# soundcard.net
KiCad netlist of a schematic drawn in EAGLE
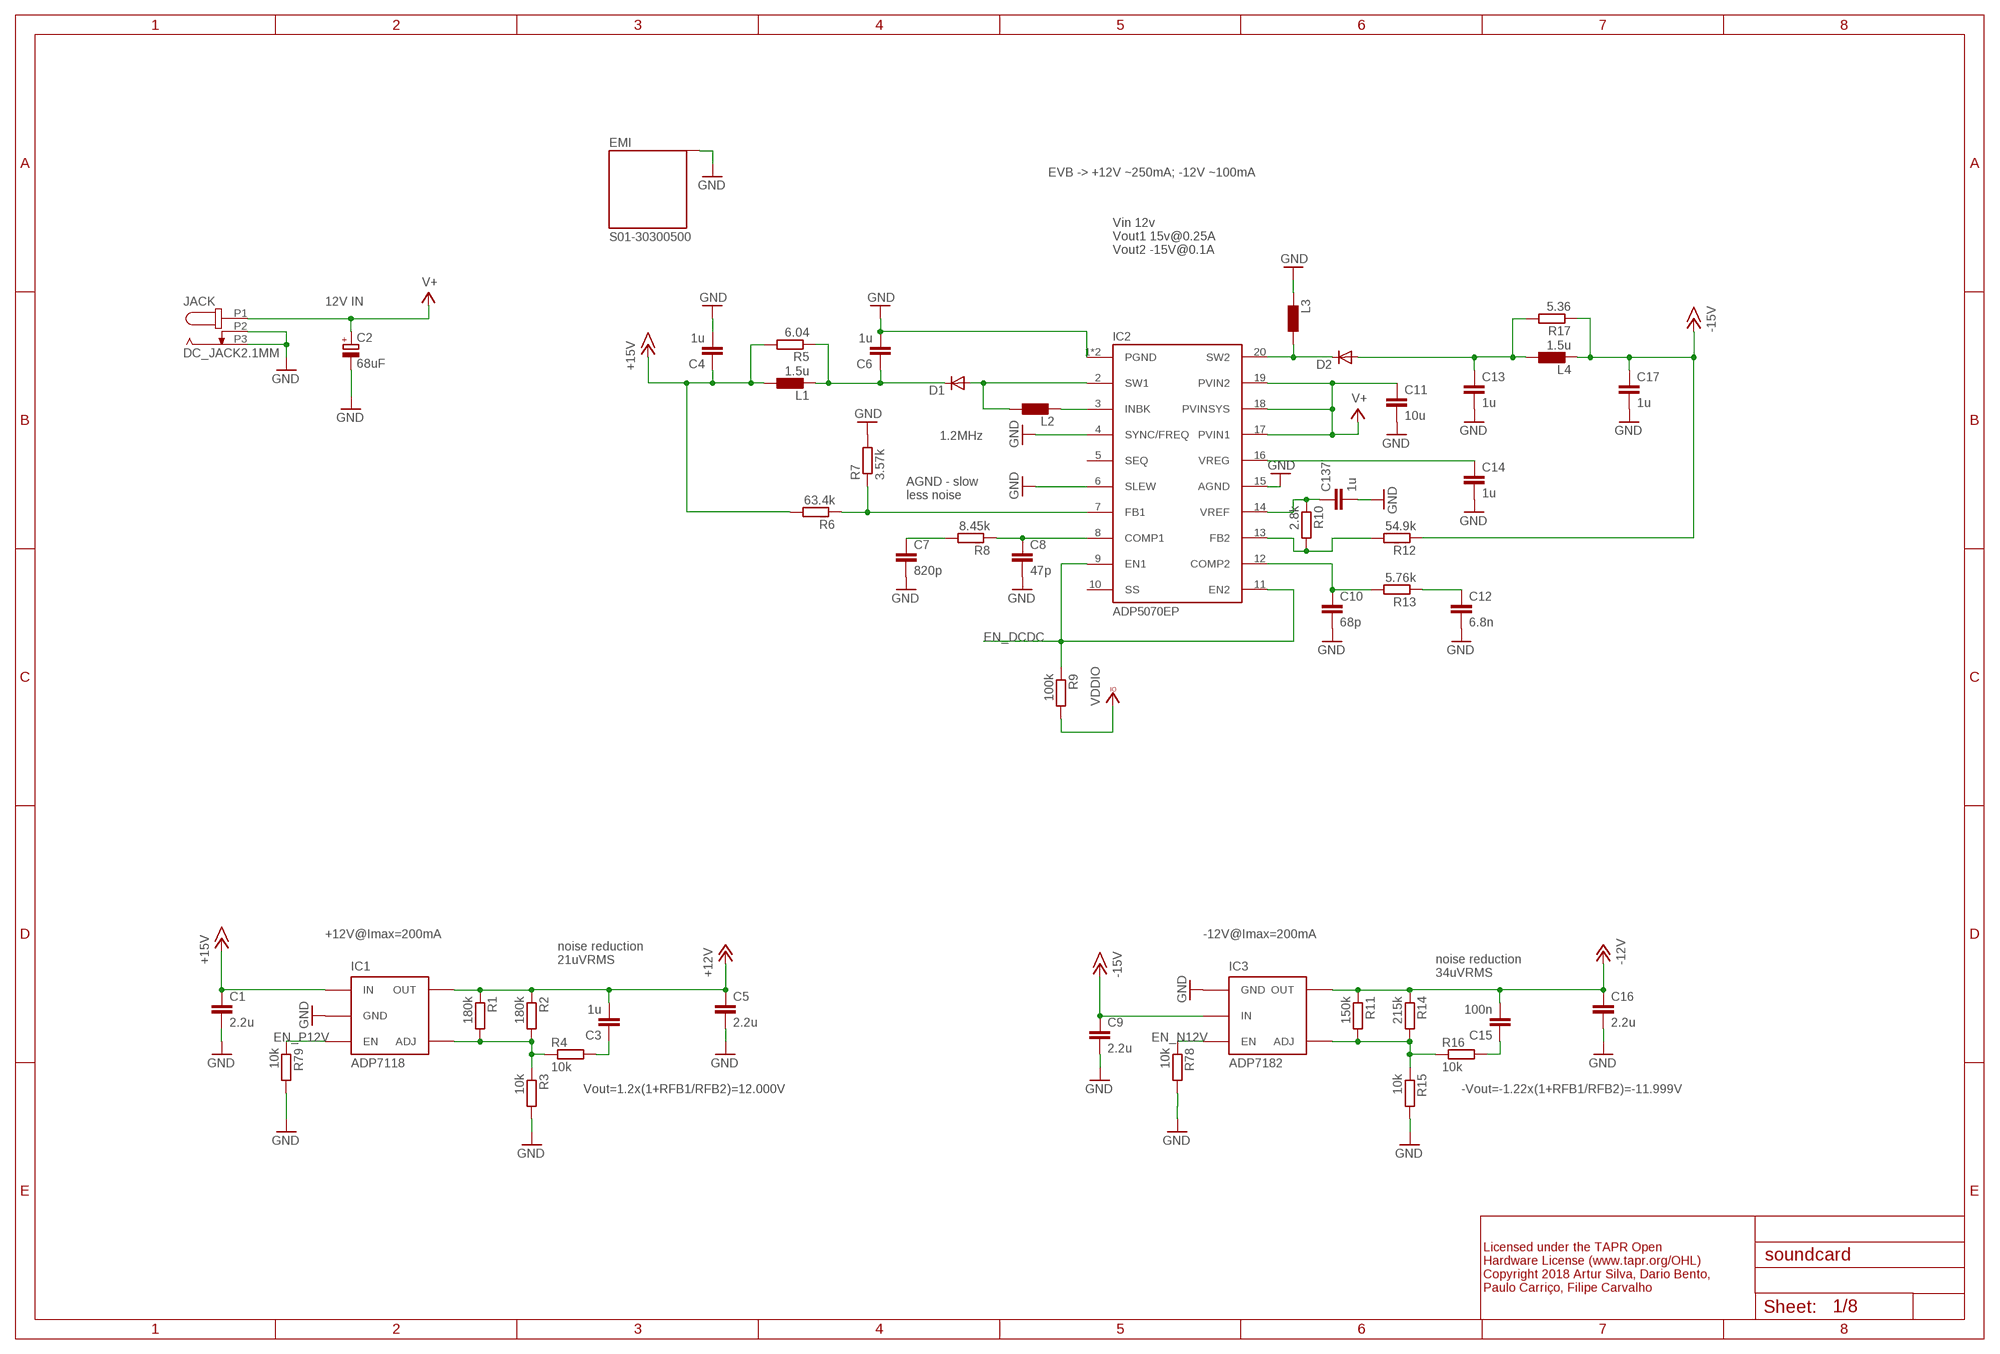
[diagram p0: schematic, sheet 1]
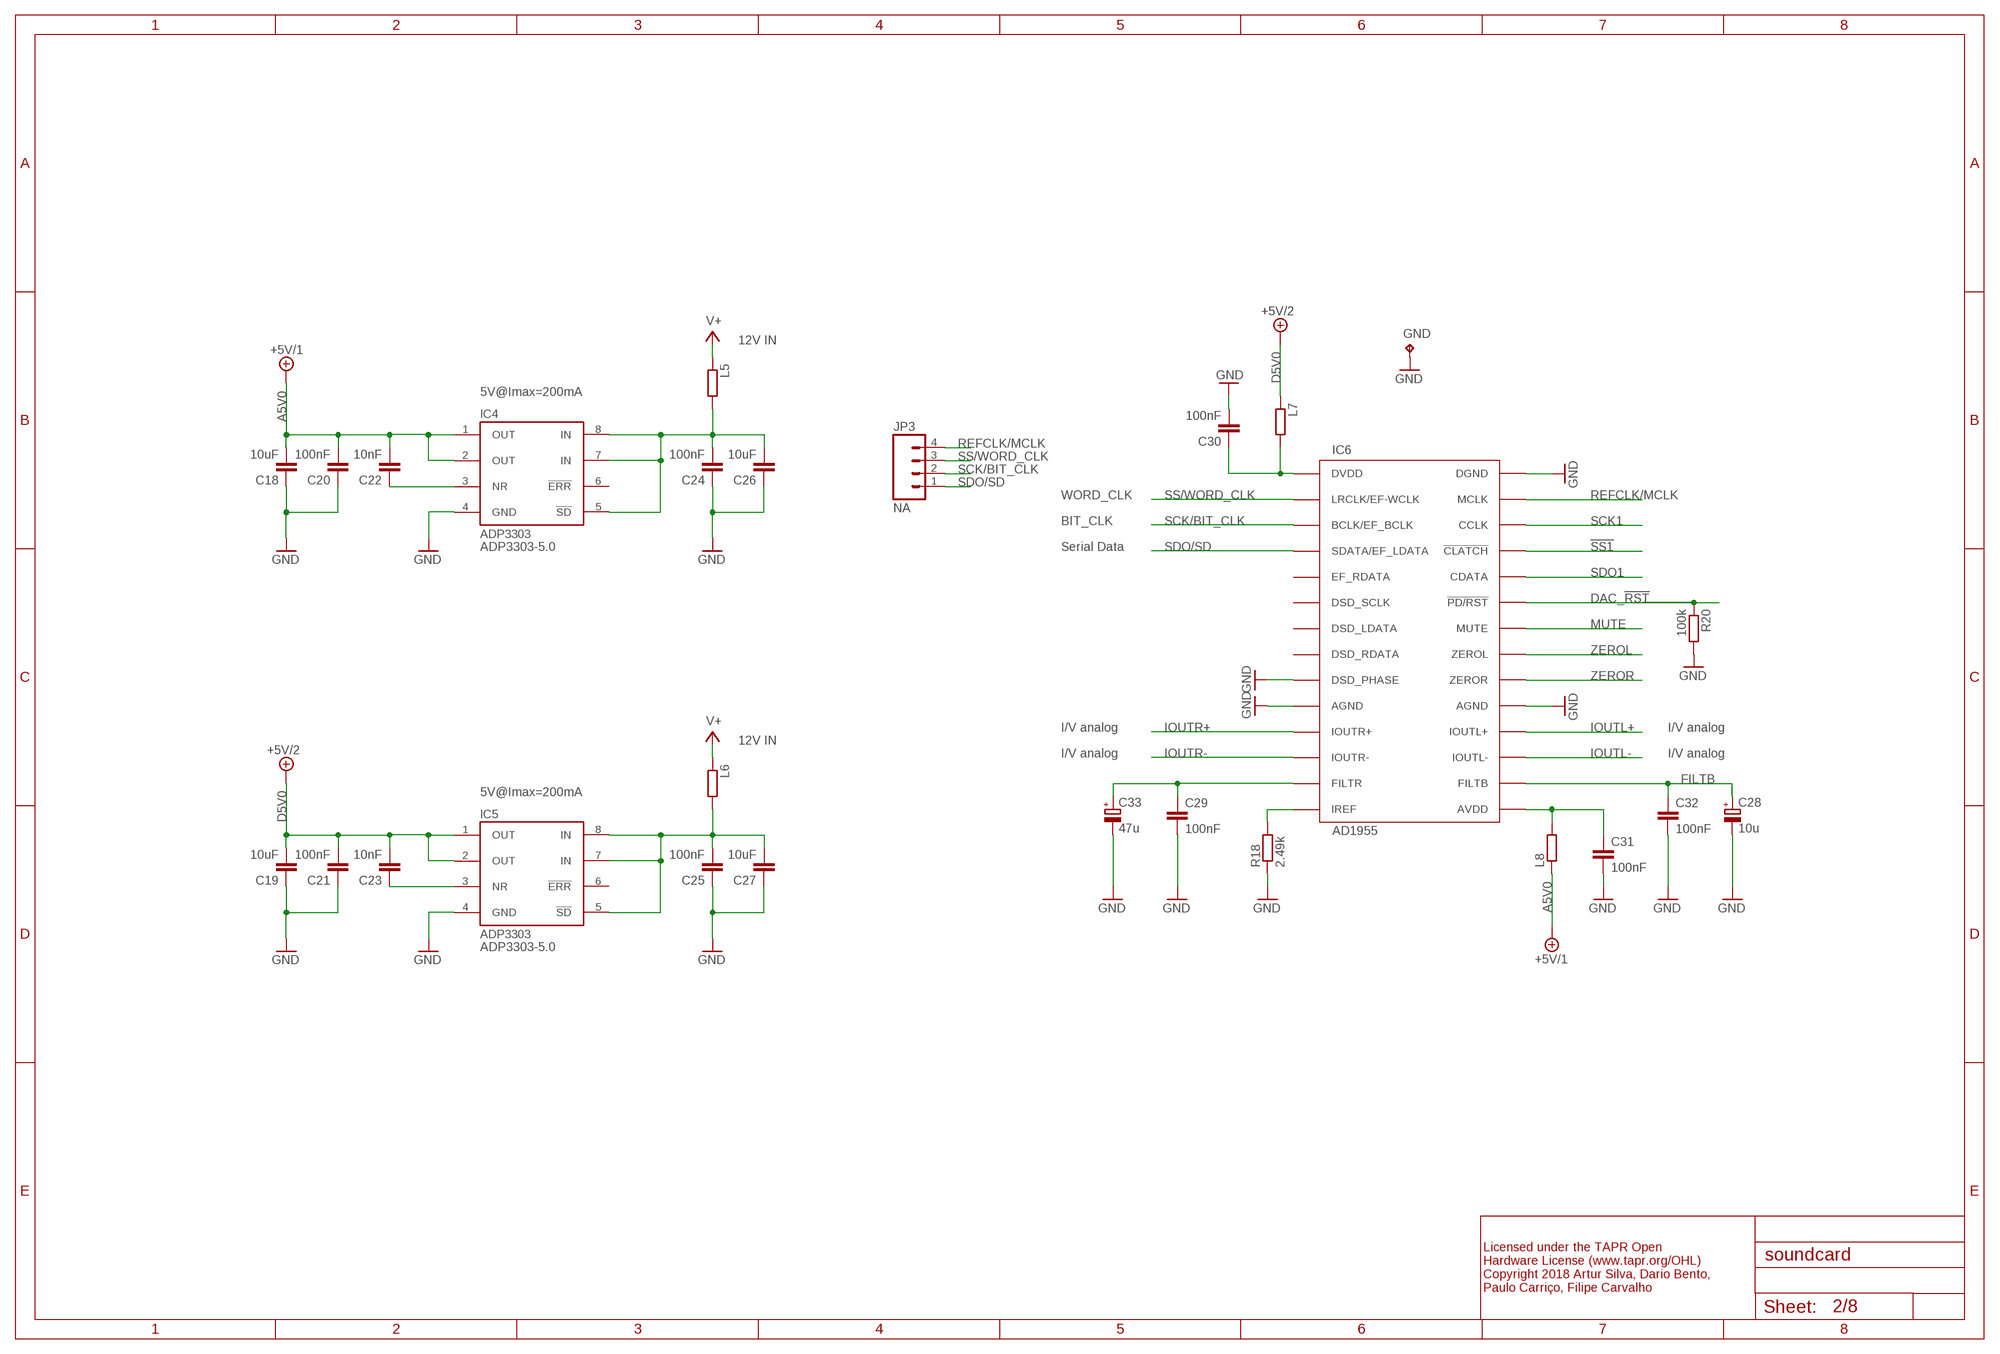
[diagram p1: schematic, sheet 2]
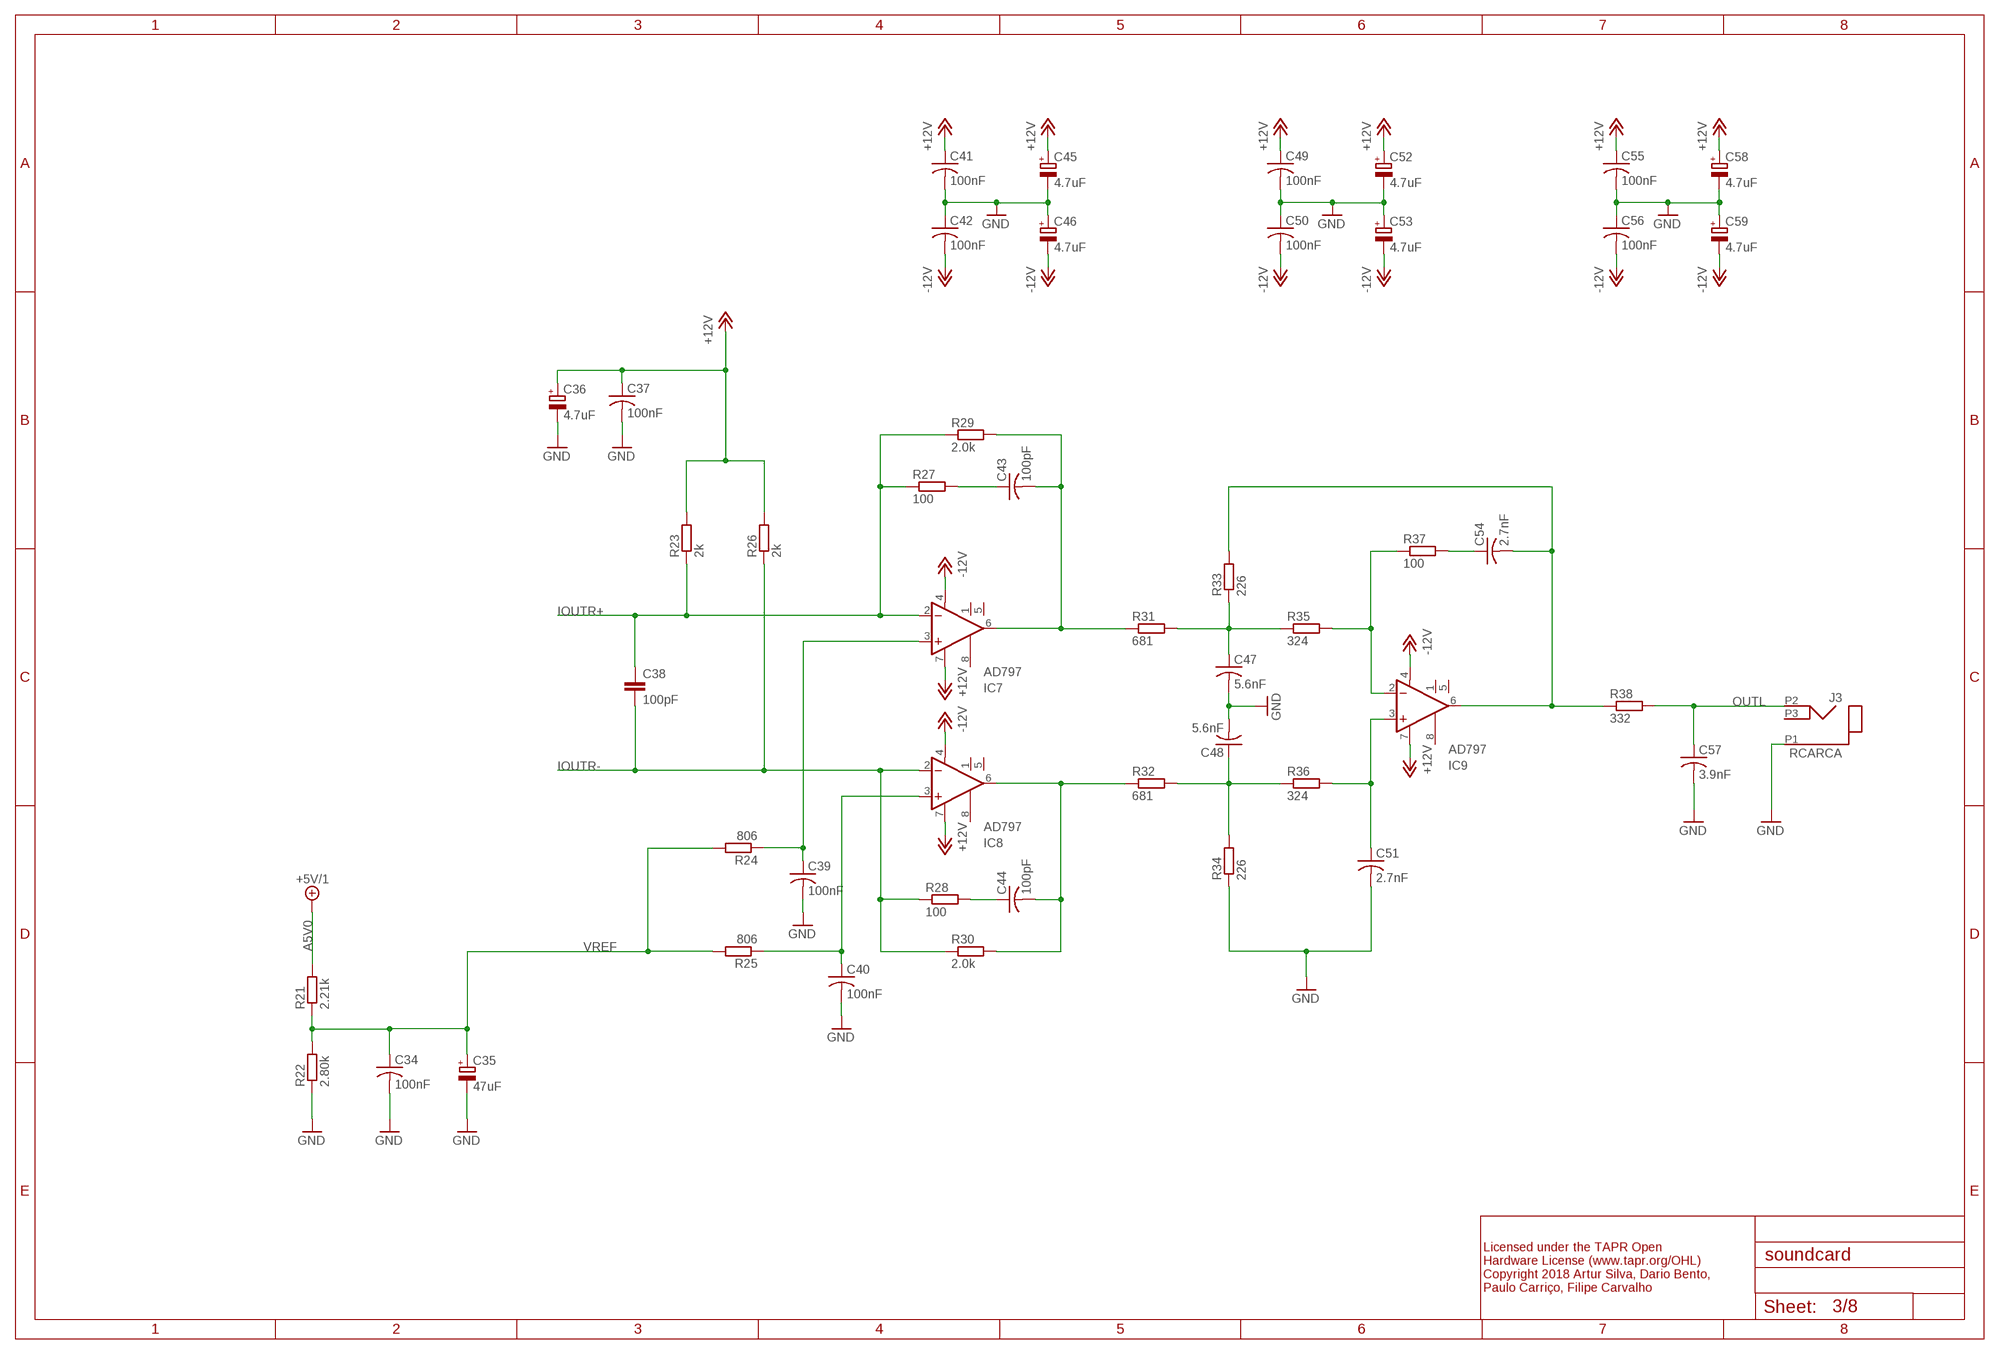
[diagram p2: schematic, sheet 3]
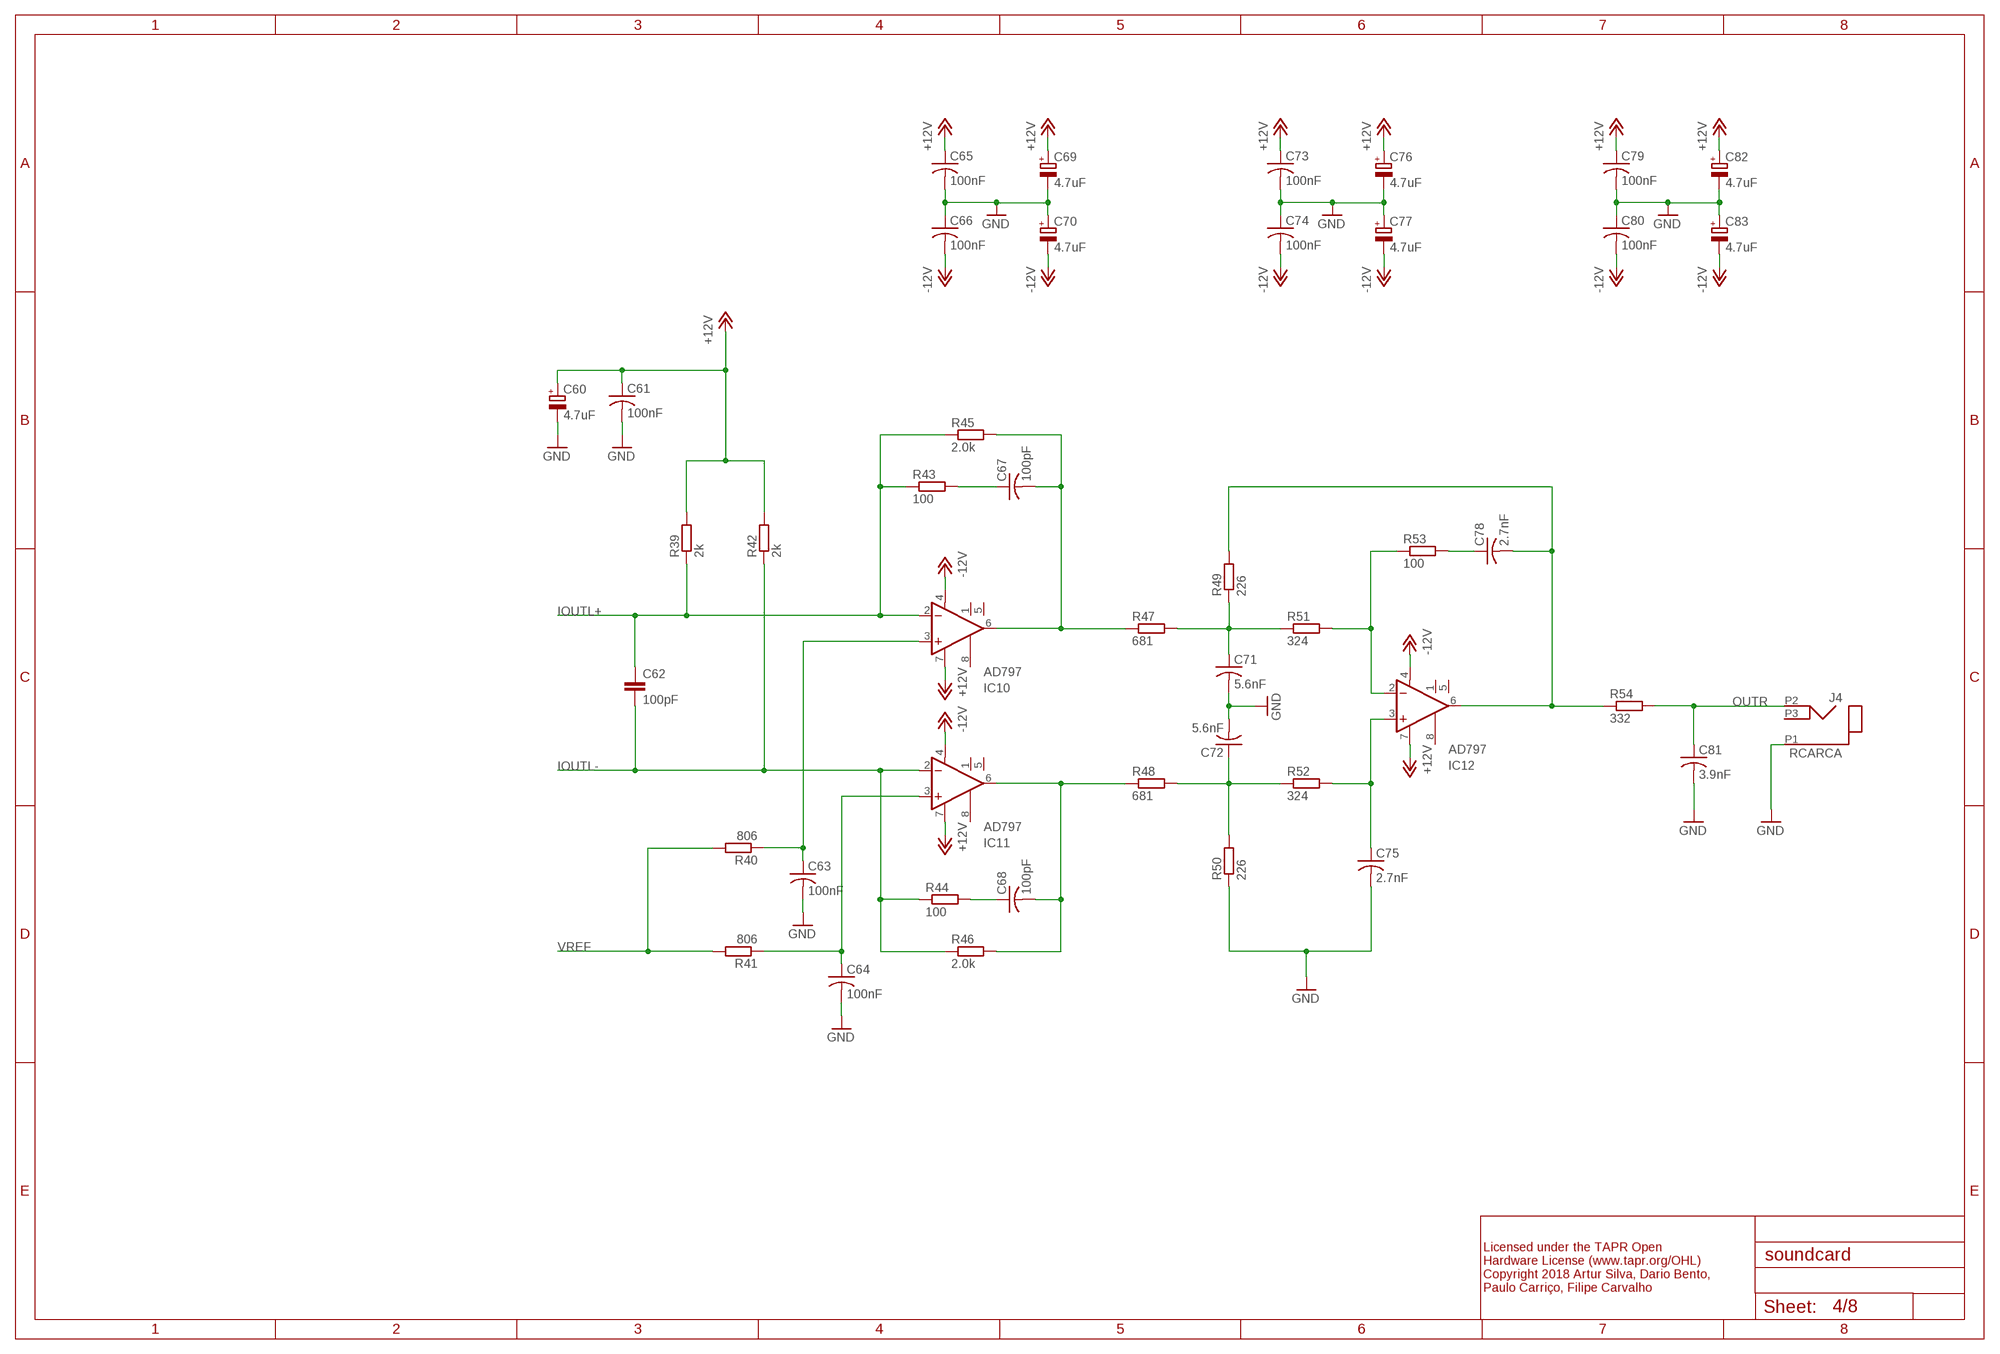
[diagram p3: schematic, sheet 4]
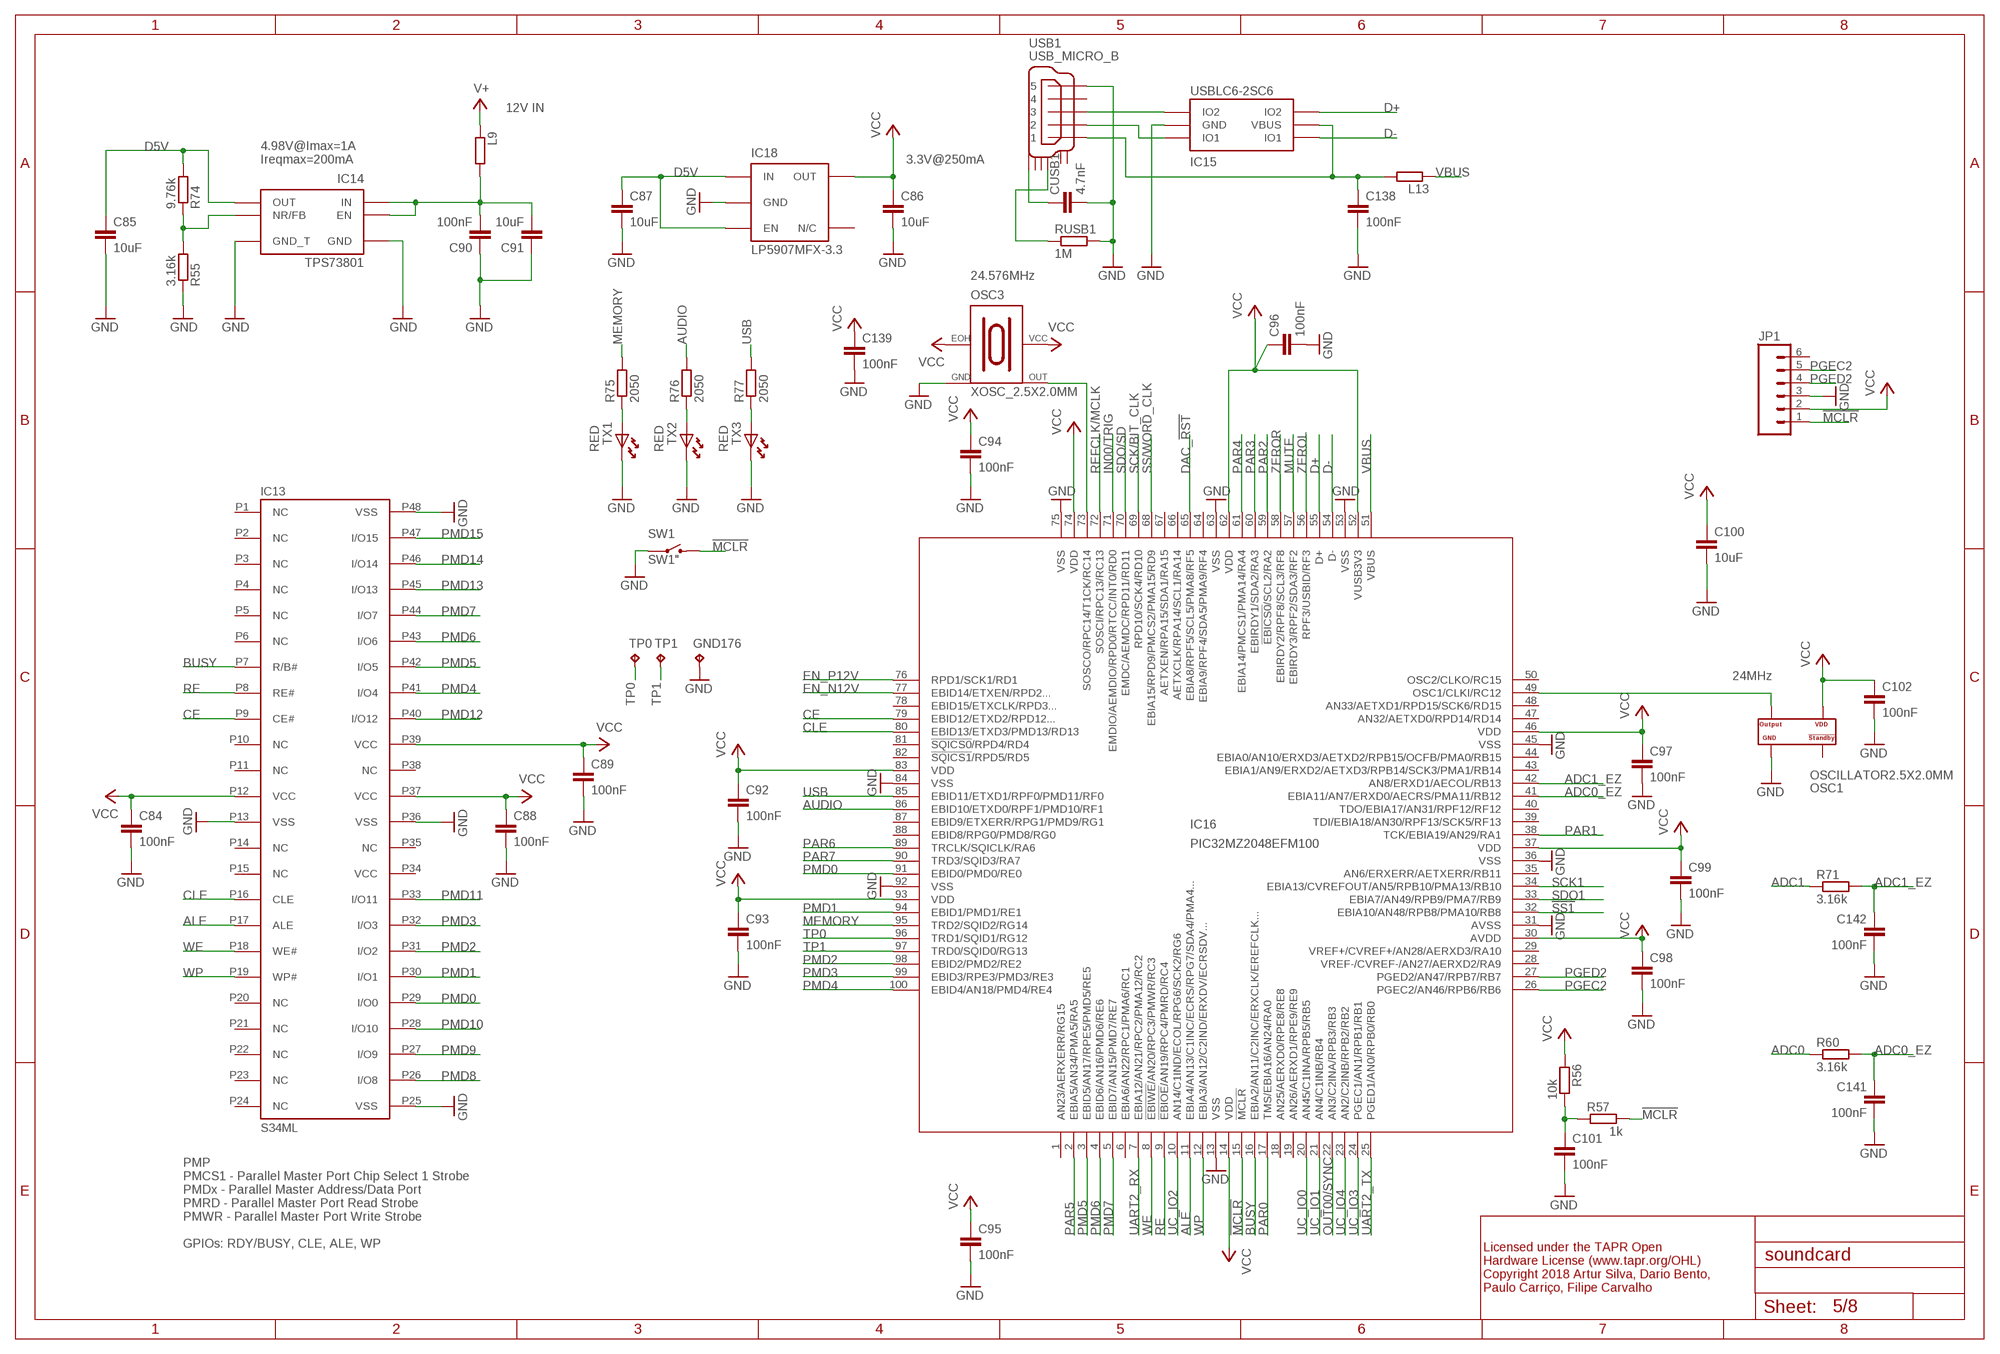
[diagram p4: schematic, sheet 5]
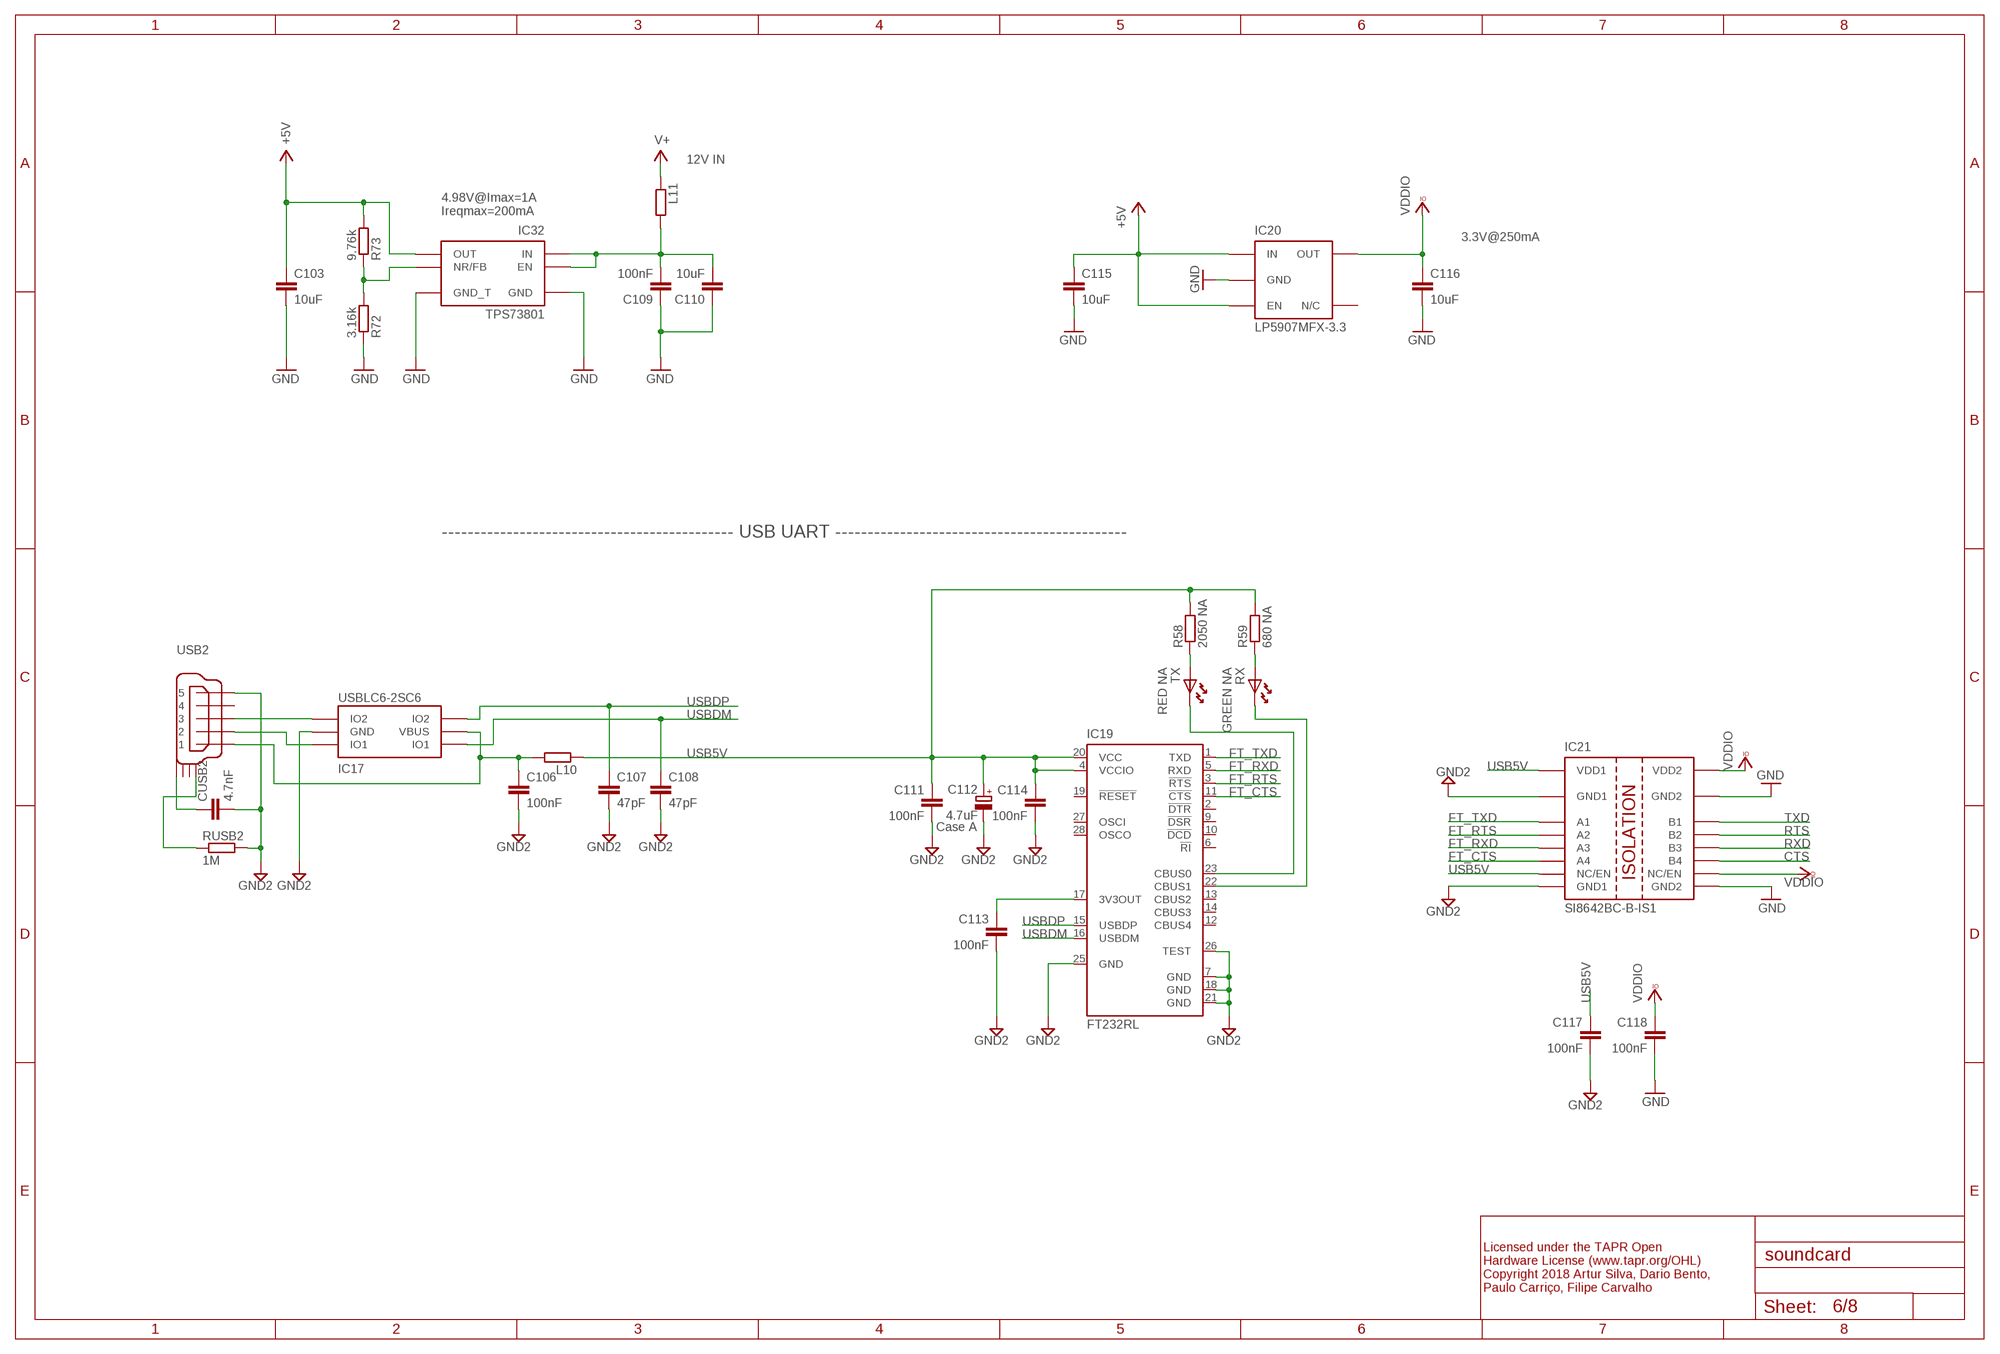
[diagram p5: schematic, sheet 6]
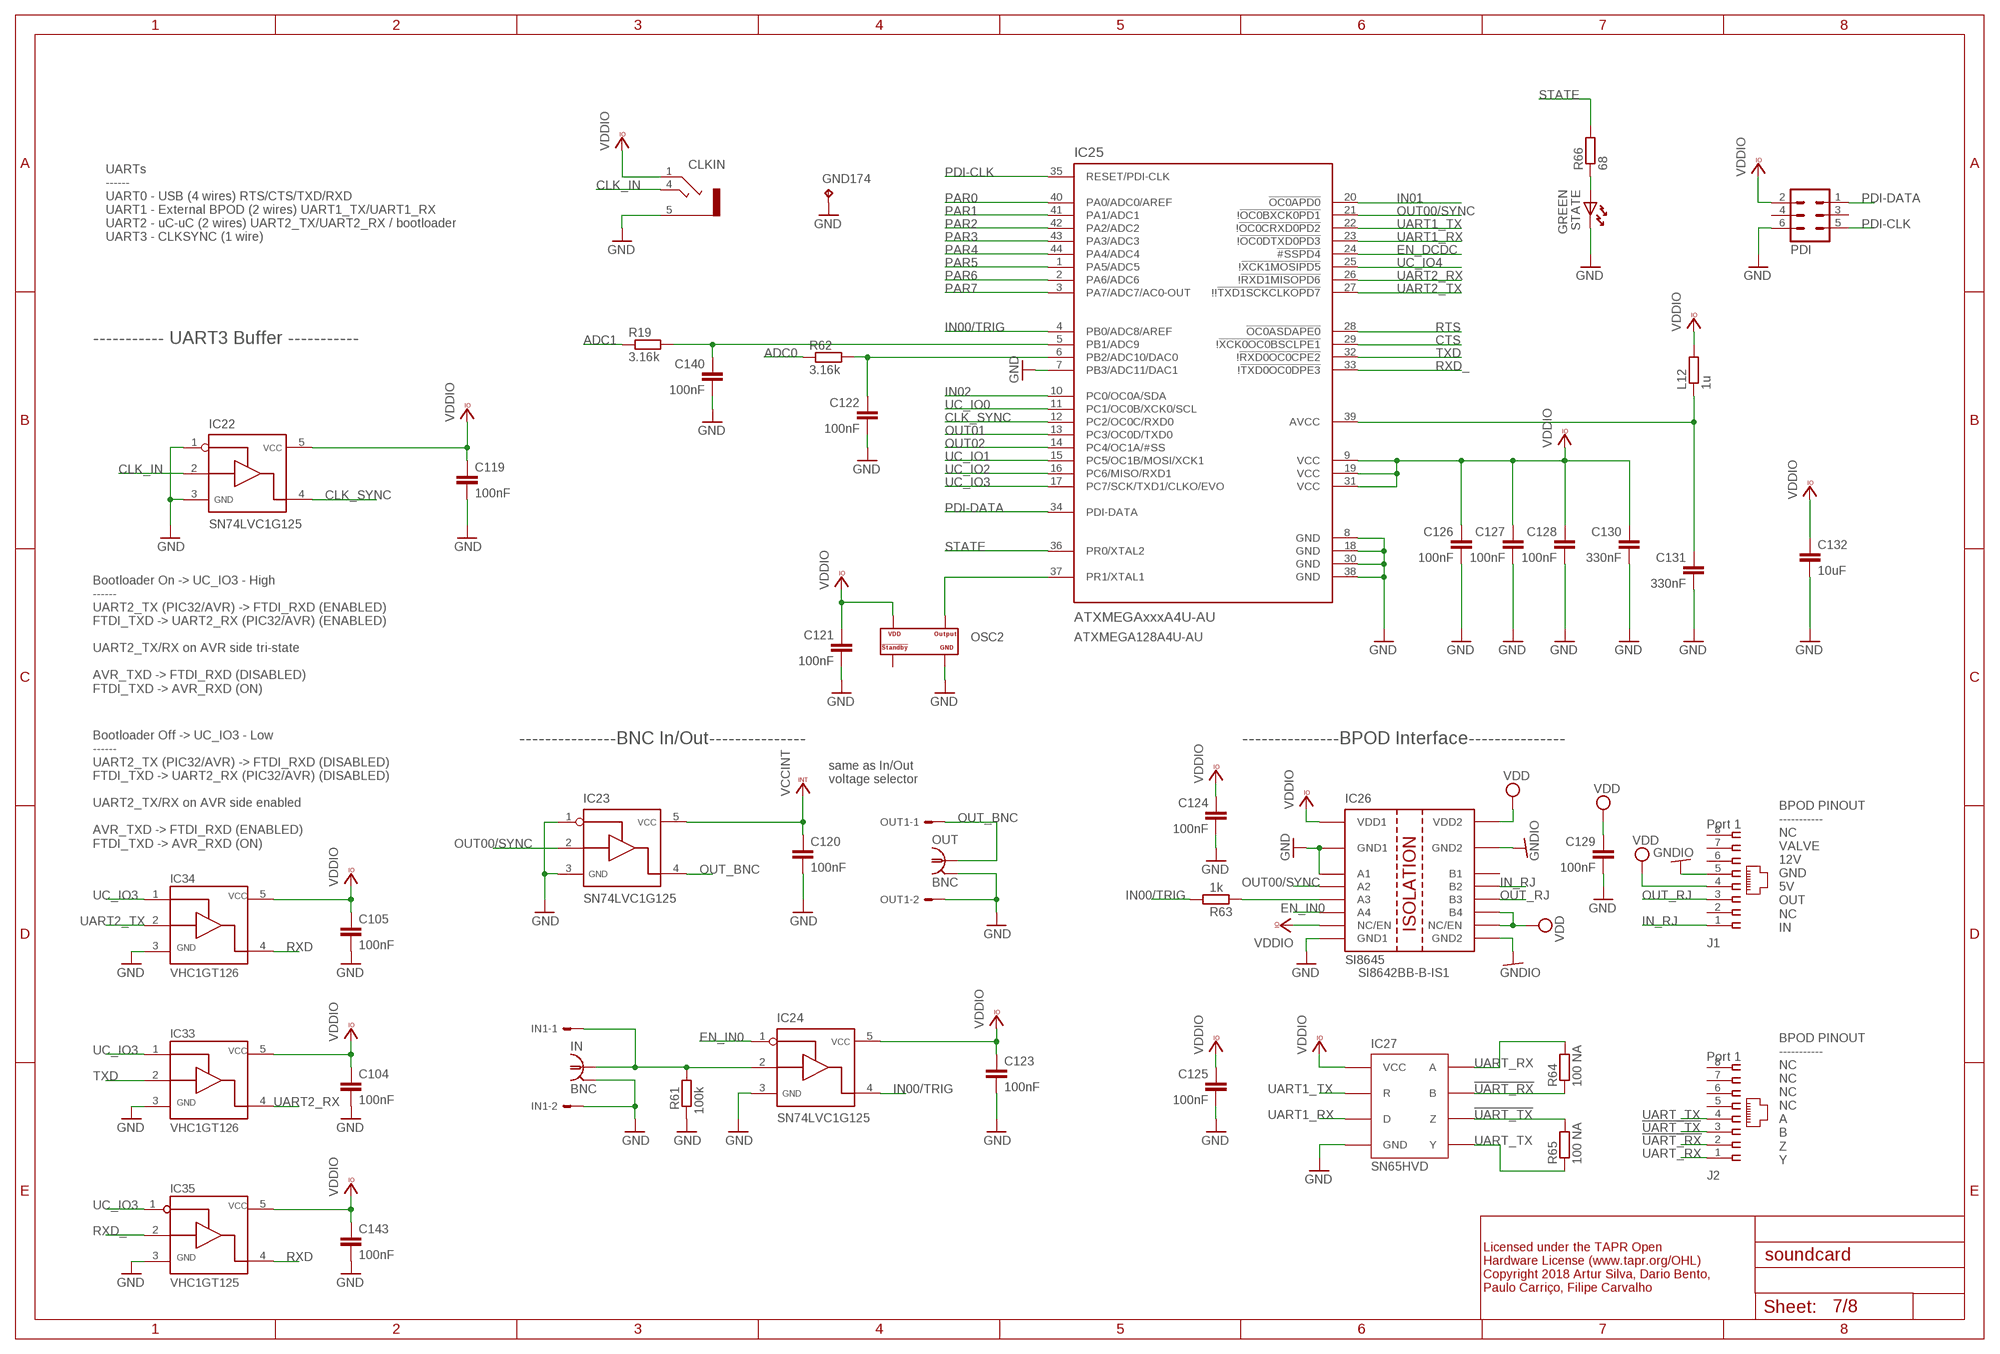
[diagram p6: schematic, sheet 7]
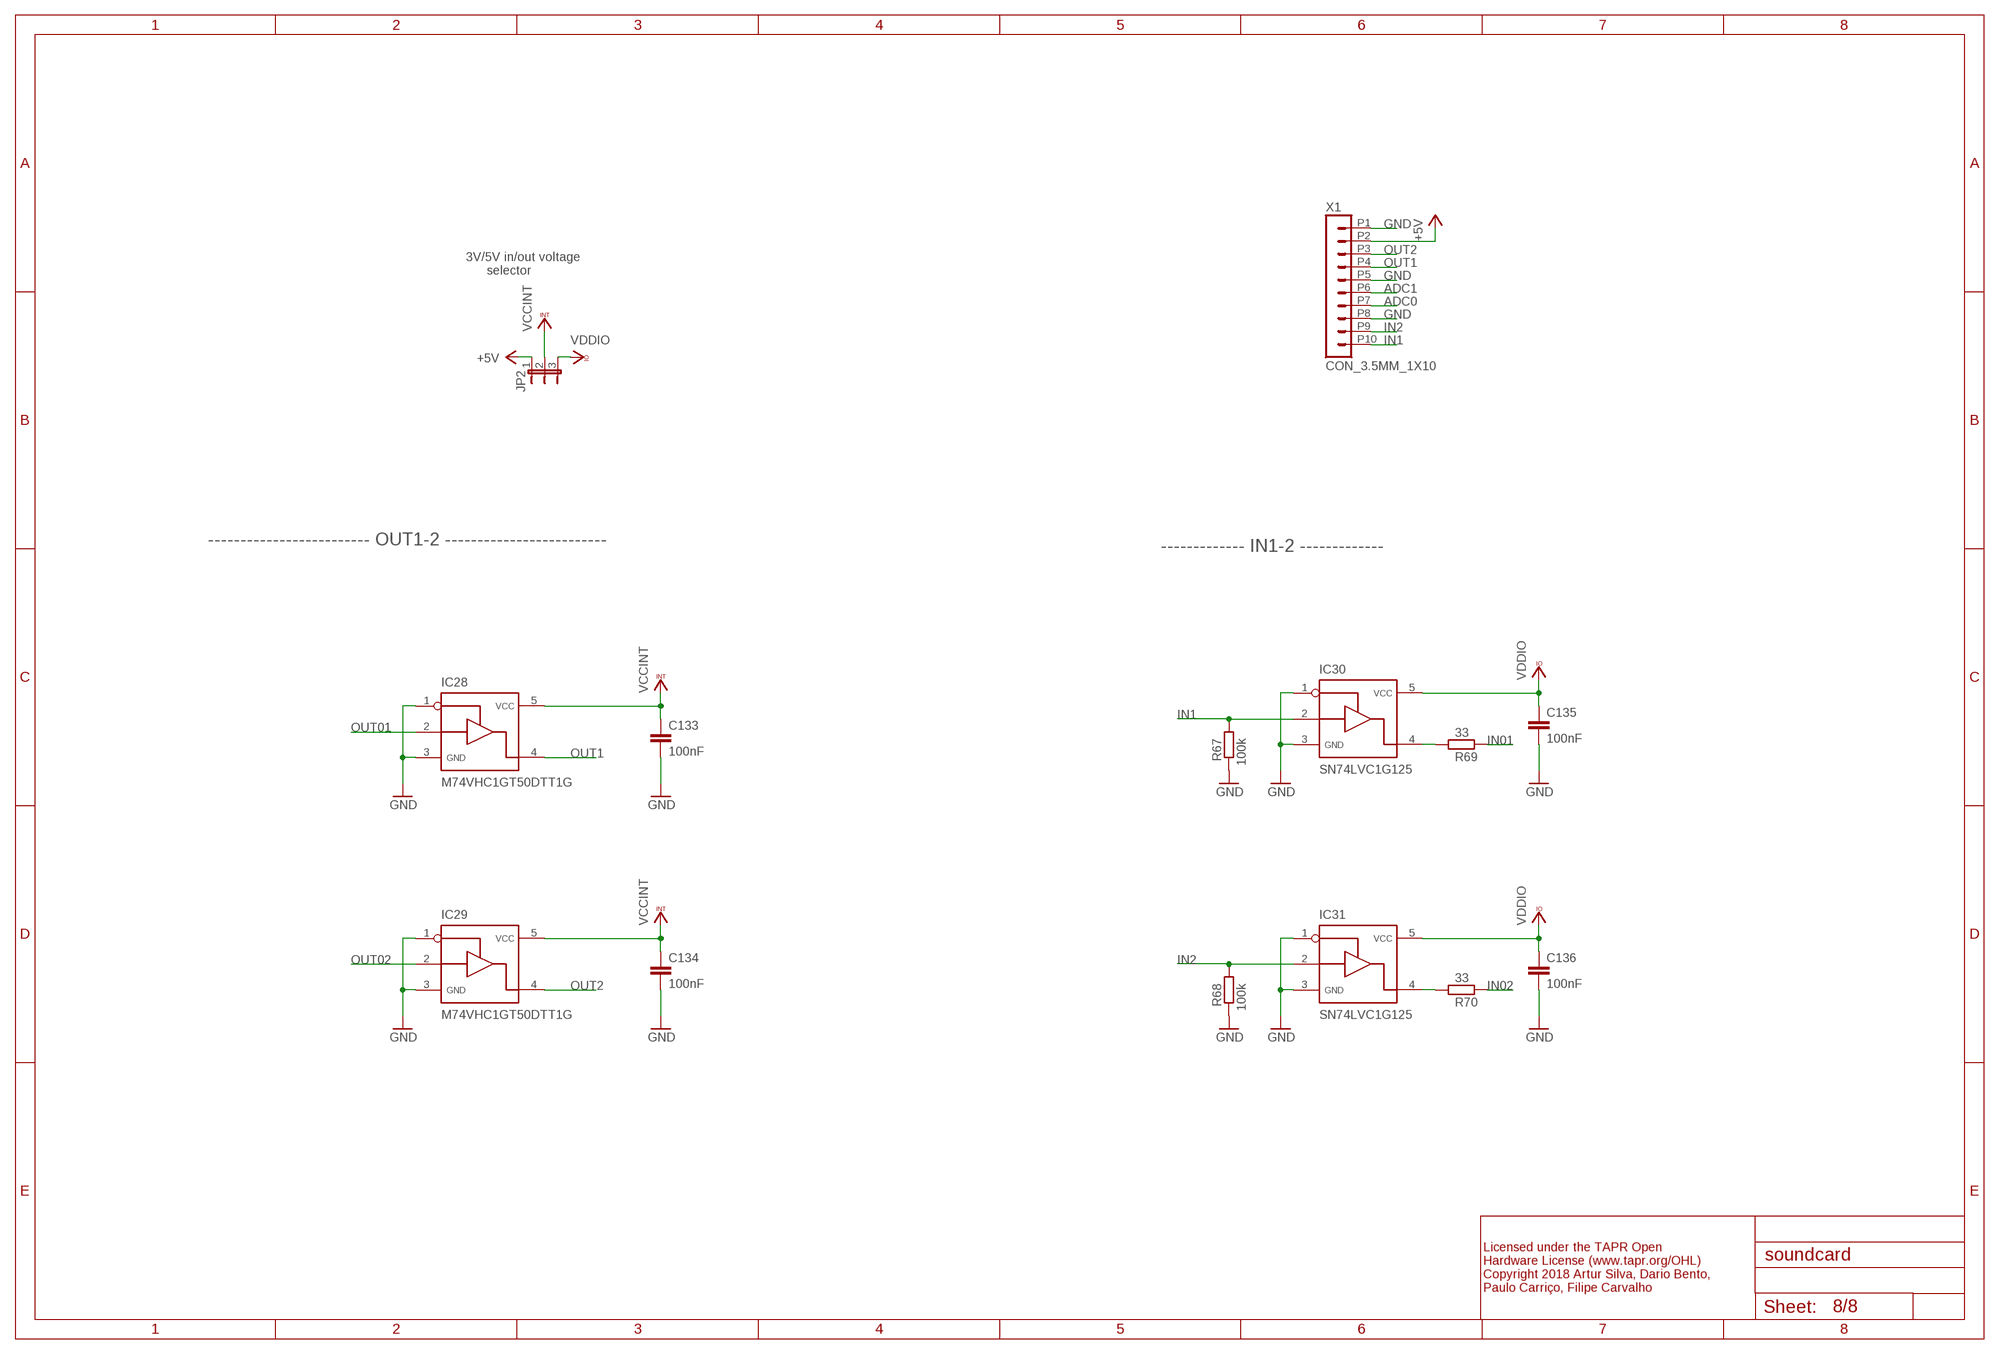
[diagram p7: schematic, sheet 8]

(export (version "E")
  (design (tool "Eeschema 10.0.6"))
  (components
    (comp (ref "C18")
      (value "10uF")
      (footprint "eagle-import:C0603")
      (libsource (lib "eagle-import") (part "C-EUC0603"))
    )
    (comp (ref "C19")
      (value "10uF")
      (footprint "eagle-import:C0603")
      (libsource (lib "eagle-import") (part "C-EUC0603"))
    )
    (comp (ref "C20")
      (value "100nF")
      (footprint "eagle-import:C0402")
      (libsource (lib "eagle-import") (part "C-EUC0402"))
    )
    (comp (ref "C21")
      (value "100nF")
      (footprint "eagle-import:C0402")
      (libsource (lib "eagle-import") (part "C-EUC0402"))
    )
    (comp (ref "C22")
      (value "10nF")
      (footprint "eagle-import:C0402")
      (libsource (lib "eagle-import") (part "C-EUC0402"))
    )
    (comp (ref "C23")
      (value "10nF")
      (footprint "eagle-import:C0402")
      (libsource (lib "eagle-import") (part "C-EUC0402"))
    )
    (comp (ref "C24")
      (value "100nF")
      (footprint "eagle-import:C0402")
      (libsource (lib "eagle-import") (part "C-EUC0402"))
    )
    (comp (ref "C25")
      (value "100nF")
      (footprint "eagle-import:C0402")
      (libsource (lib "eagle-import") (part "C-EUC0402"))
    )
    (comp (ref "C26")
      (value "10uF")
      (footprint "eagle-import:C0603")
      (libsource (lib "eagle-import") (part "C-EUC0603"))
    )
    (comp (ref "C27")
      (value "10uF")
      (footprint "eagle-import:C0603")
      (libsource (lib "eagle-import") (part "C-EUC0603"))
    )
    (comp (ref "C28")
      (value "10u")
      (footprint "eagle-import:B_3528-21W")
      (libsource (lib "eagle-import") (part "CPOL-EUB/3528-21W"))
    )
    (comp (ref "C29")
      (value "100nF")
      (footprint "eagle-import:C0402")
      (libsource (lib "eagle-import") (part "C-EUC0402"))
    )
    (comp (ref "C30")
      (value "100nF")
      (footprint "eagle-import:C0402")
      (libsource (lib "eagle-import") (part "C-EUC0402"))
    )
    (comp (ref "C31")
      (value "100nF")
      (footprint "eagle-import:C0402")
      (libsource (lib "eagle-import") (part "C-EUC0402"))
    )
    (comp (ref "C32")
      (value "100nF")
      (footprint "eagle-import:C0402")
      (libsource (lib "eagle-import") (part "C-EUC0402"))
    )
    (comp (ref "C33")
      (value "47u")
      (footprint "eagle-import:C_6032-28W")
      (libsource (lib "eagle-import") (part "CPOL-EUC/6032-28W"))
    )
    (comp (ref "GND")
      (value "TP")
      (footprint "eagle-import:TP_1")
      (libsource (lib "eagle-import") (part "TP"))
    )
    (comp (ref "IC4")
      (value "ADP3303")
      (footprint "eagle-import:SO08")
      (libsource (lib "eagle-import") (part "ADP3303"))
    )
    (comp (ref "IC5")
      (value "ADP3303")
      (footprint "eagle-import:SO08")
      (libsource (lib "eagle-import") (part "ADP3303"))
    )
    (comp (ref "IC6")
      (value "AD1955")
      (footprint "eagle-import:SSOP28")
      (libsource (lib "eagle-import") (part "AD1955"))
    )
    (comp (ref "JP3")
      (value "NA")
      (footprint "eagle-import:1X04_NO_SILK")
      (libsource (lib "eagle-import") (part "M041X04_NO_SILK"))
    )
    (comp (ref "L5")
      (value "600@100M")
      (footprint "eagle-import:R0805")
      (libsource (lib "eagle-import") (part "R-EU_R0805"))
    )
    (comp (ref "L6")
      (value "600@100M")
      (footprint "eagle-import:R0805")
      (libsource (lib "eagle-import") (part "R-EU_R0805"))
    )
    (comp (ref "L7")
      (value "600@100M")
      (footprint "eagle-import:R0805")
      (libsource (lib "eagle-import") (part "R-EU_R0805"))
    )
    (comp (ref "L8")
      (value "600@100M")
      (footprint "eagle-import:R0805")
      (libsource (lib "eagle-import") (part "R-EU_R0805"))
    )
    (comp (ref "R18")
      (value "2.49k")
      (footprint "eagle-import:0207_12")
      (libsource (lib "eagle-import") (part "resistor_R-EU_0207/12"))
    )
    (comp (ref "R20")
      (value "100k")
      (footprint "eagle-import:R0402")
      (libsource (lib "eagle-import") (part "R-EU_R0402"))
    )
    (comp (ref "C1")
      (value "2.2u")
      (footprint "eagle-import:C0603")
      (libsource (lib "eagle-import") (part "C-EUC0603"))
    )
    (comp (ref "C2")
      (value "68uF")
      (footprint "eagle-import:E2-5")
      (libsource (lib "eagle-import") (part "resistor_CPOL-EUE2-5"))
    )
    (comp (ref "C3")
      (value "1u")
      (footprint "eagle-import:C0402")
      (libsource (lib "eagle-import") (part "C-EUC0402"))
    )
    (comp (ref "C4")
      (value "1u")
      (footprint "eagle-import:C0603")
      (libsource (lib "eagle-import") (part "C-EUC0603"))
    )
    (comp (ref "C5")
      (value "2.2u")
      (footprint "eagle-import:C0603")
      (libsource (lib "eagle-import") (part "C-EUC0603"))
    )
    (comp (ref "C6")
      (value "1u")
      (footprint "eagle-import:C0603")
      (libsource (lib "eagle-import") (part "C-EUC0603"))
    )
    (comp (ref "C7")
      (value "820p")
      (footprint "eagle-import:C0402")
      (libsource (lib "eagle-import") (part "C-EUC0402"))
    )
    (comp (ref "C8")
      (value "47p")
      (footprint "eagle-import:C0402")
      (libsource (lib "eagle-import") (part "C-EUC0402"))
    )
    (comp (ref "C9")
      (value "2.2u")
      (footprint "eagle-import:C0603")
      (libsource (lib "eagle-import") (part "C-EUC0603"))
    )
    (comp (ref "C10")
      (value "68p")
      (footprint "eagle-import:C0402")
      (libsource (lib "eagle-import") (part "C-EUC0402"))
    )
    (comp (ref "C11")
      (value "10u")
      (footprint "eagle-import:C1206")
      (libsource (lib "eagle-import") (part "C-EUC1206"))
    )
    (comp (ref "C12")
      (value "6.8n")
      (footprint "eagle-import:C0402")
      (libsource (lib "eagle-import") (part "C-EUC0402"))
    )
    (comp (ref "C13")
      (value "1u")
      (footprint "eagle-import:C0603")
      (libsource (lib "eagle-import") (part "C-EUC0603"))
    )
    (comp (ref "C14")
      (value "1u")
      (footprint "eagle-import:C0402")
      (libsource (lib "eagle-import") (part "C-EUC0402"))
    )
    (comp (ref "C15")
      (value "100n")
      (footprint "eagle-import:C0402")
      (libsource (lib "eagle-import") (part "C-EUC0402"))
    )
    (comp (ref "C16")
      (value "2.2u")
      (footprint "eagle-import:C0603")
      (libsource (lib "eagle-import") (part "C-EUC0603"))
    )
    (comp (ref "C17")
      (value "1u")
      (footprint "eagle-import:C0603")
      (libsource (lib "eagle-import") (part "C-EUC0603"))
    )
    (comp (ref "C137")
      (value "1u")
      (footprint "eagle-import:C0402")
      (libsource (lib "eagle-import") (part "C-EUC0402"))
    )
    (comp (ref "D1")
      (value "DIODE-SOD323-R")
      (footprint "eagle-import:SOD323-R")
      (libsource (lib "eagle-import") (part "DIODE-SOD323-R"))
    )
    (comp (ref "D2")
      (value "DIODE-SOD323-R")
      (footprint "eagle-import:SOD323-R")
      (libsource (lib "eagle-import") (part "DIODE-SOD323-R"))
    )
    (comp (ref "EMI")
      (value "S01-30300500")
      (footprint "eagle-import:S01-30300500")
      (libsource (lib "eagle-import") (part "S01-30300500"))
    )
    (comp (ref "IC1")
      (value "ADP7118")
      (footprint "eagle-import:TSOT23-5")
      (libsource (lib "eagle-import") (part "ADP7118"))
    )
    (comp (ref "IC2")
      (value "ADP5070EP")
      (footprint "eagle-import:TSSOP-EP-20")
      (libsource (lib "eagle-import") (part "ADP5070EP"))
    )
    (comp (ref "IC3")
      (value "ADP7182")
      (footprint "eagle-import:TSOT23-5")
      (libsource (lib "eagle-import") (part "ADP7182"))
    )
    (comp (ref "JACK")
      (value "DC_JACK2.1MM")
      (footprint "eagle-import:DC_POWER_INPUT_2.1MM")
      (libsource (lib "eagle-import") (part "DC_JACK2.1MM"))
    )
    (comp (ref "L1")
      (value "1.5u")
      (footprint "eagle-import:IND_LPS4012")
      (libsource (lib "eagle-import") (part "INDLPS4012"))
    )
    (comp (ref "L2")
      (value "INDLPS6225")
      (footprint "eagle-import:IND_LPS6225")
      (libsource (lib "eagle-import") (part "INDLPS6225"))
    )
    (comp (ref "L3")
      (value "INDLPS6225")
      (footprint "eagle-import:IND_LPS6225")
      (libsource (lib "eagle-import") (part "INDLPS6225"))
    )
    (comp (ref "L4")
      (value "1.5u")
      (footprint "eagle-import:IND_LPS4012")
      (libsource (lib "eagle-import") (part "INDLPS4012"))
    )
    (comp (ref "R1")
      (value "180k")
      (footprint "eagle-import:R0402")
      (libsource (lib "eagle-import") (part "R-EU_R0402"))
    )
    (comp (ref "R2")
      (value "180k")
      (footprint "eagle-import:R0402")
      (libsource (lib "eagle-import") (part "R-EU_R0402"))
    )
    (comp (ref "R3")
      (value "10k")
      (footprint "eagle-import:R0402")
      (libsource (lib "eagle-import") (part "R-EU_R0402"))
    )
    (comp (ref "R4")
      (value "10k")
      (footprint "eagle-import:R0402")
      (libsource (lib "eagle-import") (part "R-EU_R0402"))
    )
    (comp (ref "R5")
      (value "6.04")
      (footprint "eagle-import:R0402")
      (libsource (lib "eagle-import") (part "R-EU_R0402"))
    )
    (comp (ref "R6")
      (value "63.4k")
      (footprint "eagle-import:R0402")
      (libsource (lib "eagle-import") (part "R-EU_R0402"))
    )
    (comp (ref "R7")
      (value "3.57k")
      (footprint "eagle-import:R0402")
      (libsource (lib "eagle-import") (part "R-EU_R0402"))
    )
    (comp (ref "R8")
      (value "8.45k")
      (footprint "eagle-import:R0402")
      (libsource (lib "eagle-import") (part "R-EU_R0402"))
    )
    (comp (ref "R9")
      (value "100k")
      (footprint "eagle-import:R0402")
      (libsource (lib "eagle-import") (part "R-EU_R0402"))
    )
    (comp (ref "R10")
      (value "2.8k")
      (footprint "eagle-import:R0402")
      (libsource (lib "eagle-import") (part "R-EU_R0402"))
    )
    (comp (ref "R11")
      (value "150k")
      (footprint "eagle-import:R0402")
      (libsource (lib "eagle-import") (part "R-EU_R0402"))
    )
    (comp (ref "R12")
      (value "54.9k")
      (footprint "eagle-import:R0402")
      (libsource (lib "eagle-import") (part "R-EU_R0402"))
    )
    (comp (ref "R13")
      (value "5.76k")
      (footprint "eagle-import:R0402")
      (libsource (lib "eagle-import") (part "R-EU_R0402"))
    )
    (comp (ref "R14")
      (value "215k")
      (footprint "eagle-import:R0402")
      (libsource (lib "eagle-import") (part "R-EU_R0402"))
    )
    (comp (ref "R15")
      (value "10k")
      (footprint "eagle-import:R0402")
      (libsource (lib "eagle-import") (part "R-EU_R0402"))
    )
    (comp (ref "R16")
      (value "10k")
      (footprint "eagle-import:R0402")
      (libsource (lib "eagle-import") (part "R-EU_R0402"))
    )
    (comp (ref "R17")
      (value "5.36")
      (footprint "eagle-import:R0402")
      (libsource (lib "eagle-import") (part "R-EU_R0402"))
    )
    (comp (ref "R78")
      (value "10k")
      (footprint "eagle-import:R0402")
      (libsource (lib "eagle-import") (part "R-EU_R0402"))
    )
    (comp (ref "R79")
      (value "10k")
      (footprint "eagle-import:R0402")
      (libsource (lib "eagle-import") (part "R-EU_R0402"))
    )
    (comp (ref "C133")
      (value "100nF")
      (footprint "eagle-import:C0402")
      (libsource (lib "eagle-import") (part "C-EUC0402"))
    )
    (comp (ref "C134")
      (value "100nF")
      (footprint "eagle-import:C0402")
      (libsource (lib "eagle-import") (part "C-EUC0402"))
    )
    (comp (ref "C135")
      (value "100nF")
      (footprint "eagle-import:C0402")
      (libsource (lib "eagle-import") (part "C-EUC0402"))
    )
    (comp (ref "C136")
      (value "100nF")
      (footprint "eagle-import:C0402")
      (libsource (lib "eagle-import") (part "C-EUC0402"))
    )
    (comp (ref "IC28")
      (value "M74VHC1GT50DTT1G")
      (footprint "eagle-import:SOT23-5")
      (libsource (lib "eagle-import") (part "SN74LVC1G125"))
    )
    (comp (ref "IC29")
      (value "M74VHC1GT50DTT1G")
      (footprint "eagle-import:SOT23-5")
      (libsource (lib "eagle-import") (part "SN74LVC1G125"))
    )
    (comp (ref "IC30")
      (value "SN74LVC1G125")
      (footprint "eagle-import:SOT23-5")
      (libsource (lib "eagle-import") (part "SN74LVC1G125"))
    )
    (comp (ref "IC31")
      (value "SN74LVC1G125")
      (footprint "eagle-import:SOT23-5")
      (libsource (lib "eagle-import") (part "SN74LVC1G125"))
    )
    (comp (ref "JP2")
      (value "JP2E")
      (footprint "eagle-import:JP2")
      (libsource (lib "eagle-import") (part "JP2E"))
    )
    (comp (ref "R67")
      (value "100k")
      (footprint "eagle-import:R0402")
      (libsource (lib "eagle-import") (part "R-EU_R0402"))
    )
    (comp (ref "R68")
      (value "100k")
      (footprint "eagle-import:R0402")
      (libsource (lib "eagle-import") (part "R-EU_R0402"))
    )
    (comp (ref "R69")
      (value "33")
      (footprint "eagle-import:R0402")
      (libsource (lib "eagle-import") (part "R-EU_R0402"))
    )
    (comp (ref "R70")
      (value "33")
      (footprint "eagle-import:R0402")
      (libsource (lib "eagle-import") (part "R-EU_R0402"))
    )
    (comp (ref "X1")
      (value "CON_3.5MM_1X10")
      (footprint "eagle-import:CON_3.5MM_1X10")
      (libsource (lib "eagle-import") (part "CON_3.5MM_1X10"))
    )
    (comp (ref "C104")
      (value "100nF")
      (footprint "eagle-import:C0402")
      (libsource (lib "eagle-import") (part "C-EUC0402"))
    )
    (comp (ref "C105")
      (value "100nF")
      (footprint "eagle-import:C0402")
      (libsource (lib "eagle-import") (part "C-EUC0402"))
    )
    (comp (ref "C119")
      (value "100nF")
      (footprint "eagle-import:C0402")
      (libsource (lib "eagle-import") (part "C-EUC0402"))
    )
    (comp (ref "C120")
      (value "100nF")
      (footprint "eagle-import:C0402")
      (libsource (lib "eagle-import") (part "C-EUC0402"))
    )
    (comp (ref "C121")
      (value "100nF")
      (footprint "eagle-import:C0402")
      (libsource (lib "eagle-import") (part "C-EUC0402"))
    )
    (comp (ref "C122")
      (value "100nF")
      (footprint "eagle-import:C0402")
      (libsource (lib "eagle-import") (part "C-EUC0402"))
    )
    (comp (ref "C123")
      (value "100nF")
      (footprint "eagle-import:C0402")
      (libsource (lib "eagle-import") (part "C-EUC0402"))
    )
    (comp (ref "C124")
      (value "100nF")
      (footprint "eagle-import:C0402")
      (libsource (lib "eagle-import") (part "C-EUC0402"))
    )
    (comp (ref "C125")
      (value "100nF")
      (footprint "eagle-import:C0402")
      (libsource (lib "eagle-import") (part "C-EUC0402"))
    )
    (comp (ref "C126")
      (value "100nF")
      (footprint "eagle-import:C0402")
      (libsource (lib "eagle-import") (part "C-EUC0402"))
    )
    (comp (ref "C127")
      (value "100nF")
      (footprint "eagle-import:C0402")
      (libsource (lib "eagle-import") (part "C-EUC0402"))
    )
    (comp (ref "C128")
      (value "100nF")
      (footprint "eagle-import:C0402")
      (libsource (lib "eagle-import") (part "C-EUC0402"))
    )
    (comp (ref "C129")
      (value "100nF")
      (footprint "eagle-import:C0402")
      (libsource (lib "eagle-import") (part "C-EUC0402"))
    )
    (comp (ref "C130")
      (value "330nF")
      (footprint "eagle-import:C0402")
      (libsource (lib "eagle-import") (part "C-EUC0402"))
    )
    (comp (ref "C131")
      (value "330nF")
      (footprint "eagle-import:C0402")
      (libsource (lib "eagle-import") (part "C-EUC0402"))
    )
    (comp (ref "C132")
      (value "10uF")
      (footprint "eagle-import:C0603")
      (libsource (lib "eagle-import") (part "C-EUC0603"))
    )
    (comp (ref "C140")
      (value "100nF")
      (footprint "eagle-import:C0402")
      (libsource (lib "eagle-import") (part "C-EUC0402"))
    )
    (comp (ref "C143")
      (value "100nF")
      (footprint "eagle-import:C0402")
      (libsource (lib "eagle-import") (part "C-EUC0402"))
    )
    (comp (ref "CLKIN")
      (value "STEREO_JACK")
      (footprint "eagle-import:35RASMT2BHNTRX")
      (libsource (lib "eagle-import") (part "STEREO_JACK"))
    )
    (comp (ref "GND174")
      (value "TP")
      (footprint "eagle-import:TP_1")
      (libsource (lib "eagle-import") (part "TP"))
    )
    (comp (ref "IC22")
      (value "SN74LVC1G125")
      (footprint "eagle-import:SOT23-5")
      (libsource (lib "eagle-import") (part "SN74LVC1G125"))
    )
    (comp (ref "IC23")
      (value "SN74LVC1G125")
      (footprint "eagle-import:SOT23-5")
      (libsource (lib "eagle-import") (part "SN74LVC1G125"))
    )
    (comp (ref "IC24")
      (value "SN74LVC1G125")
      (footprint "eagle-import:SOT23-5")
      (libsource (lib "eagle-import") (part "SN74LVC1G125"))
    )
    (comp (ref "IC25")
      (value "ATXMEGAxxxA4U-AU")
      (footprint "eagle-import:QFP80P1200X1200X120-44N")
      (libsource (lib "eagle-import") (part "AT-XMEGA-XXA4-AU"))
    )
    (comp (ref "IC26")
      (value "SI8645")
      (footprint "eagle-import:NSOIC-16")
      (libsource (lib "eagle-import") (part "SI8645"))
    )
    (comp (ref "IC27")
      (value "SN65HVD")
      (footprint "eagle-import:SO08")
      (libsource (lib "eagle-import") (part "SN65HVD"))
    )
    (comp (ref "IC33")
      (value "VHC1GT126")
      (footprint "eagle-import:SC-70-5")
      (libsource (lib "eagle-import") (part "VHC1GT126"))
    )
    (comp (ref "IC34")
      (value "VHC1GT126")
      (footprint "eagle-import:SC-70-5")
      (libsource (lib "eagle-import") (part "VHC1GT126"))
    )
    (comp (ref "IC35")
      (value "VHC1GT125")
      (footprint "eagle-import:SC-70-5")
      (libsource (lib "eagle-import") (part "VHC1GT125"))
    )
    (comp (ref "IN")
      (value "BNC")
      (footprint "eagle-import:BNC_RA")
      (libsource (lib "eagle-import") (part "BNC"))
    )
    (comp (ref "IN1")
      (value "22-05-7028-02")
      (footprint "eagle-import:7395-02")
      (libsource (lib "eagle-import") (part "22-?-0205-7028"))
    )
    (comp (ref "J1")
      (value "Port 1")
      (footprint "eagle-import:520426-4")
      (libsource (lib "eagle-import") (part "520426-4"))
    )
    (comp (ref "J2")
      (value "Port 1")
      (footprint "eagle-import:520426-4")
      (libsource (lib "eagle-import") (part "520426-4"))
    )
    (comp (ref "L12")
      (value "1u")
      (footprint "eagle-import:R0603")
      (libsource (lib "eagle-import") (part "R-EU_R0603"))
    )
    (comp (ref "OSC2")
      (value "OSCILLATOR")
      (footprint "eagle-import:OSCILLATOR_3.2X2.5")
      (libsource (lib "eagle-import") (part "OSCILLATOR"))
    )
    (comp (ref "OUT")
      (value "BNC")
      (footprint "eagle-import:BNC_RA")
      (libsource (lib "eagle-import") (part "BNC"))
    )
    (comp (ref "OUT1")
      (value "22-05-7028-02")
      (footprint "eagle-import:7395-02")
      (libsource (lib "eagle-import") (part "22-?-0205-7028"))
    )
    (comp (ref "PDI")
      (value "MA03-2")
      (footprint "eagle-import:MA03-2")
      (libsource (lib "eagle-import") (part "MA03-2"))
    )
    (comp (ref "R19")
      (value "3.16k")
      (footprint "eagle-import:R0402")
      (libsource (lib "eagle-import") (part "R-EU_R0402"))
    )
    (comp (ref "R61")
      (value "100k")
      (footprint "eagle-import:R0402")
      (libsource (lib "eagle-import") (part "R-EU_R0402"))
    )
    (comp (ref "R62")
      (value "3.16k")
      (footprint "eagle-import:R0402")
      (libsource (lib "eagle-import") (part "R-EU_R0402"))
    )
    (comp (ref "R63")
      (value "1k")
      (footprint "eagle-import:R0402")
      (libsource (lib "eagle-import") (part "R-EU_R0402"))
    )
    (comp (ref "R64")
      (value "100 NA")
      (footprint "eagle-import:R0402")
      (libsource (lib "eagle-import") (part "R-EU_R0402"))
    )
    (comp (ref "R65")
      (value "100 NA")
      (footprint "eagle-import:R0402")
      (libsource (lib "eagle-import") (part "R-EU_R0402"))
    )
    (comp (ref "R66")
      (value "68")
      (footprint "eagle-import:R0402")
      (libsource (lib "eagle-import") (part "R-EU_R0402"))
    )
    (comp (ref "STATE")
      (value "GREEN")
      (footprint "eagle-import:LED_HAND")
      (libsource (lib "eagle-import") (part "LEDHAND"))
    )
    (comp (ref "C34")
      (value "100nF")
      (footprint "eagle-import:C050-025X075")
      (libsource (lib "eagle-import") (part "C-US050-025X075"))
    )
    (comp (ref "C35")
      (value "47uF")
      (footprint "eagle-import:E2-5")
      (libsource (lib "eagle-import") (part "resistor_CPOL-EUE2-5"))
    )
    (comp (ref "C36")
      (value "4.7uF")
      (footprint "eagle-import:E2-5")
      (libsource (lib "eagle-import") (part "resistor_CPOL-EUE2-5"))
    )
    (comp (ref "C37")
      (value "100nF")
      (footprint "eagle-import:C050-025X075")
      (libsource (lib "eagle-import") (part "C-US050-025X075"))
    )
    (comp (ref "C38")
      (value "100pF")
      (footprint "eagle-import:C0603")
      (libsource (lib "eagle-import") (part "C-EUC0603"))
    )
    (comp (ref "C39")
      (value "100nF")
      (footprint "eagle-import:C050-025X075")
      (libsource (lib "eagle-import") (part "C-US050-025X075"))
    )
    (comp (ref "C40")
      (value "100nF")
      (footprint "eagle-import:C050-025X075")
      (libsource (lib "eagle-import") (part "C-US050-025X075"))
    )
    (comp (ref "C41")
      (value "100nF")
      (footprint "eagle-import:C050-025X075")
      (libsource (lib "eagle-import") (part "C-US050-025X075"))
    )
    (comp (ref "C42")
      (value "100nF")
      (footprint "eagle-import:C050-025X075")
      (libsource (lib "eagle-import") (part "C-US050-025X075"))
    )
    (comp (ref "C43")
      (value "100pF")
      (footprint "eagle-import:C050-025X075")
      (libsource (lib "eagle-import") (part "C-US050-025X075"))
    )
    (comp (ref "C44")
      (value "100pF")
      (footprint "eagle-import:C050-025X075")
      (libsource (lib "eagle-import") (part "C-US050-025X075"))
    )
    (comp (ref "C45")
      (value "4.7uF")
      (footprint "eagle-import:E2-5")
      (libsource (lib "eagle-import") (part "resistor_CPOL-EUE2-5"))
    )
    (comp (ref "C46")
      (value "4.7uF")
      (footprint "eagle-import:E2-5")
      (libsource (lib "eagle-import") (part "resistor_CPOL-EUE2-5"))
    )
    (comp (ref "C47")
      (value "5.6nF")
      (footprint "eagle-import:C050-025X075")
      (libsource (lib "eagle-import") (part "C-US050-025X075"))
    )
    (comp (ref "C48")
      (value "5.6nF")
      (footprint "eagle-import:C050-025X075")
      (libsource (lib "eagle-import") (part "C-US050-025X075"))
    )
    (comp (ref "C49")
      (value "100nF")
      (footprint "eagle-import:C050-025X075")
      (libsource (lib "eagle-import") (part "C-US050-025X075"))
    )
    (comp (ref "C50")
      (value "100nF")
      (footprint "eagle-import:C050-025X075")
      (libsource (lib "eagle-import") (part "C-US050-025X075"))
    )
    (comp (ref "C51")
      (value "2.7nF")
      (footprint "eagle-import:C050-025X075")
      (libsource (lib "eagle-import") (part "C-US050-025X075"))
    )
    (comp (ref "C52")
      (value "4.7uF")
      (footprint "eagle-import:E2-5")
      (libsource (lib "eagle-import") (part "resistor_CPOL-EUE2-5"))
    )
    (comp (ref "C53")
      (value "4.7uF")
      (footprint "eagle-import:E2-5")
      (libsource (lib "eagle-import") (part "resistor_CPOL-EUE2-5"))
    )
    (comp (ref "C54")
      (value "2.7nF")
      (footprint "eagle-import:C050-025X075")
      (libsource (lib "eagle-import") (part "C-US050-025X075"))
    )
    (comp (ref "C55")
      (value "100nF")
      (footprint "eagle-import:C050-025X075")
      (libsource (lib "eagle-import") (part "C-US050-025X075"))
    )
    (comp (ref "C56")
      (value "100nF")
      (footprint "eagle-import:C050-025X075")
      (libsource (lib "eagle-import") (part "C-US050-025X075"))
    )
    (comp (ref "C57")
      (value "3.9nF")
      (footprint "eagle-import:C050-025X075")
      (libsource (lib "eagle-import") (part "C-US050-025X075"))
    )
    (comp (ref "C58")
      (value "4.7uF")
      (footprint "eagle-import:E2-5")
      (libsource (lib "eagle-import") (part "resistor_CPOL-EUE2-5"))
    )
    (comp (ref "C59")
      (value "4.7uF")
      (footprint "eagle-import:E2-5")
      (libsource (lib "eagle-import") (part "resistor_CPOL-EUE2-5"))
    )
    (comp (ref "IC7")
      (value "AD797")
      (footprint "eagle-import:SO08")
      (libsource (lib "eagle-import") (part "AD797"))
    )
    (comp (ref "IC8")
      (value "AD797")
      (footprint "eagle-import:SO08")
      (libsource (lib "eagle-import") (part "AD797"))
    )
    (comp (ref "IC9")
      (value "AD797")
      (footprint "eagle-import:SO08")
      (libsource (lib "eagle-import") (part "AD797"))
    )
    (comp (ref "J3")
      (value "RCARCA")
      (footprint "eagle-import:RCA")
      (libsource (lib "eagle-import") (part "RCARCA"))
    )
    (comp (ref "R21")
      (value "2.21k")
      (footprint "eagle-import:0207_12")
      (libsource (lib "eagle-import") (part "resistor_R-EU_0207/12"))
    )
    (comp (ref "R22")
      (value "2.80k")
      (footprint "eagle-import:0207_12")
      (libsource (lib "eagle-import") (part "resistor_R-EU_0207/12"))
    )
    (comp (ref "R23")
      (value "2k")
      (footprint "eagle-import:0207_12")
      (libsource (lib "eagle-import") (part "resistor_R-EU_0207/12"))
    )
    (comp (ref "R24")
      (value "806")
      (footprint "eagle-import:0207_12")
      (libsource (lib "eagle-import") (part "resistor_R-EU_0207/12"))
    )
    (comp (ref "R25")
      (value "806")
      (footprint "eagle-import:0207_12")
      (libsource (lib "eagle-import") (part "resistor_R-EU_0207/12"))
    )
    (comp (ref "R26")
      (value "2k")
      (footprint "eagle-import:0207_12")
      (libsource (lib "eagle-import") (part "resistor_R-EU_0207/12"))
    )
    (comp (ref "R27")
      (value "100")
      (footprint "eagle-import:0207_12")
      (libsource (lib "eagle-import") (part "resistor_R-EU_0207/12"))
    )
    (comp (ref "R28")
      (value "100")
      (footprint "eagle-import:0207_12")
      (libsource (lib "eagle-import") (part "resistor_R-EU_0207/12"))
    )
    (comp (ref "R29")
      (value "2.0k")
      (footprint "eagle-import:0207_12")
      (libsource (lib "eagle-import") (part "resistor_R-EU_0207/12"))
    )
    (comp (ref "R30")
      (value "2.0k")
      (footprint "eagle-import:0207_12")
      (libsource (lib "eagle-import") (part "resistor_R-EU_0207/12"))
    )
    (comp (ref "R31")
      (value "681")
      (footprint "eagle-import:0207_12")
      (libsource (lib "eagle-import") (part "resistor_R-EU_0207/12"))
    )
    (comp (ref "R32")
      (value "681")
      (footprint "eagle-import:0207_12")
      (libsource (lib "eagle-import") (part "resistor_R-EU_0207/12"))
    )
    (comp (ref "R33")
      (value "226")
      (footprint "eagle-import:0207_12")
      (libsource (lib "eagle-import") (part "resistor_R-EU_0207/12"))
    )
    (comp (ref "R34")
      (value "226")
      (footprint "eagle-import:0207_12")
      (libsource (lib "eagle-import") (part "resistor_R-EU_0207/12"))
    )
    (comp (ref "R35")
      (value "324")
      (footprint "eagle-import:0207_12")
      (libsource (lib "eagle-import") (part "resistor_R-EU_0207/12"))
    )
    (comp (ref "R36")
      (value "324")
      (footprint "eagle-import:0207_12")
      (libsource (lib "eagle-import") (part "resistor_R-EU_0207/12"))
    )
    (comp (ref "R37")
      (value "100")
      (footprint "eagle-import:0207_12")
      (libsource (lib "eagle-import") (part "resistor_R-EU_0207/12"))
    )
    (comp (ref "R38")
      (value "332")
      (footprint "eagle-import:0207_12")
      (libsource (lib "eagle-import") (part "resistor_R-EU_0207/12"))
    )
    (comp (ref "C60")
      (value "4.7uF")
      (footprint "eagle-import:E2-5")
      (libsource (lib "eagle-import") (part "resistor_CPOL-EUE2-5"))
    )
    (comp (ref "C61")
      (value "100nF")
      (footprint "eagle-import:C050-025X075")
      (libsource (lib "eagle-import") (part "C-US050-025X075"))
    )
    (comp (ref "C62")
      (value "100pF")
      (footprint "eagle-import:C0603")
      (libsource (lib "eagle-import") (part "C-EUC0603"))
    )
    (comp (ref "C63")
      (value "100nF")
      (footprint "eagle-import:C050-025X075")
      (libsource (lib "eagle-import") (part "C-US050-025X075"))
    )
    (comp (ref "C64")
      (value "100nF")
      (footprint "eagle-import:C050-025X075")
      (libsource (lib "eagle-import") (part "C-US050-025X075"))
    )
    (comp (ref "C65")
      (value "100nF")
      (footprint "eagle-import:C050-025X075")
      (libsource (lib "eagle-import") (part "C-US050-025X075"))
    )
    (comp (ref "C66")
      (value "100nF")
      (footprint "eagle-import:C050-025X075")
      (libsource (lib "eagle-import") (part "C-US050-025X075"))
    )
    (comp (ref "C67")
      (value "100pF")
      (footprint "eagle-import:C050-025X075")
      (libsource (lib "eagle-import") (part "C-US050-025X075"))
    )
    (comp (ref "C68")
      (value "100pF")
      (footprint "eagle-import:C050-025X075")
      (libsource (lib "eagle-import") (part "C-US050-025X075"))
    )
    (comp (ref "C69")
      (value "4.7uF")
      (footprint "eagle-import:E2-5")
      (libsource (lib "eagle-import") (part "resistor_CPOL-EUE2-5"))
    )
    (comp (ref "C70")
      (value "4.7uF")
      (footprint "eagle-import:E2-5")
      (libsource (lib "eagle-import") (part "resistor_CPOL-EUE2-5"))
    )
    (comp (ref "C71")
      (value "5.6nF")
      (footprint "eagle-import:C050-025X075")
      (libsource (lib "eagle-import") (part "C-US050-025X075"))
    )
    (comp (ref "C72")
      (value "5.6nF")
      (footprint "eagle-import:C050-025X075")
      (libsource (lib "eagle-import") (part "C-US050-025X075"))
    )
    (comp (ref "C73")
      (value "100nF")
      (footprint "eagle-import:C050-025X075")
      (libsource (lib "eagle-import") (part "C-US050-025X075"))
    )
    (comp (ref "C74")
      (value "100nF")
      (footprint "eagle-import:C050-025X075")
      (libsource (lib "eagle-import") (part "C-US050-025X075"))
    )
    (comp (ref "C75")
      (value "2.7nF")
      (footprint "eagle-import:C050-025X075")
      (libsource (lib "eagle-import") (part "C-US050-025X075"))
    )
    (comp (ref "C76")
      (value "4.7uF")
      (footprint "eagle-import:E2-5")
      (libsource (lib "eagle-import") (part "resistor_CPOL-EUE2-5"))
    )
    (comp (ref "C77")
      (value "4.7uF")
      (footprint "eagle-import:E2-5")
      (libsource (lib "eagle-import") (part "resistor_CPOL-EUE2-5"))
    )
    (comp (ref "C78")
      (value "2.7nF")
      (footprint "eagle-import:C050-025X075")
      (libsource (lib "eagle-import") (part "C-US050-025X075"))
    )
    (comp (ref "C79")
      (value "100nF")
      (footprint "eagle-import:C050-025X075")
      (libsource (lib "eagle-import") (part "C-US050-025X075"))
    )
    (comp (ref "C80")
      (value "100nF")
      (footprint "eagle-import:C050-025X075")
      (libsource (lib "eagle-import") (part "C-US050-025X075"))
    )
    (comp (ref "C81")
      (value "3.9nF")
      (footprint "eagle-import:C050-025X075")
      (libsource (lib "eagle-import") (part "C-US050-025X075"))
    )
    (comp (ref "C82")
      (value "4.7uF")
      (footprint "eagle-import:E2-5")
      (libsource (lib "eagle-import") (part "resistor_CPOL-EUE2-5"))
    )
    (comp (ref "C83")
      (value "4.7uF")
      (footprint "eagle-import:E2-5")
      (libsource (lib "eagle-import") (part "resistor_CPOL-EUE2-5"))
    )
    (comp (ref "IC10")
      (value "AD797")
      (footprint "eagle-import:SO08")
      (libsource (lib "eagle-import") (part "AD797"))
    )
    (comp (ref "IC11")
      (value "AD797")
      (footprint "eagle-import:SO08")
      (libsource (lib "eagle-import") (part "AD797"))
    )
    (comp (ref "IC12")
      (value "AD797")
      (footprint "eagle-import:SO08")
      (libsource (lib "eagle-import") (part "AD797"))
    )
    (comp (ref "J4")
      (value "RCARCA")
      (footprint "eagle-import:RCA")
      (libsource (lib "eagle-import") (part "RCARCA"))
    )
    (comp (ref "R39")
      (value "2k")
      (footprint "eagle-import:0207_12")
      (libsource (lib "eagle-import") (part "resistor_R-EU_0207/12"))
    )
    (comp (ref "R40")
      (value "806")
      (footprint "eagle-import:0207_12")
      (libsource (lib "eagle-import") (part "resistor_R-EU_0207/12"))
    )
    (comp (ref "R41")
      (value "806")
      (footprint "eagle-import:0207_12")
      (libsource (lib "eagle-import") (part "resistor_R-EU_0207/12"))
    )
    (comp (ref "R42")
      (value "2k")
      (footprint "eagle-import:0207_12")
      (libsource (lib "eagle-import") (part "resistor_R-EU_0207/12"))
    )
    (comp (ref "R43")
      (value "100")
      (footprint "eagle-import:0207_12")
      (libsource (lib "eagle-import") (part "resistor_R-EU_0207/12"))
    )
    (comp (ref "R44")
      (value "100")
      (footprint "eagle-import:0207_12")
      (libsource (lib "eagle-import") (part "resistor_R-EU_0207/12"))
    )
    (comp (ref "R45")
      (value "2.0k")
      (footprint "eagle-import:0207_12")
      (libsource (lib "eagle-import") (part "resistor_R-EU_0207/12"))
    )
    (comp (ref "R46")
      (value "2.0k")
      (footprint "eagle-import:0207_12")
      (libsource (lib "eagle-import") (part "resistor_R-EU_0207/12"))
    )
    (comp (ref "R47")
      (value "681")
      (footprint "eagle-import:0207_12")
      (libsource (lib "eagle-import") (part "resistor_R-EU_0207/12"))
    )
    (comp (ref "R48")
      (value "681")
      (footprint "eagle-import:0207_12")
      (libsource (lib "eagle-import") (part "resistor_R-EU_0207/12"))
    )
    (comp (ref "R49")
      (value "226")
      (footprint "eagle-import:0207_12")
      (libsource (lib "eagle-import") (part "resistor_R-EU_0207/12"))
    )
    (comp (ref "R50")
      (value "226")
      (footprint "eagle-import:0207_12")
      (libsource (lib "eagle-import") (part "resistor_R-EU_0207/12"))
    )
    (comp (ref "R51")
      (value "324")
      (footprint "eagle-import:0207_12")
      (libsource (lib "eagle-import") (part "resistor_R-EU_0207/12"))
    )
    (comp (ref "R52")
      (value "324")
      (footprint "eagle-import:0207_12")
      (libsource (lib "eagle-import") (part "resistor_R-EU_0207/12"))
    )
    (comp (ref "R53")
      (value "100")
      (footprint "eagle-import:0207_12")
      (libsource (lib "eagle-import") (part "resistor_R-EU_0207/12"))
    )
    (comp (ref "R54")
      (value "332")
      (footprint "eagle-import:0207_12")
      (libsource (lib "eagle-import") (part "resistor_R-EU_0207/12"))
    )
    (comp (ref "C84")
      (value "100nF")
      (footprint "eagle-import:C0402")
      (libsource (lib "eagle-import") (part "C-EUC0402"))
    )
    (comp (ref "C85")
      (value "10uF")
      (footprint "eagle-import:C0603")
      (libsource (lib "eagle-import") (part "C-EUC0603"))
    )
    (comp (ref "C86")
      (value "10uF")
      (footprint "eagle-import:C0603")
      (libsource (lib "eagle-import") (part "C-EUC0603"))
    )
    (comp (ref "C87")
      (value "10uF")
      (footprint "eagle-import:C0603")
      (libsource (lib "eagle-import") (part "C-EUC0603"))
    )
    (comp (ref "C88")
      (value "100nF")
      (footprint "eagle-import:C0402")
      (libsource (lib "eagle-import") (part "C-EUC0402"))
    )
    (comp (ref "C89")
      (value "100nF")
      (footprint "eagle-import:C0402")
      (libsource (lib "eagle-import") (part "C-EUC0402"))
    )
    (comp (ref "C90")
      (value "100nF")
      (footprint "eagle-import:C0402")
      (libsource (lib "eagle-import") (part "C-EUC0402"))
    )
    (comp (ref "C91")
      (value "10uF")
      (footprint "eagle-import:C0603")
      (libsource (lib "eagle-import") (part "C-EUC0603"))
    )
    (comp (ref "C92")
      (value "100nF")
      (footprint "eagle-import:C0402")
      (libsource (lib "eagle-import") (part "C-EUC0402"))
    )
    (comp (ref "C93")
      (value "100nF")
      (footprint "eagle-import:C0402")
      (libsource (lib "eagle-import") (part "C-EUC0402"))
    )
    (comp (ref "C94")
      (value "100nF")
      (footprint "eagle-import:C0402")
      (libsource (lib "eagle-import") (part "C-EUC0402"))
    )
    (comp (ref "C95")
      (value "100nF")
      (footprint "eagle-import:C0402")
      (libsource (lib "eagle-import") (part "C-EUC0402"))
    )
    (comp (ref "C96")
      (value "100nF")
      (footprint "eagle-import:C0402")
      (libsource (lib "eagle-import") (part "C-EUC0402"))
    )
    (comp (ref "C97")
      (value "100nF")
      (footprint "eagle-import:C0402")
      (libsource (lib "eagle-import") (part "C-EUC0402"))
    )
    (comp (ref "C98")
      (value "100nF")
      (footprint "eagle-import:C0402")
      (libsource (lib "eagle-import") (part "C-EUC0402"))
    )
    (comp (ref "C99")
      (value "100nF")
      (footprint "eagle-import:C0402")
      (libsource (lib "eagle-import") (part "C-EUC0402"))
    )
    (comp (ref "C100")
      (value "10uF")
      (footprint "eagle-import:C0603")
      (libsource (lib "eagle-import") (part "C-EUC0603"))
    )
    (comp (ref "C101")
      (value "100nF")
      (footprint "eagle-import:C0402")
      (libsource (lib "eagle-import") (part "C-EUC0402"))
    )
    (comp (ref "C102")
      (value "100nF")
      (footprint "eagle-import:C0402")
      (libsource (lib "eagle-import") (part "C-EUC0402"))
    )
    (comp (ref "C138")
      (value "100nF")
      (footprint "eagle-import:C0402")
      (libsource (lib "eagle-import") (part "C-EUC0402"))
    )
    (comp (ref "C139")
      (value "100nF")
      (footprint "eagle-import:C0402")
      (libsource (lib "eagle-import") (part "C-EUC0402"))
    )
    (comp (ref "C141")
      (value "100nF")
      (footprint "eagle-import:C0402")
      (libsource (lib "eagle-import") (part "C-EUC0402"))
    )
    (comp (ref "C142")
      (value "100nF")
      (footprint "eagle-import:C0402")
      (libsource (lib "eagle-import") (part "C-EUC0402"))
    )
    (comp (ref "CUSB1")
      (value "4.7nF")
      (footprint "eagle-import:C0402")
      (libsource (lib "eagle-import") (part "C-EUC0402"))
    )
    (comp (ref "GND176")
      (value "TP")
      (footprint "eagle-import:TP_1")
      (libsource (lib "eagle-import") (part "TP"))
    )
    (comp (ref "IC13")
      (value "S34ML")
      (footprint "eagle-import:TSOP-48")
      (libsource (lib "eagle-import") (part "S34ML"))
    )
    (comp (ref "IC14")
      (value "TPS73801")
      (footprint "eagle-import:SOT223-6")
      (libsource (lib "eagle-import") (part "TPS73801"))
    )
    (comp (ref "IC15")
      (value "USBLC6-2SC6")
      (footprint "eagle-import:SOT23-6L")
      (libsource (lib "eagle-import") (part "USBLC6-2"))
    )
    (comp (ref "IC16")
      (value "PIC32MZ2048EFM100")
      (footprint "eagle-import:TQFP-100")
      (libsource (lib "eagle-import") (part "PIC32MZ2048EFM100"))
    )
    (comp (ref "IC18")
      (value "LP5907MFX-3.3")
      (footprint "eagle-import:TSOT23-5")
      (libsource (lib "eagle-import") (part "TLV700XX"))
    )
    (comp (ref "JP1")
      (value "M06NO_SILK")
      (footprint "eagle-import:1X06_NO_SILK")
      (libsource (lib "eagle-import") (part "M06NO_SILK"))
    )
    (comp (ref "L9")
      (value "600@100M")
      (footprint "eagle-import:R0805")
      (libsource (lib "eagle-import") (part "R-EU_R0805"))
    )
    (comp (ref "L13")
      (value "???")
      (footprint "eagle-import:R0805")
      (libsource (lib "eagle-import") (part "R-EU_R0805"))
    )
    (comp (ref "OSC1")
      (value "OSCILLATOR2.5X2.0MM")
      (footprint "eagle-import:CRYSTAL_2.5X2.0MM")
      (libsource (lib "eagle-import") (part "OSCILLATOR2.5X2.0MM"))
    )
    (comp (ref "OSC3")
      (value "XOSC_2.5X2.0MM")
      (footprint "eagle-import:CRYSTAL_2.5X2.0MM")
      (libsource (lib "eagle-import") (part "XOSC_2.5X2.0MM"))
    )
    (comp (ref "R55")
      (value "3.16k")
      (footprint "eagle-import:R0402")
      (libsource (lib "eagle-import") (part "R-EU_R0402"))
    )
    (comp (ref "R56")
      (value "10k")
      (footprint "eagle-import:R0402")
      (libsource (lib "eagle-import") (part "R-EU_R0402"))
    )
    (comp (ref "R57")
      (value "1k")
      (footprint "eagle-import:R0402")
      (libsource (lib "eagle-import") (part "R-EU_R0402"))
    )
    (comp (ref "R60")
      (value "3.16k")
      (footprint "eagle-import:R0402")
      (libsource (lib "eagle-import") (part "R-EU_R0402"))
    )
    (comp (ref "R71")
      (value "3.16k")
      (footprint "eagle-import:R0402")
      (libsource (lib "eagle-import") (part "R-EU_R0402"))
    )
    (comp (ref "R74")
      (value "9.76k")
      (footprint "eagle-import:R0402")
      (libsource (lib "eagle-import") (part "R-EU_R0402"))
    )
    (comp (ref "R75")
      (value "2050")
      (footprint "eagle-import:R0402")
      (libsource (lib "eagle-import") (part "R-EU_R0402"))
    )
    (comp (ref "R76")
      (value "2050")
      (footprint "eagle-import:R0402")
      (libsource (lib "eagle-import") (part "R-EU_R0402"))
    )
    (comp (ref "R77")
      (value "2050")
      (footprint "eagle-import:R0402")
      (libsource (lib "eagle-import") (part "R-EU_R0402"))
    )
    (comp (ref "RUSB1")
      (value "1M")
      (footprint "eagle-import:R0402")
      (libsource (lib "eagle-import") (part "R-EU_R0402"))
    )
    (comp (ref "SW1")
      (value "SW1\"")
      (footprint "eagle-import:SWITCH_KSS")
      (libsource (lib "eagle-import") (part "SW1{dblquote}"))
    )
    (comp (ref "TP0")
      (value "TP")
      (footprint "eagle-import:TP_1")
      (libsource (lib "eagle-import") (part "TP"))
    )
    (comp (ref "TP1")
      (value "TP")
      (footprint "eagle-import:TP_1")
      (libsource (lib "eagle-import") (part "TP"))
    )
    (comp (ref "TX1")
      (value "RED")
      (footprint "eagle-import:LED_HAND")
      (libsource (lib "eagle-import") (part "LEDHAND"))
    )
    (comp (ref "TX2")
      (value "RED")
      (footprint "eagle-import:LED_HAND")
      (libsource (lib "eagle-import") (part "LEDHAND"))
    )
    (comp (ref "TX3")
      (value "RED")
      (footprint "eagle-import:LED_HAND")
      (libsource (lib "eagle-import") (part "LEDHAND"))
    )
    (comp (ref "USB1")
      (value "USB_MICRO_B")
      (footprint "eagle-import:ZX62D-B-5P8")
      (libsource (lib "eagle-import") (part "USB_MICRO_B"))
    )
    (comp (ref "C103")
      (value "10uF")
      (footprint "eagle-import:C0603")
      (libsource (lib "eagle-import") (part "C-EUC0603"))
    )
    (comp (ref "C106")
      (value "100nF")
      (footprint "eagle-import:C0402")
      (libsource (lib "eagle-import") (part "C-EUC0402"))
    )
    (comp (ref "C107")
      (value "47pF")
      (footprint "eagle-import:C0402")
      (libsource (lib "eagle-import") (part "C-EUC0402"))
    )
    (comp (ref "C108")
      (value "47pF")
      (footprint "eagle-import:C0402")
      (libsource (lib "eagle-import") (part "C-EUC0402"))
    )
    (comp (ref "C109")
      (value "100nF")
      (footprint "eagle-import:C0402")
      (libsource (lib "eagle-import") (part "C-EUC0402"))
    )
    (comp (ref "C110")
      (value "10uF")
      (footprint "eagle-import:C0603")
      (libsource (lib "eagle-import") (part "C-EUC0603"))
    )
    (comp (ref "C111")
      (value "100nF")
      (footprint "eagle-import:C0402")
      (libsource (lib "eagle-import") (part "C-EUC0402"))
    )
    (comp (ref "C112")
      (value "4.7uF")
      (footprint "eagle-import:A_3216-18W")
      (libsource (lib "eagle-import") (part "CPOL-EUA/3216-18W"))
    )
    (comp (ref "C113")
      (value "100nF")
      (footprint "eagle-import:C0402")
      (libsource (lib "eagle-import") (part "C-EUC0402"))
    )
    (comp (ref "C114")
      (value "100nF")
      (footprint "eagle-import:C0402")
      (libsource (lib "eagle-import") (part "C-EUC0402"))
    )
    (comp (ref "C115")
      (value "10uF")
      (footprint "eagle-import:C0603")
      (libsource (lib "eagle-import") (part "C-EUC0603"))
    )
    (comp (ref "C116")
      (value "10uF")
      (footprint "eagle-import:C0603")
      (libsource (lib "eagle-import") (part "C-EUC0603"))
    )
    (comp (ref "C117")
      (value "100nF")
      (footprint "eagle-import:C0402")
      (libsource (lib "eagle-import") (part "C-EUC0402"))
    )
    (comp (ref "C118")
      (value "100nF")
      (footprint "eagle-import:C0402")
      (libsource (lib "eagle-import") (part "C-EUC0402"))
    )
    (comp (ref "CUSB2")
      (value "4.7nF")
      (footprint "eagle-import:C0402")
      (libsource (lib "eagle-import") (part "C-EUC0402"))
    )
    (comp (ref "IC17")
      (value "USBLC6-2SC6")
      (footprint "eagle-import:SOT23-6L")
      (libsource (lib "eagle-import") (part "USBLC6-2"))
    )
    (comp (ref "IC19")
      (value "FT232RL")
      (footprint "eagle-import:SSOP28")
      (libsource (lib "eagle-import") (part "FT232RL"))
    )
    (comp (ref "IC20")
      (value "LP5907MFX-3.3")
      (footprint "eagle-import:TSOT23-5")
      (libsource (lib "eagle-import") (part "TLV700XX"))
    )
    (comp (ref "IC21")
      (value "SI8642BC-B-IS1")
      (footprint "eagle-import:NSOIC-16")
      (libsource (lib "eagle-import") (part "SI8645"))
    )
    (comp (ref "IC32")
      (value "TPS73801")
      (footprint "eagle-import:SOT223-6")
      (libsource (lib "eagle-import") (part "TPS73801"))
    )
    (comp (ref "L10")
      (value "???")
      (footprint "eagle-import:R0805")
      (libsource (lib "eagle-import") (part "R-EU_R0805"))
    )
    (comp (ref "L11")
      (value "600@100M")
      (footprint "eagle-import:R0805")
      (libsource (lib "eagle-import") (part "R-EU_R0805"))
    )
    (comp (ref "R58")
      (value "2050 NA")
      (footprint "eagle-import:R0402")
      (libsource (lib "eagle-import") (part "R-EU_R0402"))
    )
    (comp (ref "R59")
      (value "680 NA")
      (footprint "eagle-import:R0402")
      (libsource (lib "eagle-import") (part "R-EU_R0402"))
    )
    (comp (ref "R72")
      (value "3.16k")
      (footprint "eagle-import:R0402")
      (libsource (lib "eagle-import") (part "R-EU_R0402"))
    )
    (comp (ref "R73")
      (value "9.76k")
      (footprint "eagle-import:R0402")
      (libsource (lib "eagle-import") (part "R-EU_R0402"))
    )
    (comp (ref "RUSB2")
      (value "1M")
      (footprint "eagle-import:R0402")
      (libsource (lib "eagle-import") (part "R-EU_R0402"))
    )
    (comp (ref "RX")
      (value "GREEN NA")
      (footprint "eagle-import:LED_HAND")
      (libsource (lib "eagle-import") (part "LEDHAND"))
    )
    (comp (ref "TX")
      (value "RED NA")
      (footprint "eagle-import:LED_HAND")
      (libsource (lib "eagle-import") (part "LEDHAND"))
    )
    (comp (ref "USB2")
      (value "USB_MINI_B")
      (footprint "eagle-import:240-0002-1")
      (libsource (lib "eagle-import") (part "USB_MINI_B"))
    )
  )
  (nets
    (net (code "1") (name "+5V") (class "Default")
      (node (ref "C103") (pin "1") (pinfunction "1_1") (pintype "passive"))
      (node (ref "C115") (pin "1") (pinfunction "1_1") (pintype "passive"))
      (node (ref "IC20") (pin "1") (pinfunction "IN_1") (pintype "bidirectional"))
      (node (ref "IC20") (pin "3") (pinfunction "EN_3") (pintype "bidirectional"))
      (node (ref "IC32") (pin "P$2") (pinfunction "OUT_P$2") (pintype "bidirectional"))
      (node (ref "JP2") (pin "1") (pinfunction "1_1") (pintype "passive"))
      (node (ref "R73") (pin "2") (pinfunction "2_2") (pintype "passive"))
      (node (ref "X1") (pin "P2") (pinfunction "2_P2") (pintype "passive"))
    )
    (net (code "2") (name "+12V") (class "Default")
      (node (ref "C3") (pin "2") (pinfunction "2_2") (pintype "passive"))
      (node (ref "C36") (pin "+") (pinfunction "+_+") (pintype "passive"))
      (node (ref "C37") (pin "1") (pinfunction "1_1") (pintype "passive"))
      (node (ref "C41") (pin "1") (pinfunction "1_1") (pintype "passive"))
      (node (ref "C45") (pin "+") (pinfunction "+_+") (pintype "passive"))
      (node (ref "C49") (pin "1") (pinfunction "1_1") (pintype "passive"))
      (node (ref "C5") (pin "1") (pinfunction "1_1") (pintype "passive"))
      (node (ref "C52") (pin "+") (pinfunction "+_+") (pintype "passive"))
      (node (ref "C55") (pin "1") (pinfunction "1_1") (pintype "passive"))
      (node (ref "C58") (pin "+") (pinfunction "+_+") (pintype "passive"))
      (node (ref "C60") (pin "+") (pinfunction "+_+") (pintype "passive"))
      (node (ref "C61") (pin "1") (pinfunction "1_1") (pintype "passive"))
      (node (ref "C65") (pin "1") (pinfunction "1_1") (pintype "passive"))
      (node (ref "C69") (pin "+") (pinfunction "+_+") (pintype "passive"))
      (node (ref "C73") (pin "1") (pinfunction "1_1") (pintype "passive"))
      (node (ref "C76") (pin "+") (pinfunction "+_+") (pintype "passive"))
      (node (ref "C79") (pin "1") (pinfunction "1_1") (pintype "passive"))
      (node (ref "C82") (pin "+") (pinfunction "+_+") (pintype "passive"))
      (node (ref "IC1") (pin "5") (pinfunction "OUT_5") (pintype "bidirectional"))
      (node (ref "IC10") (pin "7") (pinfunction "V+_7") (pintype "power_in"))
      (node (ref "IC11") (pin "7") (pinfunction "V+_7") (pintype "power_in"))
      (node (ref "IC12") (pin "7") (pinfunction "V+_7") (pintype "power_in"))
      (node (ref "IC7") (pin "7") (pinfunction "V+_7") (pintype "power_in"))
      (node (ref "IC8") (pin "7") (pinfunction "V+_7") (pintype "power_in"))
      (node (ref "IC9") (pin "7") (pinfunction "V+_7") (pintype "power_in"))
      (node (ref "R1") (pin "1") (pinfunction "1_1") (pintype "passive"))
      (node (ref "R2") (pin "1") (pinfunction "1_1") (pintype "passive"))
      (node (ref "R23") (pin "2") (pinfunction "2_2") (pintype "passive"))
      (node (ref "R26") (pin "2") (pinfunction "2_2") (pintype "passive"))
      (node (ref "R39") (pin "2") (pinfunction "2_2") (pintype "passive"))
      (node (ref "R42") (pin "2") (pinfunction "2_2") (pintype "passive"))
    )
    (net (code "3") (name "+15V") (class "Default")
      (node (ref "C1") (pin "1") (pinfunction "1_1") (pintype "passive"))
      (node (ref "C4") (pin "1") (pinfunction "1_1") (pintype "passive"))
      (node (ref "IC1") (pin "1") (pinfunction "IN_1") (pintype "bidirectional"))
      (node (ref "L1") (pin "1") (pinfunction "1_1") (pintype "passive"))
      (node (ref "R5") (pin "2") (pinfunction "2_2") (pintype "passive"))
      (node (ref "R6") (pin "2") (pinfunction "2_2") (pintype "passive"))
    )
    (net (code "4") (name "-12V") (class "Default")
      (node (ref "C15") (pin "2") (pinfunction "2_2") (pintype "passive"))
      (node (ref "C16") (pin "1") (pinfunction "1_1") (pintype "passive"))
      (node (ref "C42") (pin "2") (pinfunction "2_2") (pintype "passive"))
      (node (ref "C46") (pin "-") (pinfunction "-_-") (pintype "passive"))
      (node (ref "C50") (pin "2") (pinfunction "2_2") (pintype "passive"))
      (node (ref "C53") (pin "-") (pinfunction "-_-") (pintype "passive"))
      (node (ref "C56") (pin "2") (pinfunction "2_2") (pintype "passive"))
      (node (ref "C59") (pin "-") (pinfunction "-_-") (pintype "passive"))
      (node (ref "C66") (pin "2") (pinfunction "2_2") (pintype "passive"))
      (node (ref "C70") (pin "-") (pinfunction "-_-") (pintype "passive"))
      (node (ref "C74") (pin "2") (pinfunction "2_2") (pintype "passive"))
      (node (ref "C77") (pin "-") (pinfunction "-_-") (pintype "passive"))
      (node (ref "C80") (pin "2") (pinfunction "2_2") (pintype "passive"))
      (node (ref "C83") (pin "-") (pinfunction "-_-") (pintype "passive"))
      (node (ref "IC10") (pin "4") (pinfunction "V-_4") (pintype "power_in"))
      (node (ref "IC11") (pin "4") (pinfunction "V-_4") (pintype "power_in"))
      (node (ref "IC12") (pin "4") (pinfunction "V-_4") (pintype "power_in"))
      (node (ref "IC3") (pin "5") (pinfunction "OUT_5") (pintype "bidirectional"))
      (node (ref "IC7") (pin "4") (pinfunction "V-_4") (pintype "power_in"))
      (node (ref "IC8") (pin "4") (pinfunction "V-_4") (pintype "power_in"))
      (node (ref "IC9") (pin "4") (pinfunction "V-_4") (pintype "power_in"))
      (node (ref "R11") (pin "1") (pinfunction "1_1") (pintype "passive"))
      (node (ref "R14") (pin "1") (pinfunction "1_1") (pintype "passive"))
    )
    (net (code "5") (name "-15V") (class "Default")
      (node (ref "C17") (pin "1") (pinfunction "1_1") (pintype "passive"))
      (node (ref "C9") (pin "1") (pinfunction "1_1") (pintype "passive"))
      (node (ref "IC3") (pin "2") (pinfunction "IN_2") (pintype "bidirectional"))
      (node (ref "L4") (pin "2") (pinfunction "2_2") (pintype "passive"))
      (node (ref "R12") (pin "1") (pinfunction "1_1") (pintype "passive"))
      (node (ref "R17") (pin "1") (pinfunction "1_1") (pintype "passive"))
    )
    (net (code "6") (name "A5V0") (class "Default")
      (node (ref "C18") (pin "2") (pinfunction "2_2") (pintype "passive"))
      (node (ref "C20") (pin "2") (pinfunction "2_2") (pintype "passive"))
      (node (ref "C22") (pin "2") (pinfunction "2_2") (pintype "passive"))
      (node (ref "IC4") (pin "1") (pinfunction "OUT_1") (pintype "bidirectional"))
      (node (ref "IC4") (pin "2") (pinfunction "OUT_2") (pintype "bidirectional"))
      (node (ref "L8") (pin "1") (pinfunction "1_1") (pintype "passive"))
      (node (ref "R21") (pin "2") (pinfunction "2_2") (pintype "passive"))
    )
    (net (code "7") (name "ADC0") (class "Default")
      (node (ref "R60") (pin "1") (pinfunction "1_1") (pintype "passive"))
      (node (ref "R62") (pin "1") (pinfunction "1_1") (pintype "passive"))
      (node (ref "X1") (pin "P7") (pinfunction "7_P7") (pintype "passive"))
    )
    (net (code "8") (name "ADC0_EZ") (class "Default")
      (node (ref "C141") (pin "1") (pinfunction "1_1") (pintype "passive"))
      (node (ref "IC16") (pin "41") (pinfunction "EBIA11/AN7/ERXD0/AECRS/PMA11/RB12_41") (pintype "bidirectional"))
      (node (ref "R60") (pin "2") (pinfunction "2_2") (pintype "passive"))
    )
    (net (code "9") (name "ADC1") (class "Default")
      (node (ref "R19") (pin "1") (pinfunction "1_1") (pintype "passive"))
      (node (ref "R71") (pin "1") (pinfunction "1_1") (pintype "passive"))
      (node (ref "X1") (pin "P6") (pinfunction "6_P6") (pintype "passive"))
    )
    (net (code "10") (name "ADC1_EZ") (class "Default")
      (node (ref "C142") (pin "1") (pinfunction "1_1") (pintype "passive"))
      (node (ref "IC16") (pin "42") (pinfunction "AN8/ERXD1/AECOL/RB13_42") (pintype "bidirectional"))
      (node (ref "R71") (pin "2") (pinfunction "2_2") (pintype "passive"))
    )
    (net (code "11") (name "ALE") (class "Default")
      (node (ref "IC13") (pin "P17") (pinfunction "ALE_P17") (pintype "bidirectional"))
      (node (ref "IC16") (pin "11") (pinfunction "EBIA4/AN13/C1INC/ECRS/RPG7/SDA4/PMA4..._11") (pintype "bidirectional"))
    )
    (net (code "12") (name "AUDIO") (class "Default")
      (node (ref "IC16") (pin "86") (pinfunction "EBID10/ETXD0/RPF1/PMD10/RF1_86") (pintype "bidirectional"))
      (node (ref "R76") (pin "2") (pinfunction "2_2") (pintype "passive"))
    )
    (net (code "13") (name "BUSY") (class "Default")
      (node (ref "IC13") (pin "P7") (pinfunction "R/B#_P7") (pintype "bidirectional"))
      (node (ref "IC16") (pin "16") (pinfunction "EBIA2/AN11/C2INC/ERXCLK/EREFCLK..._16") (pintype "bidirectional"))
    )
    (net (code "14") (name "CE") (class "Default")
      (node (ref "IC13") (pin "P9") (pinfunction "CE#_P9") (pintype "bidirectional"))
      (node (ref "IC16") (pin "79") (pinfunction "EBID12/ETXD2/RPD12..._79") (pintype "bidirectional"))
    )
    (net (code "15") (name "CLE") (class "Default")
      (node (ref "IC13") (pin "P16") (pinfunction "CLE_P16") (pintype "bidirectional"))
      (node (ref "IC16") (pin "80") (pinfunction "EBID13/ETXD3/PMD13/RD13_80") (pintype "bidirectional"))
    )
    (net (code "16") (name "CLK_IN") (class "Default")
      (node (ref "CLKIN") (pin "4") (pinfunction "4_4") (pintype "passive"))
      (node (ref "IC22") (pin "2") (pinfunction "P$2_2") (pintype "bidirectional"))
    )
    (net (code "17") (name "CLK_SYNC") (class "Default")
      (node (ref "IC22") (pin "4") (pinfunction "P$4_4") (pintype "bidirectional"))
      (node (ref "IC25") (pin "12") (pinfunction "PC2/OC0C/RXD0_12") (pintype "bidirectional"))
    )
    (net (code "18") (name "CTS") (class "Default")
      (node (ref "IC21") (pin "11") (pinfunction "B4_11") (pintype "bidirectional"))
      (node (ref "IC25") (pin "29") (pinfunction "~XCK0OC0BSCLPE1_29") (pintype "bidirectional"))
    )
    (net (code "19") (name "D+") (class "Default")
      (node (ref "IC15") (pin "P$4") (pinfunction "IO2_P$4") (pintype "bidirectional"))
      (node (ref "IC16") (pin "55") (pinfunction "D+_55") (pintype "bidirectional"))
    )
    (net (code "20") (name "D-") (class "Default")
      (node (ref "IC15") (pin "P$6") (pinfunction "IO1_P$6") (pintype "bidirectional"))
      (node (ref "IC16") (pin "54") (pinfunction "D-_54") (pintype "bidirectional"))
    )
    (net (code "21") (name "D5V") (class "Default")
      (node (ref "C85") (pin "1") (pinfunction "1_1") (pintype "passive"))
      (node (ref "C87") (pin "1") (pinfunction "1_1") (pintype "passive"))
      (node (ref "IC14") (pin "P$2") (pinfunction "OUT_P$2") (pintype "bidirectional"))
      (node (ref "IC18") (pin "1") (pinfunction "IN_1") (pintype "bidirectional"))
      (node (ref "IC18") (pin "3") (pinfunction "EN_3") (pintype "bidirectional"))
      (node (ref "R74") (pin "2") (pinfunction "2_2") (pintype "passive"))
    )
    (net (code "22") (name "D5V0") (class "Default")
      (node (ref "C19") (pin "2") (pinfunction "2_2") (pintype "passive"))
      (node (ref "C21") (pin "2") (pinfunction "2_2") (pintype "passive"))
      (node (ref "C23") (pin "2") (pinfunction "2_2") (pintype "passive"))
      (node (ref "IC5") (pin "1") (pinfunction "OUT_1") (pintype "bidirectional"))
      (node (ref "IC5") (pin "2") (pinfunction "OUT_2") (pintype "bidirectional"))
      (node (ref "L7") (pin "1") (pinfunction "1_1") (pintype "passive"))
    )
    (net (code "23") (name "DAC_~{RST}") (class "Default")
      (node (ref "IC16") (pin "65") (pinfunction "EBIA8/RPF5/SCL5/PMA8/RF5_65") (pintype "bidirectional"))
      (node (ref "IC6") (pin "P23") (pinfunction "~{PD/RST}_P23") (pintype "bidirectional"))
      (node (ref "R20") (pin "1") (pinfunction "1_1") (pintype "passive"))
    )
    (net (code "24") (name "EN_DCDC") (class "Default")
      (node (ref "IC2") (pin "11") (pinfunction "EN2_11") (pintype "bidirectional"))
      (node (ref "IC2") (pin "9") (pinfunction "EN1_9") (pintype "bidirectional"))
      (node (ref "IC25") (pin "24") (pinfunction "~{#SSPD4}_24") (pintype "bidirectional"))
      (node (ref "R9") (pin "1") (pinfunction "1_1") (pintype "passive"))
    )
    (net (code "25") (name "EN_IN0") (class "Default")
      (node (ref "IC24") (pin "1") (pinfunction "P$1_1") (pintype "bidirectional"))
      (node (ref "IC26") (pin "6") (pinfunction "A4_6") (pintype "bidirectional"))
    )
    (net (code "26") (name "EN_N12V") (class "Default")
      (node (ref "IC16") (pin "77") (pinfunction "EBID14/ETXEN/RPD2..._77") (pintype "bidirectional"))
      (node (ref "IC3") (pin "3") (pinfunction "EN_3") (pintype "bidirectional"))
      (node (ref "R78") (pin "1") (pinfunction "1_1") (pintype "passive"))
    )
    (net (code "27") (name "EN_P12V") (class "Default")
      (node (ref "IC1") (pin "3") (pinfunction "EN_3") (pintype "bidirectional"))
      (node (ref "IC16") (pin "76") (pinfunction "RPD1/SCK1/RD1_76") (pintype "bidirectional"))
      (node (ref "R79") (pin "1") (pinfunction "1_1") (pintype "passive"))
    )
    (net (code "28") (name "FILTB") (class "Default")
      (node (ref "C28") (pin "+") (pinfunction "+_+") (pintype "passive"))
      (node (ref "C32") (pin "1") (pinfunction "1_1") (pintype "passive"))
      (node (ref "IC6") (pin "P16") (pinfunction "FILTB_P16") (pintype "bidirectional"))
    )
    (net (code "29") (name "FT_CTS") (class "Default")
      (node (ref "IC19") (pin "11") (pinfunction "~{CTS}_11") (pintype "input"))
      (node (ref "IC21") (pin "6") (pinfunction "A4_6") (pintype "bidirectional"))
    )
    (net (code "30") (name "FT_RTS") (class "Default")
      (node (ref "IC19") (pin "3") (pinfunction "~{RTS}_3") (pintype "output"))
      (node (ref "IC21") (pin "4") (pinfunction "A2_4") (pintype "bidirectional"))
    )
    (net (code "31") (name "FT_RXD") (class "Default")
      (node (ref "IC19") (pin "5") (pinfunction "RXD_5") (pintype "input"))
      (node (ref "IC21") (pin "5") (pinfunction "A3_5") (pintype "bidirectional"))
    )
    (net (code "32") (name "FT_TXD") (class "Default")
      (node (ref "IC19") (pin "1") (pinfunction "TXD_1") (pintype "output"))
      (node (ref "IC21") (pin "3") (pinfunction "A1_3") (pintype "bidirectional"))
    )
    (net (code "33") (name "GND") (class "Default")
      (node (ref "C1") (pin "2") (pinfunction "2_2") (pintype "passive"))
      (node (ref "C10") (pin "2") (pinfunction "2_2") (pintype "passive"))
      (node (ref "C100") (pin "2") (pinfunction "2_2") (pintype "passive"))
      (node (ref "C101") (pin "2") (pinfunction "2_2") (pintype "passive"))
      (node (ref "C102") (pin "2") (pinfunction "2_2") (pintype "passive"))
      (node (ref "C103") (pin "2") (pinfunction "2_2") (pintype "passive"))
      (node (ref "C104") (pin "2") (pinfunction "2_2") (pintype "passive"))
      (node (ref "C105") (pin "2") (pinfunction "2_2") (pintype "passive"))
      (node (ref "C109") (pin "1") (pinfunction "1_1") (pintype "passive"))
      (node (ref "C11") (pin "2") (pinfunction "2_2") (pintype "passive"))
      (node (ref "C110") (pin "1") (pinfunction "1_1") (pintype "passive"))
      (node (ref "C115") (pin "2") (pinfunction "2_2") (pintype "passive"))
      (node (ref "C116") (pin "2") (pinfunction "2_2") (pintype "passive"))
      (node (ref "C118") (pin "2") (pinfunction "2_2") (pintype "passive"))
      (node (ref "C119") (pin "2") (pinfunction "2_2") (pintype "passive"))
      (node (ref "C12") (pin "2") (pinfunction "2_2") (pintype "passive"))
      (node (ref "C120") (pin "2") (pinfunction "2_2") (pintype "passive"))
      (node (ref "C121") (pin "2") (pinfunction "2_2") (pintype "passive"))
      (node (ref "C122") (pin "2") (pinfunction "2_2") (pintype "passive"))
      (node (ref "C123") (pin "2") (pinfunction "2_2") (pintype "passive"))
      (node (ref "C124") (pin "2") (pinfunction "2_2") (pintype "passive"))
      (node (ref "C125") (pin "2") (pinfunction "2_2") (pintype "passive"))
      (node (ref "C126") (pin "2") (pinfunction "2_2") (pintype "passive"))
      (node (ref "C127") (pin "2") (pinfunction "2_2") (pintype "passive"))
      (node (ref "C128") (pin "2") (pinfunction "2_2") (pintype "passive"))
      (node (ref "C129") (pin "2") (pinfunction "2_2") (pintype "passive"))
      (node (ref "C13") (pin "2") (pinfunction "2_2") (pintype "passive"))
      (node (ref "C130") (pin "2") (pinfunction "2_2") (pintype "passive"))
      (node (ref "C131") (pin "2") (pinfunction "2_2") (pintype "passive"))
      (node (ref "C132") (pin "2") (pinfunction "2_2") (pintype "passive"))
      (node (ref "C133") (pin "2") (pinfunction "2_2") (pintype "passive"))
      (node (ref "C134") (pin "2") (pinfunction "2_2") (pintype "passive"))
      (node (ref "C135") (pin "2") (pinfunction "2_2") (pintype "passive"))
      (node (ref "C136") (pin "2") (pinfunction "2_2") (pintype "passive"))
      (node (ref "C137") (pin "2") (pinfunction "2_2") (pintype "passive"))
      (node (ref "C138") (pin "2") (pinfunction "2_2") (pintype "passive"))
      (node (ref "C139") (pin "2") (pinfunction "2_2") (pintype "passive"))
      (node (ref "C14") (pin "2") (pinfunction "2_2") (pintype "passive"))
      (node (ref "C140") (pin "2") (pinfunction "2_2") (pintype "passive"))
      (node (ref "C141") (pin "2") (pinfunction "2_2") (pintype "passive"))
      (node (ref "C142") (pin "2") (pinfunction "2_2") (pintype "passive"))
      (node (ref "C143") (pin "2") (pinfunction "2_2") (pintype "passive"))
      (node (ref "C16") (pin "2") (pinfunction "2_2") (pintype "passive"))
      (node (ref "C17") (pin "2") (pinfunction "2_2") (pintype "passive"))
      (node (ref "C18") (pin "1") (pinfunction "1_1") (pintype "passive"))
      (node (ref "C19") (pin "1") (pinfunction "1_1") (pintype "passive"))
      (node (ref "C2") (pin "-") (pinfunction "-_-") (pintype "passive"))
      (node (ref "C20") (pin "1") (pinfunction "1_1") (pintype "passive"))
      (node (ref "C21") (pin "1") (pinfunction "1_1") (pintype "passive"))
      (node (ref "C24") (pin "1") (pinfunction "1_1") (pintype "passive"))
      (node (ref "C25") (pin "1") (pinfunction "1_1") (pintype "passive"))
      (node (ref "C26") (pin "1") (pinfunction "1_1") (pintype "passive"))
      (node (ref "C27") (pin "1") (pinfunction "1_1") (pintype "passive"))
      (node (ref "C28") (pin "-") (pinfunction "-_-") (pintype "passive"))
      (node (ref "C29") (pin "2") (pinfunction "2_2") (pintype "passive"))
      (node (ref "C30") (pin "2") (pinfunction "2_2") (pintype "passive"))
      (node (ref "C31") (pin "2") (pinfunction "2_2") (pintype "passive"))
      (node (ref "C32") (pin "2") (pinfunction "2_2") (pintype "passive"))
      (node (ref "C33") (pin "-") (pinfunction "-_-") (pintype "passive"))
      (node (ref "C34") (pin "2") (pinfunction "2_2") (pintype "passive"))
      (node (ref "C35") (pin "-") (pinfunction "-_-") (pintype "passive"))
      (node (ref "C36") (pin "-") (pinfunction "-_-") (pintype "passive"))
      (node (ref "C37") (pin "2") (pinfunction "2_2") (pintype "passive"))
      (node (ref "C39") (pin "2") (pinfunction "2_2") (pintype "passive"))
      (node (ref "C4") (pin "2") (pinfunction "2_2") (pintype "passive"))
      (node (ref "C40") (pin "2") (pinfunction "2_2") (pintype "passive"))
      (node (ref "C41") (pin "2") (pinfunction "2_2") (pintype "passive"))
      (node (ref "C42") (pin "1") (pinfunction "1_1") (pintype "passive"))
      (node (ref "C45") (pin "-") (pinfunction "-_-") (pintype "passive"))
      (node (ref "C46") (pin "+") (pinfunction "+_+") (pintype "passive"))
      (node (ref "C47") (pin "2") (pinfunction "2_2") (pintype "passive"))
      (node (ref "C48") (pin "2") (pinfunction "2_2") (pintype "passive"))
      (node (ref "C49") (pin "2") (pinfunction "2_2") (pintype "passive"))
      (node (ref "C5") (pin "2") (pinfunction "2_2") (pintype "passive"))
      (node (ref "C50") (pin "1") (pinfunction "1_1") (pintype "passive"))
      (node (ref "C51") (pin "2") (pinfunction "2_2") (pintype "passive"))
      (node (ref "C52") (pin "-") (pinfunction "-_-") (pintype "passive"))
      (node (ref "C53") (pin "+") (pinfunction "+_+") (pintype "passive"))
      (node (ref "C55") (pin "2") (pinfunction "2_2") (pintype "passive"))
      (node (ref "C56") (pin "1") (pinfunction "1_1") (pintype "passive"))
      (node (ref "C57") (pin "2") (pinfunction "2_2") (pintype "passive"))
      (node (ref "C58") (pin "-") (pinfunction "-_-") (pintype "passive"))
      (node (ref "C59") (pin "+") (pinfunction "+_+") (pintype "passive"))
      (node (ref "C6") (pin "2") (pinfunction "2_2") (pintype "passive"))
      (node (ref "C60") (pin "-") (pinfunction "-_-") (pintype "passive"))
      (node (ref "C61") (pin "2") (pinfunction "2_2") (pintype "passive"))
      (node (ref "C63") (pin "2") (pinfunction "2_2") (pintype "passive"))
      (node (ref "C64") (pin "2") (pinfunction "2_2") (pintype "passive"))
      (node (ref "C65") (pin "2") (pinfunction "2_2") (pintype "passive"))
      (node (ref "C66") (pin "1") (pinfunction "1_1") (pintype "passive"))
      (node (ref "C69") (pin "-") (pinfunction "-_-") (pintype "passive"))
      (node (ref "C7") (pin "2") (pinfunction "2_2") (pintype "passive"))
      (node (ref "C70") (pin "+") (pinfunction "+_+") (pintype "passive"))
      (node (ref "C71") (pin "2") (pinfunction "2_2") (pintype "passive"))
      (node (ref "C72") (pin "2") (pinfunction "2_2") (pintype "passive"))
      (node (ref "C73") (pin "2") (pinfunction "2_2") (pintype "passive"))
      (node (ref "C74") (pin "1") (pinfunction "1_1") (pintype "passive"))
      (node (ref "C75") (pin "2") (pinfunction "2_2") (pintype "passive"))
      (node (ref "C76") (pin "-") (pinfunction "-_-") (pintype "passive"))
      (node (ref "C77") (pin "+") (pinfunction "+_+") (pintype "passive"))
      (node (ref "C79") (pin "2") (pinfunction "2_2") (pintype "passive"))
      (node (ref "C8") (pin "2") (pinfunction "2_2") (pintype "passive"))
      (node (ref "C80") (pin "1") (pinfunction "1_1") (pintype "passive"))
      (node (ref "C81") (pin "2") (pinfunction "2_2") (pintype "passive"))
      (node (ref "C82") (pin "-") (pinfunction "-_-") (pintype "passive"))
      (node (ref "C83") (pin "+") (pinfunction "+_+") (pintype "passive"))
      (node (ref "C84") (pin "2") (pinfunction "2_2") (pintype "passive"))
      (node (ref "C85") (pin "2") (pinfunction "2_2") (pintype "passive"))
      (node (ref "C86") (pin "2") (pinfunction "2_2") (pintype "passive"))
      (node (ref "C87") (pin "2") (pinfunction "2_2") (pintype "passive"))
      (node (ref "C88") (pin "2") (pinfunction "2_2") (pintype "passive"))
      (node (ref "C89") (pin "2") (pinfunction "2_2") (pintype "passive"))
      (node (ref "C9") (pin "2") (pinfunction "2_2") (pintype "passive"))
      (node (ref "C90") (pin "1") (pinfunction "1_1") (pintype "passive"))
      (node (ref "C91") (pin "1") (pinfunction "1_1") (pintype "passive"))
      (node (ref "C92") (pin "2") (pinfunction "2_2") (pintype "passive"))
      (node (ref "C93") (pin "2") (pinfunction "2_2") (pintype "passive"))
      (node (ref "C94") (pin "2") (pinfunction "2_2") (pintype "passive"))
      (node (ref "C95") (pin "2") (pinfunction "2_2") (pintype "passive"))
      (node (ref "C96") (pin "2") (pinfunction "2_2") (pintype "passive"))
      (node (ref "C97") (pin "2") (pinfunction "2_2") (pintype "passive"))
      (node (ref "C98") (pin "2") (pinfunction "2_2") (pintype "passive"))
      (node (ref "C99") (pin "2") (pinfunction "2_2") (pintype "passive"))
      (node (ref "CLKIN") (pin "5") (pinfunction "5_5") (pintype "passive"))
      (node (ref "CUSB1") (pin "2") (pinfunction "2_2") (pintype "passive"))
      (node (ref "EMI") (pin "P$1") (pinfunction "O_P$1") (pintype "power_in"))
      (node (ref "EMI") (pin "P$10") (pinfunction "O_P$10") (pintype "power_in"))
      (node (ref "EMI") (pin "P$11") (pinfunction "O_P$11") (pintype "power_in"))
      (node (ref "EMI") (pin "P$12") (pinfunction "O_P$12") (pintype "power_in"))
      (node (ref "EMI") (pin "P$2") (pinfunction "O_P$2") (pintype "power_in"))
      (node (ref "EMI") (pin "P$3") (pinfunction "O_P$3") (pintype "power_in"))
      (node (ref "EMI") (pin "P$4") (pinfunction "O_P$4") (pintype "power_in"))
      (node (ref "EMI") (pin "P$5") (pinfunction "O_P$5") (pintype "power_in"))
      (node (ref "EMI") (pin "P$6") (pinfunction "O_P$6") (pintype "power_in"))
      (node (ref "EMI") (pin "P$7") (pinfunction "O_P$7") (pintype "power_in"))
      (node (ref "EMI") (pin "P$8") (pinfunction "O_P$8") (pintype "power_in"))
      (node (ref "EMI") (pin "P$9") (pinfunction "O_P$9") (pintype "power_in"))
      (node (ref "GND") (pin "TP") (pinfunction "TP_TP") (pintype "input"))
      (node (ref "GND174") (pin "TP") (pinfunction "TP_TP") (pintype "input"))
      (node (ref "GND176") (pin "TP") (pinfunction "TP_TP") (pintype "input"))
      (node (ref "IC1") (pin "2") (pinfunction "GND_2") (pintype "bidirectional"))
      (node (ref "IC13") (pin "P13") (pinfunction "VSS_P13") (pintype "bidirectional"))
      (node (ref "IC13") (pin "P25") (pinfunction "VSS_P25") (pintype "bidirectional"))
      (node (ref "IC13") (pin "P36") (pinfunction "VSS_P36") (pintype "bidirectional"))
      (node (ref "IC13") (pin "P48") (pinfunction "VSS_P48") (pintype "bidirectional"))
      (node (ref "IC14") (pin "P$3") (pinfunction "GND_P$3") (pintype "bidirectional"))
      (node (ref "IC14") (pin "P$6") (pinfunction "GND_T_P$6") (pintype "bidirectional"))
      (node (ref "IC15") (pin "P$2") (pinfunction "GND_P$2") (pintype "bidirectional"))
      (node (ref "IC16") (pin "13") (pinfunction "VSS_13") (pintype "input"))
      (node (ref "IC16") (pin "31") (pinfunction "AVSS_31") (pintype "bidirectional"))
      (node (ref "IC16") (pin "36") (pinfunction "VSS_36") (pintype "bidirectional"))
      (node (ref "IC16") (pin "45") (pinfunction "VSS_45") (pintype "bidirectional"))
      (node (ref "IC16") (pin "53") (pinfunction "VSS_53") (pintype "bidirectional"))
      (node (ref "IC16") (pin "63") (pinfunction "VSS_63") (pintype "bidirectional"))
      (node (ref "IC16") (pin "75") (pinfunction "VSS_75") (pintype "bidirectional"))
      (node (ref "IC16") (pin "84") (pinfunction "VSS_84") (pintype "bidirectional"))
      (node (ref "IC16") (pin "92") (pinfunction "VSS_92") (pintype "input"))
      (node (ref "IC18") (pin "2") (pinfunction "GND_2") (pintype "bidirectional"))
      (node (ref "IC2") (pin "1") (pinfunction "PGND_1") (pintype "bidirectional"))
      (node (ref "IC2") (pin "15") (pinfunction "AGND_15") (pintype "bidirectional"))
      (node (ref "IC2") (pin "4") (pinfunction "SYNC/FREQ_4") (pintype "bidirectional"))
      (node (ref "IC2") (pin "6") (pinfunction "SLEW_6") (pintype "bidirectional"))
      (node (ref "IC2") (pin "EPAD") (pinfunction "PGND_EPAD") (pintype "bidirectional"))
      (node (ref "IC20") (pin "2") (pinfunction "GND_2") (pintype "bidirectional"))
      (node (ref "IC21") (pin "15") (pinfunction "GND2_15") (pintype "bidirectional"))
      (node (ref "IC21") (pin "9") (pinfunction "GND2_9") (pintype "bidirectional"))
      (node (ref "IC22") (pin "1") (pinfunction "P$1_1") (pintype "bidirectional"))
      (node (ref "IC22") (pin "3") (pinfunction "P$3_3") (pintype "bidirectional"))
      (node (ref "IC23") (pin "1") (pinfunction "P$1_1") (pintype "bidirectional"))
      (node (ref "IC23") (pin "3") (pinfunction "P$3_3") (pintype "bidirectional"))
      (node (ref "IC24") (pin "3") (pinfunction "P$3_3") (pintype "bidirectional"))
      (node (ref "IC25") (pin "18") (pinfunction "GND_18") (pintype "power_in"))
      (node (ref "IC25") (pin "30") (pinfunction "GND_30") (pintype "power_in"))
      (node (ref "IC25") (pin "38") (pinfunction "GND_38") (pintype "power_in"))
      (node (ref "IC25") (pin "7") (pinfunction "PB3/ADC11/DAC1_7") (pintype "bidirectional"))
      (node (ref "IC25") (pin "8") (pinfunction "GND_8") (pintype "power_in"))
      (node (ref "IC26") (pin "2") (pinfunction "GND1_2") (pintype "bidirectional"))
      (node (ref "IC26") (pin "3") (pinfunction "A1_3") (pintype "bidirectional"))
      (node (ref "IC26") (pin "8") (pinfunction "GND1_8") (pintype "bidirectional"))
      (node (ref "IC27") (pin "4") (pinfunction "GND_4") (pintype "bidirectional"))
      (node (ref "IC28") (pin "1") (pinfunction "P$1_1") (pintype "bidirectional"))
      (node (ref "IC28") (pin "3") (pinfunction "P$3_3") (pintype "bidirectional"))
      (node (ref "IC29") (pin "1") (pinfunction "P$1_1") (pintype "bidirectional"))
      (node (ref "IC29") (pin "3") (pinfunction "P$3_3") (pintype "bidirectional"))
      (node (ref "IC3") (pin "1") (pinfunction "GND_1") (pintype "bidirectional"))
      (node (ref "IC30") (pin "1") (pinfunction "P$1_1") (pintype "bidirectional"))
      (node (ref "IC30") (pin "3") (pinfunction "P$3_3") (pintype "bidirectional"))
      (node (ref "IC31") (pin "1") (pinfunction "P$1_1") (pintype "bidirectional"))
      (node (ref "IC31") (pin "3") (pinfunction "P$3_3") (pintype "bidirectional"))
      (node (ref "IC32") (pin "P$3") (pinfunction "GND_P$3") (pintype "bidirectional"))
      (node (ref "IC32") (pin "P$6") (pinfunction "GND_T_P$6") (pintype "bidirectional"))
      (node (ref "IC33") (pin "3") (pinfunction "GND_3") (pintype "bidirectional"))
      (node (ref "IC34") (pin "3") (pinfunction "GND_3") (pintype "bidirectional"))
      (node (ref "IC35") (pin "3") (pinfunction "GND_3") (pintype "bidirectional"))
      (node (ref "IC4") (pin "4") (pinfunction "GND_4") (pintype "bidirectional"))
      (node (ref "IC5") (pin "4") (pinfunction "GND_4") (pintype "bidirectional"))
      (node (ref "IC6") (pin "P10") (pinfunction "AGND_P10") (pintype "bidirectional"))
      (node (ref "IC6") (pin "P19") (pinfunction "AGND_P19") (pintype "bidirectional"))
      (node (ref "IC6") (pin "P28") (pinfunction "DGND_P28") (pintype "bidirectional"))
      (node (ref "IC6") (pin "P9") (pinfunction "DSD_PHASE_P9") (pintype "bidirectional"))
      (node (ref "IN") (pin "2") (pinfunction "2_2") (pintype "passive"))
      (node (ref "IN1") (pin "2") (pinfunction "S_2") (pintype "passive"))
      (node (ref "J3") (pin "P1") (pinfunction "1_P1") (pintype "passive"))
      (node (ref "J4") (pin "P1") (pinfunction "1_P1") (pintype "passive"))
      (node (ref "JACK") (pin "P2") (pinfunction "2_P2") (pintype "passive"))
      (node (ref "JACK") (pin "P3") (pinfunction "3_P3") (pintype "passive"))
      (node (ref "JP1") (pin "3") (pinfunction "3_3") (pintype "passive"))
      (node (ref "L3") (pin "2") (pinfunction "2_2") (pintype "passive"))
      (node (ref "OSC1") (pin "P$2") (pinfunction "GND_P$2") (pintype "passive"))
      (node (ref "OSC2") (pin "P$2") (pinfunction "GND_P$2") (pintype "passive"))
      (node (ref "OSC3") (pin "P$2") (pinfunction "GND_P$2") (pintype "bidirectional"))
      (node (ref "OUT") (pin "2") (pinfunction "2_2") (pintype "passive"))
      (node (ref "OUT1") (pin "2") (pinfunction "S_2") (pintype "passive"))
      (node (ref "PDI") (pin "6") (pinfunction "6_6") (pintype "passive"))
      (node (ref "R15") (pin "2") (pinfunction "2_2") (pintype "passive"))
      (node (ref "R18") (pin "1") (pinfunction "1_1") (pintype "passive"))
      (node (ref "R20") (pin "2") (pinfunction "2_2") (pintype "passive"))
      (node (ref "R22") (pin "1") (pinfunction "1_1") (pintype "passive"))
      (node (ref "R3") (pin "2") (pinfunction "2_2") (pintype "passive"))
      (node (ref "R34") (pin "1") (pinfunction "1_1") (pintype "passive"))
      (node (ref "R50") (pin "1") (pinfunction "1_1") (pintype "passive"))
      (node (ref "R55") (pin "1") (pinfunction "1_1") (pintype "passive"))
      (node (ref "R61") (pin "2") (pinfunction "2_2") (pintype "passive"))
      (node (ref "R67") (pin "2") (pinfunction "2_2") (pintype "passive"))
      (node (ref "R68") (pin "2") (pinfunction "2_2") (pintype "passive"))
      (node (ref "R7") (pin "2") (pinfunction "2_2") (pintype "passive"))
      (node (ref "R72") (pin "1") (pinfunction "1_1") (pintype "passive"))
      (node (ref "R78") (pin "2") (pinfunction "2_2") (pintype "passive"))
      (node (ref "R79") (pin "2") (pinfunction "2_2") (pintype "passive"))
      (node (ref "RUSB1") (pin "2") (pinfunction "2_2") (pintype "passive"))
      (node (ref "STATE") (pin "K") (pinfunction "K_K") (pintype "bidirectional"))
      (node (ref "SW1") (pin "P") (pinfunction "P_P") (pintype "passive"))
      (node (ref "TX1") (pin "K") (pinfunction "K_K") (pintype "bidirectional"))
      (node (ref "TX2") (pin "K") (pinfunction "K_K") (pintype "bidirectional"))
      (node (ref "TX3") (pin "K") (pinfunction "K_K") (pintype "bidirectional"))
      (node (ref "USB1") (pin "P$5") (pinfunction "5_P$5") (pintype "bidirectional"))
      (node (ref "X1") (pin "P1") (pinfunction "1_P1") (pintype "passive"))
      (node (ref "X1") (pin "P5") (pinfunction "5_P5") (pintype "passive"))
      (node (ref "X1") (pin "P8") (pinfunction "8_P8") (pintype "passive"))
    )
    (net (code "34") (name "GND2") (class "Default")
      (node (ref "C106") (pin "2") (pinfunction "2_2") (pintype "passive"))
      (node (ref "C107") (pin "2") (pinfunction "2_2") (pintype "passive"))
      (node (ref "C108") (pin "2") (pinfunction "2_2") (pintype "passive"))
      (node (ref "C111") (pin "2") (pinfunction "2_2") (pintype "passive"))
      (node (ref "C112") (pin "-") (pinfunction "-_-") (pintype "passive"))
      (node (ref "C113") (pin "2") (pinfunction "2_2") (pintype "passive"))
      (node (ref "C114") (pin "2") (pinfunction "2_2") (pintype "passive"))
      (node (ref "C117") (pin "2") (pinfunction "2_2") (pintype "passive"))
      (node (ref "CUSB2") (pin "2") (pinfunction "2_2") (pintype "passive"))
      (node (ref "IC17") (pin "P$2") (pinfunction "GND_P$2") (pintype "bidirectional"))
      (node (ref "IC19") (pin "18") (pinfunction "GND_18") (pintype "power_in"))
      (node (ref "IC19") (pin "21") (pinfunction "GND_21") (pintype "power_in"))
      (node (ref "IC19") (pin "25") (pinfunction "GND_25") (pintype "power_in"))
      (node (ref "IC19") (pin "26") (pinfunction "TEST_26") (pintype "input"))
      (node (ref "IC19") (pin "7") (pinfunction "GND_7") (pintype "power_in"))
      (node (ref "IC21") (pin "2") (pinfunction "GND1_2") (pintype "bidirectional"))
      (node (ref "IC21") (pin "8") (pinfunction "GND1_8") (pintype "bidirectional"))
      (node (ref "RUSB2") (pin "2") (pinfunction "2_2") (pintype "passive"))
      (node (ref "USB2") (pin "P$5") (pinfunction "5_P$5") (pintype "bidirectional"))
    )
    (net (code "35") (name "GNDIO") (class "Default")
      (node (ref "IC26") (pin "15") (pinfunction "GND2_15") (pintype "bidirectional"))
      (node (ref "IC26") (pin "9") (pinfunction "GND2_9") (pintype "bidirectional"))
      (node (ref "J1") (pin "5") (pinfunction "5_5") (pintype "passive"))
    )
    (net (code "36") (name "IN00{slash}TRIG") (class "Default")
      (node (ref "IC16") (pin "71") (pinfunction "EMDIO/AEMDIO/RPD0/RTCC/INT0/RD0_71") (pintype "bidirectional"))
      (node (ref "IC24") (pin "4") (pinfunction "P$4_4") (pintype "bidirectional"))
      (node (ref "IC25") (pin "4") (pinfunction "PB0/ADC8/AREF_4") (pintype "bidirectional"))
      (node (ref "R63") (pin "1") (pinfunction "1_1") (pintype "passive"))
    )
    (net (code "37") (name "IN1") (class "Default")
      (node (ref "IC30") (pin "2") (pinfunction "P$2_2") (pintype "bidirectional"))
      (node (ref "R67") (pin "1") (pinfunction "1_1") (pintype "passive"))
      (node (ref "X1") (pin "P10") (pinfunction "10_P10") (pintype "passive"))
    )
    (net (code "38") (name "IN01") (class "Default")
      (node (ref "IC25") (pin "20") (pinfunction "~{OC0APD0}_20") (pintype "bidirectional"))
      (node (ref "R69") (pin "2") (pinfunction "2_2") (pintype "passive"))
    )
    (net (code "39") (name "IN2") (class "Default")
      (node (ref "IC31") (pin "2") (pinfunction "P$2_2") (pintype "bidirectional"))
      (node (ref "R68") (pin "1") (pinfunction "1_1") (pintype "passive"))
      (node (ref "X1") (pin "P9") (pinfunction "9_P9") (pintype "passive"))
    )
    (net (code "40") (name "IN02") (class "Default")
      (node (ref "IC25") (pin "10") (pinfunction "PC0/OC0A/SDA_10") (pintype "bidirectional"))
      (node (ref "R70") (pin "2") (pinfunction "2_2") (pintype "passive"))
    )
    (net (code "41") (name "IN_RJ") (class "Default")
      (node (ref "IC26") (pin "13") (pinfunction "B2_13") (pintype "bidirectional"))
      (node (ref "J1") (pin "1") (pinfunction "1_1") (pintype "passive"))
    )
    (net (code "42") (name "IOUTL+") (class "Default")
      (node (ref "C62") (pin "1") (pinfunction "1_1") (pintype "passive"))
      (node (ref "IC10") (pin "2") (pinfunction "-IN_2") (pintype "input"))
      (node (ref "IC6") (pin "P18") (pinfunction "IOUTL+_P18") (pintype "bidirectional"))
      (node (ref "R39") (pin "1") (pinfunction "1_1") (pintype "passive"))
      (node (ref "R43") (pin "1") (pinfunction "1_1") (pintype "passive"))
      (node (ref "R45") (pin "1") (pinfunction "1_1") (pintype "passive"))
    )
    (net (code "43") (name "IOUTL-") (class "Default")
      (node (ref "C62") (pin "2") (pinfunction "2_2") (pintype "passive"))
      (node (ref "IC11") (pin "2") (pinfunction "-IN_2") (pintype "input"))
      (node (ref "IC6") (pin "P17") (pinfunction "IOUTL-_P17") (pintype "bidirectional"))
      (node (ref "R42") (pin "1") (pinfunction "1_1") (pintype "passive"))
      (node (ref "R44") (pin "1") (pinfunction "1_1") (pintype "passive"))
      (node (ref "R46") (pin "1") (pinfunction "1_1") (pintype "passive"))
    )
    (net (code "44") (name "IOUTR+") (class "Default")
      (node (ref "C38") (pin "1") (pinfunction "1_1") (pintype "passive"))
      (node (ref "IC6") (pin "P11") (pinfunction "IOUTR+_P11") (pintype "bidirectional"))
      (node (ref "IC7") (pin "2") (pinfunction "-IN_2") (pintype "input"))
      (node (ref "R23") (pin "1") (pinfunction "1_1") (pintype "passive"))
      (node (ref "R27") (pin "1") (pinfunction "1_1") (pintype "passive"))
      (node (ref "R29") (pin "1") (pinfunction "1_1") (pintype "passive"))
    )
    (net (code "45") (name "IOUTR-") (class "Default")
      (node (ref "C38") (pin "2") (pinfunction "2_2") (pintype "passive"))
      (node (ref "IC6") (pin "P12") (pinfunction "IOUTR-_P12") (pintype "bidirectional"))
      (node (ref "IC8") (pin "2") (pinfunction "-IN_2") (pintype "input"))
      (node (ref "R26") (pin "1") (pinfunction "1_1") (pintype "passive"))
      (node (ref "R28") (pin "1") (pinfunction "1_1") (pintype "passive"))
      (node (ref "R30") (pin "1") (pinfunction "1_1") (pintype "passive"))
    )
    (net (code "46") (name "MEMORY") (class "Default")
      (node (ref "IC16") (pin "95") (pinfunction "TRD2/SQID2/RG14_95") (pintype "bidirectional"))
      (node (ref "R75") (pin "2") (pinfunction "2_2") (pintype "passive"))
    )
    (net (code "47") (name "MUTE") (class "Default")
      (node (ref "IC16") (pin "57") (pinfunction "EBIRDY3/RPF2/SDA3/RF2_57") (pintype "bidirectional"))
      (node (ref "IC6") (pin "P22") (pinfunction "MUTE_P22") (pintype "bidirectional"))
    )
    (net (code "48") (name "Net-(C3-Pad1)") (class "Default")
      (node (ref "C3") (pin "1") (pinfunction "1_1") (pintype "passive"))
      (node (ref "R4") (pin "2") (pinfunction "2_2") (pintype "passive"))
    )
    (net (code "49") (name "Net-(C6-Pad1)") (class "Default")
      (node (ref "C6") (pin "1") (pinfunction "1_1") (pintype "passive"))
      (node (ref "D1") (pin "C") (pinfunction "C_C") (pintype "passive"))
      (node (ref "L1") (pin "2") (pinfunction "2_2") (pintype "passive"))
      (node (ref "R5") (pin "1") (pinfunction "1_1") (pintype "passive"))
    )
    (net (code "50") (name "Net-(C7-Pad1)") (class "Default")
      (node (ref "C7") (pin "1") (pinfunction "1_1") (pintype "passive"))
      (node (ref "R8") (pin "2") (pinfunction "2_2") (pintype "passive"))
    )
    (net (code "51") (name "Net-(C12-Pad1)") (class "Default")
      (node (ref "C12") (pin "1") (pinfunction "1_1") (pintype "passive"))
      (node (ref "R13") (pin "1") (pinfunction "1_1") (pintype "passive"))
    )
    (net (code "52") (name "Net-(C13-Pad1)") (class "Default")
      (node (ref "C13") (pin "1") (pinfunction "1_1") (pintype "passive"))
      (node (ref "D2") (pin "A") (pinfunction "A_A") (pintype "passive"))
      (node (ref "L4") (pin "1") (pinfunction "1_1") (pintype "passive"))
      (node (ref "R17") (pin "2") (pinfunction "2_2") (pintype "passive"))
    )
    (net (code "53") (name "Net-(C15-Pad1)") (class "Default")
      (node (ref "C15") (pin "1") (pinfunction "1_1") (pintype "passive"))
      (node (ref "R16") (pin "2") (pinfunction "2_2") (pintype "passive"))
    )
    (net (code "54") (name "Net-(C43-Pad1)") (class "Default")
      (node (ref "C43") (pin "1") (pinfunction "1_1") (pintype "passive"))
      (node (ref "R27") (pin "2") (pinfunction "2_2") (pintype "passive"))
    )
    (net (code "55") (name "Net-(C44-Pad1)") (class "Default")
      (node (ref "C44") (pin "1") (pinfunction "1_1") (pintype "passive"))
      (node (ref "R28") (pin "2") (pinfunction "2_2") (pintype "passive"))
    )
    (net (code "56") (name "Net-(C47-Pad1)") (class "Default")
      (node (ref "C47") (pin "1") (pinfunction "1_1") (pintype "passive"))
      (node (ref "R31") (pin "2") (pinfunction "2_2") (pintype "passive"))
      (node (ref "R33") (pin "1") (pinfunction "1_1") (pintype "passive"))
      (node (ref "R35") (pin "1") (pinfunction "1_1") (pintype "passive"))
    )
    (net (code "57") (name "Net-(C48-Pad1)") (class "Default")
      (node (ref "C48") (pin "1") (pinfunction "1_1") (pintype "passive"))
      (node (ref "R32") (pin "2") (pinfunction "2_2") (pintype "passive"))
      (node (ref "R34") (pin "2") (pinfunction "2_2") (pintype "passive"))
      (node (ref "R36") (pin "1") (pinfunction "1_1") (pintype "passive"))
    )
    (net (code "58") (name "Net-(C54-Pad1)") (class "Default")
      (node (ref "C54") (pin "1") (pinfunction "1_1") (pintype "passive"))
      (node (ref "R37") (pin "2") (pinfunction "2_2") (pintype "passive"))
    )
    (net (code "59") (name "Net-(C67-Pad1)") (class "Default")
      (node (ref "C67") (pin "1") (pinfunction "1_1") (pintype "passive"))
      (node (ref "R43") (pin "2") (pinfunction "2_2") (pintype "passive"))
    )
    (net (code "60") (name "Net-(C68-Pad1)") (class "Default")
      (node (ref "C68") (pin "1") (pinfunction "1_1") (pintype "passive"))
      (node (ref "R44") (pin "2") (pinfunction "2_2") (pintype "passive"))
    )
    (net (code "61") (name "Net-(C71-Pad1)") (class "Default")
      (node (ref "C71") (pin "1") (pinfunction "1_1") (pintype "passive"))
      (node (ref "R47") (pin "2") (pinfunction "2_2") (pintype "passive"))
      (node (ref "R49") (pin "1") (pinfunction "1_1") (pintype "passive"))
      (node (ref "R51") (pin "1") (pinfunction "1_1") (pintype "passive"))
    )
    (net (code "62") (name "Net-(C72-Pad1)") (class "Default")
      (node (ref "C72") (pin "1") (pinfunction "1_1") (pintype "passive"))
      (node (ref "R48") (pin "2") (pinfunction "2_2") (pintype "passive"))
      (node (ref "R50") (pin "2") (pinfunction "2_2") (pintype "passive"))
      (node (ref "R52") (pin "1") (pinfunction "1_1") (pintype "passive"))
    )
    (net (code "63") (name "Net-(C78-Pad1)") (class "Default")
      (node (ref "C78") (pin "1") (pinfunction "1_1") (pintype "passive"))
      (node (ref "R53") (pin "2") (pinfunction "2_2") (pintype "passive"))
    )
    (net (code "64") (name "Net-(C101-Pad1)") (class "Default")
      (node (ref "C101") (pin "1") (pinfunction "1_1") (pintype "passive"))
      (node (ref "R56") (pin "1") (pinfunction "1_1") (pintype "passive"))
      (node (ref "R57") (pin "2") (pinfunction "2_2") (pintype "passive"))
    )
    (net (code "65") (name "Net-(IC1-ADJ)") (class "Default")
      (node (ref "IC1") (pin "4") (pinfunction "ADJ_4") (pintype "bidirectional"))
      (node (ref "R1") (pin "2") (pinfunction "2_2") (pintype "passive"))
      (node (ref "R2") (pin "2") (pinfunction "2_2") (pintype "passive"))
      (node (ref "R3") (pin "1") (pinfunction "1_1") (pintype "passive"))
      (node (ref "R4") (pin "1") (pinfunction "1_1") (pintype "passive"))
    )
    (net (code "66") (name "Net-(IC2-COMP1)") (class "Default")
      (node (ref "C8") (pin "1") (pinfunction "1_1") (pintype "passive"))
      (node (ref "IC2") (pin "8") (pinfunction "COMP1_8") (pintype "bidirectional"))
      (node (ref "R8") (pin "1") (pinfunction "1_1") (pintype "passive"))
    )
    (net (code "67") (name "Net-(IC2-COMP2)") (class "Default")
      (node (ref "C10") (pin "1") (pinfunction "1_1") (pintype "passive"))
      (node (ref "IC2") (pin "12") (pinfunction "COMP2_12") (pintype "bidirectional"))
      (node (ref "R13") (pin "2") (pinfunction "2_2") (pintype "passive"))
    )
    (net (code "68") (name "Net-(IC2-FB1)") (class "Default")
      (node (ref "IC2") (pin "7") (pinfunction "FB1_7") (pintype "bidirectional"))
      (node (ref "R6") (pin "1") (pinfunction "1_1") (pintype "passive"))
      (node (ref "R7") (pin "1") (pinfunction "1_1") (pintype "passive"))
    )
    (net (code "69") (name "Net-(IC2-FB2)") (class "Default")
      (node (ref "IC2") (pin "13") (pinfunction "FB2_13") (pintype "bidirectional"))
      (node (ref "R10") (pin "2") (pinfunction "2_2") (pintype "passive"))
      (node (ref "R12") (pin "2") (pinfunction "2_2") (pintype "passive"))
    )
    (net (code "70") (name "Net-(IC2-INBK)") (class "Default")
      (node (ref "IC2") (pin "3") (pinfunction "INBK_3") (pintype "bidirectional"))
      (node (ref "L2") (pin "2") (pinfunction "2_2") (pintype "passive"))
    )
    (net (code "71") (name "Net-(IC2-SW1)") (class "Default")
      (node (ref "D1") (pin "A") (pinfunction "A_A") (pintype "passive"))
      (node (ref "IC2") (pin "2") (pinfunction "SW1_2") (pintype "bidirectional"))
      (node (ref "L2") (pin "1") (pinfunction "1_1") (pintype "passive"))
    )
    (net (code "72") (name "Net-(IC2-SW2)") (class "Default")
      (node (ref "D2") (pin "C") (pinfunction "C_C") (pintype "passive"))
      (node (ref "IC2") (pin "20") (pinfunction "SW2_20") (pintype "bidirectional"))
      (node (ref "L3") (pin "1") (pinfunction "1_1") (pintype "passive"))
    )
    (net (code "73") (name "Net-(IC2-VREF)") (class "Default")
      (node (ref "C137") (pin "1") (pinfunction "1_1") (pintype "passive"))
      (node (ref "IC2") (pin "14") (pinfunction "VREF_14") (pintype "bidirectional"))
      (node (ref "R10") (pin "1") (pinfunction "1_1") (pintype "passive"))
    )
    (net (code "74") (name "Net-(IC2-VREG)") (class "Default")
      (node (ref "C14") (pin "1") (pinfunction "1_1") (pintype "passive"))
      (node (ref "IC2") (pin "16") (pinfunction "VREG_16") (pintype "bidirectional"))
    )
    (net (code "75") (name "Net-(IC3-ADJ)") (class "Default")
      (node (ref "IC3") (pin "4") (pinfunction "ADJ_4") (pintype "bidirectional"))
      (node (ref "R11") (pin "2") (pinfunction "2_2") (pintype "passive"))
      (node (ref "R14") (pin "2") (pinfunction "2_2") (pintype "passive"))
      (node (ref "R15") (pin "1") (pinfunction "1_1") (pintype "passive"))
      (node (ref "R16") (pin "1") (pinfunction "1_1") (pintype "passive"))
    )
    (net (code "76") (name "Net-(IC4-NR)") (class "Default")
      (node (ref "C22") (pin "1") (pinfunction "1_1") (pintype "passive"))
      (node (ref "IC4") (pin "3") (pinfunction "NR_3") (pintype "bidirectional"))
    )
    (net (code "77") (name "Net-(IC4-~{SD})") (class "Default")
      (node (ref "C24") (pin "2") (pinfunction "2_2") (pintype "passive"))
      (node (ref "C26") (pin "2") (pinfunction "2_2") (pintype "passive"))
      (node (ref "IC4") (pin "5") (pinfunction "~{SD}_5") (pintype "bidirectional"))
      (node (ref "IC4") (pin "7") (pinfunction "IN_7") (pintype "bidirectional"))
      (node (ref "IC4") (pin "8") (pinfunction "IN_8") (pintype "bidirectional"))
      (node (ref "L5") (pin "2") (pinfunction "2_2") (pintype "passive"))
    )
    (net (code "78") (name "Net-(IC5-NR)") (class "Default")
      (node (ref "C23") (pin "1") (pinfunction "1_1") (pintype "passive"))
      (node (ref "IC5") (pin "3") (pinfunction "NR_3") (pintype "bidirectional"))
    )
    (net (code "79") (name "Net-(IC5-~{SD})") (class "Default")
      (node (ref "C25") (pin "2") (pinfunction "2_2") (pintype "passive"))
      (node (ref "C27") (pin "2") (pinfunction "2_2") (pintype "passive"))
      (node (ref "IC5") (pin "5") (pinfunction "~{SD}_5") (pintype "bidirectional"))
      (node (ref "IC5") (pin "7") (pinfunction "IN_7") (pintype "bidirectional"))
      (node (ref "IC5") (pin "8") (pinfunction "IN_8") (pintype "bidirectional"))
      (node (ref "L6") (pin "2") (pinfunction "2_2") (pintype "passive"))
    )
    (net (code "80") (name "Net-(IC6-AVDD)") (class "Default")
      (node (ref "C31") (pin "1") (pinfunction "1_1") (pintype "passive"))
      (node (ref "IC6") (pin "P15") (pinfunction "AVDD_P15") (pintype "bidirectional"))
      (node (ref "L8") (pin "2") (pinfunction "2_2") (pintype "passive"))
    )
    (net (code "81") (name "Net-(IC6-DVDD)") (class "Default")
      (node (ref "C30") (pin "1") (pinfunction "1_1") (pintype "passive"))
      (node (ref "IC6") (pin "P1") (pinfunction "DVDD_P1") (pintype "bidirectional"))
      (node (ref "L7") (pin "2") (pinfunction "2_2") (pintype "passive"))
    )
    (net (code "82") (name "Net-(IC6-FILTR)") (class "Default")
      (node (ref "C29") (pin "1") (pinfunction "1_1") (pintype "passive"))
      (node (ref "C33") (pin "+") (pinfunction "+_+") (pintype "passive"))
      (node (ref "IC6") (pin "P13") (pinfunction "FILTR_P13") (pintype "bidirectional"))
    )
    (net (code "83") (name "Net-(IC6-IREF)") (class "Default")
      (node (ref "IC6") (pin "P14") (pinfunction "IREF_P14") (pintype "bidirectional"))
      (node (ref "R18") (pin "2") (pinfunction "2_2") (pintype "passive"))
    )
    (net (code "84") (name "Net-(IC7-+IN)") (class "Default")
      (node (ref "C39") (pin "1") (pinfunction "1_1") (pintype "passive"))
      (node (ref "IC7") (pin "3") (pinfunction "+IN_3") (pintype "input"))
      (node (ref "R24") (pin "1") (pinfunction "1_1") (pintype "passive"))
    )
    (net (code "85") (name "Net-(IC7-OUT)") (class "Default")
      (node (ref "C43") (pin "2") (pinfunction "2_2") (pintype "passive"))
      (node (ref "IC7") (pin "6") (pinfunction "OUT_6") (pintype "output"))
      (node (ref "R29") (pin "2") (pinfunction "2_2") (pintype "passive"))
      (node (ref "R31") (pin "1") (pinfunction "1_1") (pintype "passive"))
    )
    (net (code "86") (name "Net-(IC8-+IN)") (class "Default")
      (node (ref "C40") (pin "1") (pinfunction "1_1") (pintype "passive"))
      (node (ref "IC8") (pin "3") (pinfunction "+IN_3") (pintype "input"))
      (node (ref "R25") (pin "1") (pinfunction "1_1") (pintype "passive"))
    )
    (net (code "87") (name "Net-(IC8-OUT)") (class "Default")
      (node (ref "C44") (pin "2") (pinfunction "2_2") (pintype "passive"))
      (node (ref "IC8") (pin "6") (pinfunction "OUT_6") (pintype "output"))
      (node (ref "R30") (pin "2") (pinfunction "2_2") (pintype "passive"))
      (node (ref "R32") (pin "1") (pinfunction "1_1") (pintype "passive"))
    )
    (net (code "88") (name "Net-(IC9-+IN)") (class "Default")
      (node (ref "C51") (pin "1") (pinfunction "1_1") (pintype "passive"))
      (node (ref "IC9") (pin "3") (pinfunction "+IN_3") (pintype "input"))
      (node (ref "R36") (pin "2") (pinfunction "2_2") (pintype "passive"))
    )
    (net (code "89") (name "Net-(IC9--IN)") (class "Default")
      (node (ref "IC9") (pin "2") (pinfunction "-IN_2") (pintype "input"))
      (node (ref "R35") (pin "2") (pinfunction "2_2") (pintype "passive"))
      (node (ref "R37") (pin "1") (pinfunction "1_1") (pintype "passive"))
    )
    (net (code "90") (name "Net-(IC9-OUT)") (class "Default")
      (node (ref "C54") (pin "2") (pinfunction "2_2") (pintype "passive"))
      (node (ref "IC9") (pin "6") (pinfunction "OUT_6") (pintype "output"))
      (node (ref "R33") (pin "2") (pinfunction "2_2") (pintype "passive"))
      (node (ref "R38") (pin "1") (pinfunction "1_1") (pintype "passive"))
    )
    (net (code "91") (name "Net-(IC10-+IN)") (class "Default")
      (node (ref "C63") (pin "1") (pinfunction "1_1") (pintype "passive"))
      (node (ref "IC10") (pin "3") (pinfunction "+IN_3") (pintype "input"))
      (node (ref "R40") (pin "1") (pinfunction "1_1") (pintype "passive"))
    )
    (net (code "92") (name "Net-(IC10-OUT)") (class "Default")
      (node (ref "C67") (pin "2") (pinfunction "2_2") (pintype "passive"))
      (node (ref "IC10") (pin "6") (pinfunction "OUT_6") (pintype "output"))
      (node (ref "R45") (pin "2") (pinfunction "2_2") (pintype "passive"))
      (node (ref "R47") (pin "1") (pinfunction "1_1") (pintype "passive"))
    )
    (net (code "93") (name "Net-(IC11-+IN)") (class "Default")
      (node (ref "C64") (pin "1") (pinfunction "1_1") (pintype "passive"))
      (node (ref "IC11") (pin "3") (pinfunction "+IN_3") (pintype "input"))
      (node (ref "R41") (pin "1") (pinfunction "1_1") (pintype "passive"))
    )
    (net (code "94") (name "Net-(IC11-OUT)") (class "Default")
      (node (ref "C68") (pin "2") (pinfunction "2_2") (pintype "passive"))
      (node (ref "IC11") (pin "6") (pinfunction "OUT_6") (pintype "output"))
      (node (ref "R46") (pin "2") (pinfunction "2_2") (pintype "passive"))
      (node (ref "R48") (pin "1") (pinfunction "1_1") (pintype "passive"))
    )
    (net (code "95") (name "Net-(IC12-+IN)") (class "Default")
      (node (ref "C75") (pin "1") (pinfunction "1_1") (pintype "passive"))
      (node (ref "IC12") (pin "3") (pinfunction "+IN_3") (pintype "input"))
      (node (ref "R52") (pin "2") (pinfunction "2_2") (pintype "passive"))
    )
    (net (code "96") (name "Net-(IC12--IN)") (class "Default")
      (node (ref "IC12") (pin "2") (pinfunction "-IN_2") (pintype "input"))
      (node (ref "R51") (pin "2") (pinfunction "2_2") (pintype "passive"))
      (node (ref "R53") (pin "1") (pinfunction "1_1") (pintype "passive"))
    )
    (net (code "97") (name "Net-(IC12-OUT)") (class "Default")
      (node (ref "C78") (pin "2") (pinfunction "2_2") (pintype "passive"))
      (node (ref "IC12") (pin "6") (pinfunction "OUT_6") (pintype "output"))
      (node (ref "R49") (pin "2") (pinfunction "2_2") (pintype "passive"))
      (node (ref "R54") (pin "1") (pinfunction "1_1") (pintype "passive"))
    )
    (net (code "98") (name "Net-(IC14-EN)") (class "Default")
      (node (ref "C90") (pin "2") (pinfunction "2_2") (pintype "passive"))
      (node (ref "C91") (pin "2") (pinfunction "2_2") (pintype "passive"))
      (node (ref "IC14") (pin "P$1") (pinfunction "IN_P$1") (pintype "bidirectional"))
      (node (ref "IC14") (pin "P$5") (pinfunction "EN_P$5") (pintype "bidirectional"))
      (node (ref "L9") (pin "2") (pinfunction "2_2") (pintype "passive"))
    )
    (net (code "99") (name "Net-(IC14-NR{slash}FB)") (class "Default")
      (node (ref "IC14") (pin "P$4") (pinfunction "NR/FB_P$4") (pintype "bidirectional"))
      (node (ref "R55") (pin "2") (pinfunction "2_2") (pintype "passive"))
      (node (ref "R74") (pin "1") (pinfunction "1_1") (pintype "passive"))
    )
    (net (code "100") (name "Net-(IC15-VBUS)") (class "Default")
      (node (ref "C138") (pin "1") (pinfunction "1_1") (pintype "passive"))
      (node (ref "IC15") (pin "P$5") (pinfunction "VBUS_P$5") (pintype "bidirectional"))
      (node (ref "L13") (pin "2") (pinfunction "2_2") (pintype "passive"))
      (node (ref "USB1") (pin "P$1") (pinfunction "1_P$1") (pintype "bidirectional"))
    )
    (net (code "101") (name "Net-(IC16-OSC1{slash}CLKI{slash}RC12)") (class "Default")
      (node (ref "IC16") (pin "49") (pinfunction "OSC1/CLKI/RC12_49") (pintype "bidirectional"))
      (node (ref "OSC1") (pin "P$3") (pinfunction "OUTPUT_P$3") (pintype "passive"))
    )
    (net (code "102") (name "Net-(IC16-SOSCO{slash}RPC14{slash}T1CK{slash}RC14)") (class "Default")
      (node (ref "IC16") (pin "73") (pinfunction "SOSCO/RPC14/T1CK/RC14_73") (pintype "bidirectional"))
      (node (ref "OSC3") (pin "P$3") (pinfunction "OUT_P$3") (pintype "bidirectional"))
    )
    (net (code "103") (name "Net-(IC17-VBUS)") (class "Default")
      (node (ref "C106") (pin "1") (pinfunction "1_1") (pintype "passive"))
      (node (ref "IC17") (pin "P$5") (pinfunction "VBUS_P$5") (pintype "bidirectional"))
      (node (ref "L10") (pin "2") (pinfunction "2_2") (pintype "passive"))
      (node (ref "USB2") (pin "P$1") (pinfunction "1_P$1") (pintype "bidirectional"))
    )
    (net (code "104") (name "Net-(IC19-3V3OUT)") (class "Default")
      (node (ref "C113") (pin "1") (pinfunction "1_1") (pintype "passive"))
      (node (ref "IC19") (pin "17") (pinfunction "3V3OUT_17") (pintype "output"))
    )
    (net (code "105") (name "Net-(IC19-CBUS0)") (class "Default")
      (node (ref "IC19") (pin "23") (pinfunction "CBUS0_23") (pintype "bidirectional"))
      (node (ref "TX") (pin "K") (pinfunction "K_K") (pintype "bidirectional"))
    )
    (net (code "106") (name "Net-(IC19-CBUS1)") (class "Default")
      (node (ref "IC19") (pin "22") (pinfunction "CBUS1_22") (pintype "bidirectional"))
      (node (ref "RX") (pin "K") (pinfunction "K_K") (pintype "bidirectional"))
    )
    (net (code "107") (name "Net-(IC24-P$2)") (class "Default")
      (node (ref "IC24") (pin "2") (pinfunction "P$2_2") (pintype "bidirectional"))
      (node (ref "IN") (pin "1") (pinfunction "1_1") (pintype "passive"))
      (node (ref "IN1") (pin "1") (pinfunction "S_1") (pintype "passive"))
      (node (ref "R61") (pin "1") (pinfunction "1_1") (pintype "passive"))
    )
    (net (code "108") (name "Net-(IC25-AVCC)") (class "Default")
      (node (ref "C131") (pin "1") (pinfunction "1_1") (pintype "passive"))
      (node (ref "IC25") (pin "39") (pinfunction "AVCC_39") (pintype "power_in"))
      (node (ref "L12") (pin "1") (pinfunction "1_1") (pintype "passive"))
    )
    (net (code "109") (name "Net-(IC25-PB1{slash}ADC9)") (class "Default")
      (node (ref "C140") (pin "1") (pinfunction "1_1") (pintype "passive"))
      (node (ref "IC25") (pin "5") (pinfunction "PB1/ADC9_5") (pintype "bidirectional"))
      (node (ref "R19") (pin "2") (pinfunction "2_2") (pintype "passive"))
    )
    (net (code "110") (name "Net-(IC25-PB2{slash}ADC10{slash}DAC0)") (class "Default")
      (node (ref "C122") (pin "1") (pinfunction "1_1") (pintype "passive"))
      (node (ref "IC25") (pin "6") (pinfunction "PB2/ADC10/DAC0_6") (pintype "bidirectional"))
      (node (ref "R62") (pin "2") (pinfunction "2_2") (pintype "passive"))
    )
    (net (code "111") (name "Net-(IC25-PR1{slash}XTAL1)") (class "Default")
      (node (ref "IC25") (pin "37") (pinfunction "PR1/XTAL1_37") (pintype "bidirectional"))
      (node (ref "OSC2") (pin "P$3") (pinfunction "OUTPUT_P$3") (pintype "passive"))
    )
    (net (code "112") (name "Net-(IC26-A3)") (class "Default")
      (node (ref "IC26") (pin "5") (pinfunction "A3_5") (pintype "bidirectional"))
      (node (ref "R63") (pin "2") (pinfunction "2_2") (pintype "passive"))
    )
    (net (code "113") (name "Net-(IC30-P$4)") (class "Default")
      (node (ref "IC30") (pin "4") (pinfunction "P$4_4") (pintype "bidirectional"))
      (node (ref "R69") (pin "1") (pinfunction "1_1") (pintype "passive"))
    )
    (net (code "114") (name "Net-(IC31-P$4)") (class "Default")
      (node (ref "IC31") (pin "4") (pinfunction "P$4_4") (pintype "bidirectional"))
      (node (ref "R70") (pin "1") (pinfunction "1_1") (pintype "passive"))
    )
    (net (code "115") (name "Net-(IC32-EN)") (class "Default")
      (node (ref "C109") (pin "2") (pinfunction "2_2") (pintype "passive"))
      (node (ref "C110") (pin "2") (pinfunction "2_2") (pintype "passive"))
      (node (ref "IC32") (pin "P$1") (pinfunction "IN_P$1") (pintype "bidirectional"))
      (node (ref "IC32") (pin "P$5") (pinfunction "EN_P$5") (pintype "bidirectional"))
      (node (ref "L11") (pin "2") (pinfunction "2_2") (pintype "passive"))
    )
    (net (code "116") (name "Net-(IC32-NR{slash}FB)") (class "Default")
      (node (ref "IC32") (pin "P$4") (pinfunction "NR/FB_P$4") (pintype "bidirectional"))
      (node (ref "R72") (pin "2") (pinfunction "2_2") (pintype "passive"))
      (node (ref "R73") (pin "1") (pinfunction "1_1") (pintype "passive"))
    )
    (net (code "117") (name "Net-(R58-Pad1)") (class "Default")
      (node (ref "R58") (pin "1") (pinfunction "1_1") (pintype "passive"))
      (node (ref "TX") (pin "A") (pinfunction "A_A") (pintype "bidirectional"))
    )
    (net (code "118") (name "Net-(R59-Pad1)") (class "Default")
      (node (ref "R59") (pin "1") (pinfunction "1_1") (pintype "passive"))
      (node (ref "RX") (pin "A") (pinfunction "A_A") (pintype "bidirectional"))
    )
    (net (code "119") (name "Net-(R66-Pad1)") (class "Default")
      (node (ref "R66") (pin "1") (pinfunction "1_1") (pintype "passive"))
      (node (ref "STATE") (pin "A") (pinfunction "A_A") (pintype "bidirectional"))
    )
    (net (code "120") (name "Net-(R75-Pad1)") (class "Default")
      (node (ref "R75") (pin "1") (pinfunction "1_1") (pintype "passive"))
      (node (ref "TX1") (pin "A") (pinfunction "A_A") (pintype "bidirectional"))
    )
    (net (code "121") (name "Net-(R76-Pad1)") (class "Default")
      (node (ref "R76") (pin "1") (pinfunction "1_1") (pintype "passive"))
      (node (ref "TX2") (pin "A") (pinfunction "A_A") (pintype "bidirectional"))
    )
    (net (code "122") (name "Net-(R77-Pad1)") (class "Default")
      (node (ref "R77") (pin "1") (pinfunction "1_1") (pintype "passive"))
      (node (ref "TX3") (pin "A") (pinfunction "A_A") (pintype "bidirectional"))
    )
    (net (code "123") (name "Net-(USB1-2)") (class "Default")
      (node (ref "IC15") (pin "P$1") (pinfunction "IO1_P$1") (pintype "bidirectional"))
      (node (ref "USB1") (pin "P$2") (pinfunction "2_P$2") (pintype "bidirectional"))
    )
    (net (code "124") (name "Net-(USB1-3)") (class "Default")
      (node (ref "IC15") (pin "P$3") (pinfunction "IO2_P$3") (pintype "bidirectional"))
      (node (ref "USB1") (pin "P$3") (pinfunction "3_P$3") (pintype "bidirectional"))
    )
    (net (code "125") (name "Net-(USB1-P$1)") (class "Default")
      (node (ref "RUSB1") (pin "1") (pinfunction "1_1") (pintype "passive"))
      (node (ref "USB1") (pin "SHIELD_3") (pinfunction "P$1_SHIELD_3") (pintype "bidirectional"))
    )
    (net (code "126") (name "Net-(USB1-P$4)") (class "Default")
      (node (ref "CUSB1") (pin "1") (pinfunction "1_1") (pintype "passive"))
      (node (ref "USB1") (pin "SHIELD_4") (pinfunction "P$4_SHIELD_4") (pintype "bidirectional"))
    )
    (net (code "127") (name "Net-(USB2-2)") (class "Default")
      (node (ref "IC17") (pin "P$1") (pinfunction "IO1_P$1") (pintype "bidirectional"))
      (node (ref "USB2") (pin "P$2") (pinfunction "2_P$2") (pintype "bidirectional"))
    )
    (net (code "128") (name "Net-(USB2-3)") (class "Default")
      (node (ref "IC17") (pin "P$3") (pinfunction "IO2_P$3") (pintype "bidirectional"))
      (node (ref "USB2") (pin "P$3") (pinfunction "3_P$3") (pintype "bidirectional"))
    )
    (net (code "129") (name "Net-(USB2-P$1)") (class "Default")
      (node (ref "RUSB2") (pin "1") (pinfunction "1_1") (pintype "passive"))
      (node (ref "USB2") (pin "SHIELD_1") (pinfunction "P$1_SHIELD_1") (pintype "bidirectional"))
    )
    (net (code "130") (name "Net-(USB2-P$4)") (class "Default")
      (node (ref "CUSB2") (pin "1") (pinfunction "1_1") (pintype "passive"))
      (node (ref "USB2") (pin "SHIELD_4") (pinfunction "P$4_SHIELD_4") (pintype "bidirectional"))
    )
    (net (code "131") (name "OUT00{slash}SYNC") (class "Default")
      (node (ref "IC16") (pin "22") (pinfunction "AN3/C2INA/RPB3/RB3_22") (pintype "bidirectional"))
      (node (ref "IC23") (pin "2") (pinfunction "P$2_2") (pintype "bidirectional"))
      (node (ref "IC25") (pin "21") (pinfunction "~OC0BXCK0PD1_21") (pintype "bidirectional"))
      (node (ref "IC26") (pin "4") (pinfunction "A2_4") (pintype "bidirectional"))
    )
    (net (code "132") (name "OUT01") (class "Default")
      (node (ref "IC25") (pin "13") (pinfunction "PC3/OC0D/TXD0_13") (pintype "bidirectional"))
      (node (ref "IC28") (pin "2") (pinfunction "P$2_2") (pintype "bidirectional"))
    )
    (net (code "133") (name "OUT1") (class "Default")
      (node (ref "IC28") (pin "4") (pinfunction "P$4_4") (pintype "bidirectional"))
      (node (ref "X1") (pin "P4") (pinfunction "4_P4") (pintype "passive"))
    )
    (net (code "134") (name "OUT2") (class "Default")
      (node (ref "IC29") (pin "4") (pinfunction "P$4_4") (pintype "bidirectional"))
      (node (ref "X1") (pin "P3") (pinfunction "3_P3") (pintype "passive"))
    )
    (net (code "135") (name "OUT02") (class "Default")
      (node (ref "IC25") (pin "14") (pinfunction "PC4/OC1A/#SS_14") (pintype "bidirectional"))
      (node (ref "IC29") (pin "2") (pinfunction "P$2_2") (pintype "bidirectional"))
    )
    (net (code "136") (name "OUTL") (class "Default")
      (node (ref "C57") (pin "1") (pinfunction "1_1") (pintype "passive"))
      (node (ref "J3") (pin "P2") (pinfunction "2_P2") (pintype "passive"))
      (node (ref "R38") (pin "2") (pinfunction "2_2") (pintype "passive"))
    )
    (net (code "137") (name "OUTR") (class "Default")
      (node (ref "C81") (pin "1") (pinfunction "1_1") (pintype "passive"))
      (node (ref "J4") (pin "P2") (pinfunction "2_P2") (pintype "passive"))
      (node (ref "R54") (pin "2") (pinfunction "2_2") (pintype "passive"))
    )
    (net (code "138") (name "OUT_BNC") (class "Default")
      (node (ref "IC23") (pin "4") (pinfunction "P$4_4") (pintype "bidirectional"))
      (node (ref "OUT") (pin "1") (pinfunction "1_1") (pintype "passive"))
      (node (ref "OUT1") (pin "1") (pinfunction "S_1") (pintype "passive"))
    )
    (net (code "139") (name "OUT_RJ") (class "Default")
      (node (ref "IC26") (pin "12") (pinfunction "B3_12") (pintype "bidirectional"))
      (node (ref "J1") (pin "3") (pinfunction "3_3") (pintype "passive"))
    )
    (net (code "140") (name "PAR0") (class "Default")
      (node (ref "IC16") (pin "17") (pinfunction "TMS/EBIA16/AN24/RA0_17") (pintype "bidirectional"))
      (node (ref "IC25") (pin "40") (pinfunction "PA0/ADC0/AREF_40") (pintype "bidirectional"))
    )
    (net (code "141") (name "PAR1") (class "Default")
      (node (ref "IC16") (pin "38") (pinfunction "TCK/EBIA19/AN29/RA1_38") (pintype "bidirectional"))
      (node (ref "IC25") (pin "41") (pinfunction "PA1/ADC1_41") (pintype "bidirectional"))
    )
    (net (code "142") (name "PAR2") (class "Default")
      (node (ref "IC16") (pin "59") (pinfunction "~{EBICS0}/SCL2/RA2_59") (pintype "bidirectional"))
      (node (ref "IC25") (pin "42") (pinfunction "PA2/ADC2_42") (pintype "bidirectional"))
    )
    (net (code "143") (name "PAR3") (class "Default")
      (node (ref "IC16") (pin "60") (pinfunction "EBIRDY1/SDA2/RA3_60") (pintype "bidirectional"))
      (node (ref "IC25") (pin "43") (pinfunction "PA3/ADC3_43") (pintype "bidirectional"))
    )
    (net (code "144") (name "PAR4") (class "Default")
      (node (ref "IC16") (pin "61") (pinfunction "EBIA14/PMCS1/PMA14/RA4_61") (pintype "bidirectional"))
      (node (ref "IC25") (pin "44") (pinfunction "PA4/ADC4_44") (pintype "bidirectional"))
    )
    (net (code "145") (name "PAR5") (class "Default")
      (node (ref "IC16") (pin "2") (pinfunction "EBIA5/AN34/PMA5/RA5_2") (pintype "bidirectional"))
      (node (ref "IC25") (pin "1") (pinfunction "PA5/ADC5_1") (pintype "bidirectional"))
    )
    (net (code "146") (name "PAR6") (class "Default")
      (node (ref "IC16") (pin "89") (pinfunction "TRCLK/SQICLK/RA6_89") (pintype "bidirectional"))
      (node (ref "IC25") (pin "2") (pinfunction "PA6/ADC6_2") (pintype "bidirectional"))
    )
    (net (code "147") (name "PAR7") (class "Default")
      (node (ref "IC16") (pin "90") (pinfunction "TRD3/SQID3/RA7_90") (pintype "bidirectional"))
      (node (ref "IC25") (pin "3") (pinfunction "PA7/ADC7/AC0-OUT_3") (pintype "bidirectional"))
    )
    (net (code "148") (name "PDI-CLK") (class "Default")
      (node (ref "IC25") (pin "35") (pinfunction "RESET/PDI-CLK_35") (pintype "input"))
      (node (ref "PDI") (pin "5") (pinfunction "5_5") (pintype "passive"))
    )
    (net (code "149") (name "PDI-DATA") (class "Default")
      (node (ref "IC25") (pin "34") (pinfunction "PDI-DATA_34") (pintype "bidirectional"))
      (node (ref "PDI") (pin "1") (pinfunction "1_1") (pintype "passive"))
    )
    (net (code "150") (name "PGEC2") (class "Default")
      (node (ref "IC16") (pin "26") (pinfunction "PGEC2/AN46/RPB6/RB6_26") (pintype "bidirectional"))
      (node (ref "JP1") (pin "5") (pinfunction "5_5") (pintype "passive"))
    )
    (net (code "151") (name "PGED2") (class "Default")
      (node (ref "IC16") (pin "27") (pinfunction "PGED2/AN47/RPB7/RB7_27") (pintype "bidirectional"))
      (node (ref "JP1") (pin "4") (pinfunction "4_4") (pintype "passive"))
    )
    (net (code "152") (name "PMD0") (class "Default")
      (node (ref "IC13") (pin "P29") (pinfunction "I/O0_P29") (pintype "bidirectional"))
      (node (ref "IC16") (pin "91") (pinfunction "EBID0/PMD0/RE0_91") (pintype "bidirectional"))
    )
    (net (code "153") (name "PMD1") (class "Default")
      (node (ref "IC13") (pin "P30") (pinfunction "I/O1_P30") (pintype "bidirectional"))
      (node (ref "IC16") (pin "94") (pinfunction "EBID1/PMD1/RE1_94") (pintype "bidirectional"))
    )
    (net (code "154") (name "PMD2") (class "Default")
      (node (ref "IC13") (pin "P31") (pinfunction "I/O2_P31") (pintype "bidirectional"))
      (node (ref "IC16") (pin "98") (pinfunction "EBID2/PMD2/RE2_98") (pintype "bidirectional"))
    )
    (net (code "155") (name "PMD3") (class "Default")
      (node (ref "IC13") (pin "P32") (pinfunction "I/O3_P32") (pintype "bidirectional"))
      (node (ref "IC16") (pin "99") (pinfunction "EBID3/RPE3/PMD3/RE3_99") (pintype "bidirectional"))
    )
    (net (code "156") (name "PMD4") (class "Default")
      (node (ref "IC13") (pin "P41") (pinfunction "I/O4_P41") (pintype "bidirectional"))
      (node (ref "IC16") (pin "100") (pinfunction "EBID4/AN18/PMD4/RE4_100") (pintype "bidirectional"))
    )
    (net (code "157") (name "PMD5") (class "Default")
      (node (ref "IC13") (pin "P42") (pinfunction "I/O5_P42") (pintype "bidirectional"))
      (node (ref "IC16") (pin "3") (pinfunction "EBID5/AN17/RPE5/PMD5/RE5_3") (pintype "bidirectional"))
    )
    (net (code "158") (name "PMD6") (class "Default")
      (node (ref "IC13") (pin "P43") (pinfunction "I/O6_P43") (pintype "bidirectional"))
      (node (ref "IC16") (pin "4") (pinfunction "EBID6/AN16/PMD6/RE6_4") (pintype "bidirectional"))
    )
    (net (code "159") (name "PMD7") (class "Default")
      (node (ref "IC13") (pin "P44") (pinfunction "I/O7_P44") (pintype "bidirectional"))
      (node (ref "IC16") (pin "5") (pinfunction "EBID7/AN15/PMD7/RE7_5") (pintype "bidirectional"))
    )
    (net (code "160") (name "PMD8") (class "Default")
      (node (ref "IC13") (pin "P26") (pinfunction "I/O8_P26") (pintype "bidirectional"))
    )
    (net (code "161") (name "PMD9") (class "Default")
      (node (ref "IC13") (pin "P27") (pinfunction "I/O9_P27") (pintype "bidirectional"))
    )
    (net (code "162") (name "PMD10") (class "Default")
      (node (ref "IC13") (pin "P28") (pinfunction "I/O10_P28") (pintype "bidirectional"))
    )
    (net (code "163") (name "PMD11") (class "Default")
      (node (ref "IC13") (pin "P33") (pinfunction "I/O11_P33") (pintype "bidirectional"))
    )
    (net (code "164") (name "PMD12") (class "Default")
      (node (ref "IC13") (pin "P40") (pinfunction "I/O12_P40") (pintype "bidirectional"))
    )
    (net (code "165") (name "PMD13") (class "Default")
      (node (ref "IC13") (pin "P45") (pinfunction "I/O13_P45") (pintype "bidirectional"))
    )
    (net (code "166") (name "PMD14") (class "Default")
      (node (ref "IC13") (pin "P46") (pinfunction "I/O14_P46") (pintype "bidirectional"))
    )
    (net (code "167") (name "PMD15") (class "Default")
      (node (ref "IC13") (pin "P47") (pinfunction "I/O15_P47") (pintype "bidirectional"))
    )
    (net (code "168") (name "RE") (class "Default")
      (node (ref "IC13") (pin "P8") (pinfunction "RE#_P8") (pintype "bidirectional"))
      (node (ref "IC16") (pin "9") (pinfunction "~{EBIOE}/AN19/RPC4/PMRD/RC4_9") (pintype "bidirectional"))
    )
    (net (code "169") (name "REFCLK{slash}MCLK") (class "Default")
      (node (ref "IC16") (pin "72") (pinfunction "SOSCI/RPC13/RC13_72") (pintype "bidirectional"))
      (node (ref "IC6") (pin "P27") (pinfunction "MCLK_P27") (pintype "bidirectional"))
      (node (ref "JP3") (pin "4") (pinfunction "4_4") (pintype "passive"))
    )
    (net (code "170") (name "RTS") (class "Default")
      (node (ref "IC21") (pin "13") (pinfunction "B2_13") (pintype "bidirectional"))
      (node (ref "IC25") (pin "28") (pinfunction "~{OC0ASDAPE0}_28") (pintype "bidirectional"))
    )
    (net (code "171") (name "RXD") (class "Default")
      (node (ref "IC21") (pin "12") (pinfunction "B3_12") (pintype "bidirectional"))
      (node (ref "IC34") (pin "4") (pinfunction "OUT_4") (pintype "bidirectional"))
      (node (ref "IC35") (pin "4") (pinfunction "OUT_4") (pintype "bidirectional"))
    )
    (net (code "172") (name "RXD_") (class "Default")
      (node (ref "IC25") (pin "33") (pinfunction "~TXD0OC0DPE3_33") (pintype "bidirectional"))
      (node (ref "IC35") (pin "2") (pinfunction "IN_2") (pintype "bidirectional"))
    )
    (net (code "173") (name "SCK1") (class "Default")
      (node (ref "IC16") (pin "34") (pinfunction "EBIA13/CVREFOUT/AN5/RPB10/PMA13/RB10_34") (pintype "bidirectional"))
      (node (ref "IC6") (pin "P26") (pinfunction "CCLK_P26") (pintype "bidirectional"))
    )
    (net (code "174") (name "SCK{slash}BIT_CLK") (class "Default")
      (node (ref "IC16") (pin "69") (pinfunction "RPD10/SCK4/RD10_69") (pintype "bidirectional"))
      (node (ref "IC6") (pin "P3") (pinfunction "BCLK/EF_BCLK_P3") (pintype "bidirectional"))
      (node (ref "JP3") (pin "2") (pinfunction "2_2") (pintype "passive"))
    )
    (net (code "175") (name "SDO1") (class "Default")
      (node (ref "IC16") (pin "33") (pinfunction "EBIA7/AN49/RPB9/PMA7/RB9_33") (pintype "bidirectional"))
      (node (ref "IC6") (pin "P24") (pinfunction "CDATA_P24") (pintype "bidirectional"))
    )
    (net (code "176") (name "SDO{slash}SD") (class "Default")
      (node (ref "IC16") (pin "70") (pinfunction "EMDC/AEMDC/RPD11/RD11_70") (pintype "bidirectional"))
      (node (ref "IC6") (pin "P4") (pinfunction "SDATA/EF_LDATA_P4") (pintype "bidirectional"))
      (node (ref "JP3") (pin "1") (pinfunction "1_1") (pintype "passive"))
    )
    (net (code "177") (name "SS{slash}WORD_CLK") (class "Default")
      (node (ref "IC16") (pin "68") (pinfunction "EBIA15/RPD9/PMCS2/PMA15/RD9_68") (pintype "bidirectional"))
      (node (ref "IC6") (pin "P2") (pinfunction "LRCLK/EF-WCLK_P2") (pintype "bidirectional"))
      (node (ref "JP3") (pin "3") (pinfunction "3_3") (pintype "passive"))
    )
    (net (code "178") (name "STATE") (class "Default")
      (node (ref "IC25") (pin "36") (pinfunction "PR0/XTAL2_36") (pintype "bidirectional"))
      (node (ref "R66") (pin "2") (pinfunction "2_2") (pintype "passive"))
    )
    (net (code "179") (name "TP0") (class "Default")
      (node (ref "IC16") (pin "96") (pinfunction "TRD1/SQID1/RG12_96") (pintype "bidirectional"))
      (node (ref "TP0") (pin "TP") (pinfunction "TP_TP") (pintype "input"))
    )
    (net (code "180") (name "TP1") (class "Default")
      (node (ref "IC16") (pin "97") (pinfunction "TRD0/SQID0/RG13_97") (pintype "bidirectional"))
      (node (ref "TP1") (pin "TP") (pinfunction "TP_TP") (pintype "input"))
    )
    (net (code "181") (name "TXD") (class "Default")
      (node (ref "IC21") (pin "14") (pinfunction "B1_14") (pintype "bidirectional"))
      (node (ref "IC25") (pin "32") (pinfunction "~RXD0OC0CPE2_32") (pintype "bidirectional"))
      (node (ref "IC33") (pin "2") (pinfunction "IN_2") (pintype "bidirectional"))
    )
    (net (code "182") (name "UART1_RX") (class "Default")
      (node (ref "IC25") (pin "23") (pinfunction "~OC0DTXD0PD3_23") (pintype "bidirectional"))
      (node (ref "IC27") (pin "3") (pinfunction "D_3") (pintype "bidirectional"))
    )
    (net (code "183") (name "UART1_TX") (class "Default")
      (node (ref "IC25") (pin "22") (pinfunction "~OC0CRXD0PD2_22") (pintype "bidirectional"))
      (node (ref "IC27") (pin "2") (pinfunction "R_2") (pintype "bidirectional"))
    )
    (net (code "184") (name "UART2_RX") (class "Default")
      (node (ref "IC16") (pin "7") (pinfunction "EBIA12/AN21/RPC2/PMA12/RC2_7") (pintype "bidirectional"))
      (node (ref "IC25") (pin "26") (pinfunction "~RXD1MISOPD6_26") (pintype "bidirectional"))
      (node (ref "IC33") (pin "4") (pinfunction "OUT_4") (pintype "bidirectional"))
    )
    (net (code "185") (name "UART2_TX") (class "Default")
      (node (ref "IC16") (pin "25") (pinfunction "PGED1/AN0/RPB0/RB0_25") (pintype "bidirectional"))
      (node (ref "IC25") (pin "27") (pinfunction "~~{TXD1SCKCLKOPD7}_27") (pintype "bidirectional"))
      (node (ref "IC34") (pin "2") (pinfunction "IN_2") (pintype "bidirectional"))
    )
    (net (code "186") (name "UART_RX") (class "Default")
      (node (ref "IC27") (pin "8") (pinfunction "A_8") (pintype "bidirectional"))
      (node (ref "J2") (pin "1") (pinfunction "1_1") (pintype "passive"))
      (node (ref "R64") (pin "2") (pinfunction "2_2") (pintype "passive"))
    )
    (net (code "187") (name "UART_TX") (class "Default")
      (node (ref "IC27") (pin "5") (pinfunction "Y_5") (pintype "bidirectional"))
      (node (ref "J2") (pin "4") (pinfunction "4_4") (pintype "passive"))
      (node (ref "R65") (pin "1") (pinfunction "1_1") (pintype "passive"))
    )
    (net (code "188") (name "UC_IO0") (class "Default")
      (node (ref "IC16") (pin "20") (pinfunction "AN45/C1INA/RPB5/RB5_20") (pintype "bidirectional"))
      (node (ref "IC25") (pin "11") (pinfunction "PC1/OC0B/XCK0/SCL_11") (pintype "bidirectional"))
    )
    (net (code "189") (name "UC_IO1") (class "Default")
      (node (ref "IC16") (pin "21") (pinfunction "AN4/C1INB/RB4_21") (pintype "bidirectional"))
      (node (ref "IC25") (pin "15") (pinfunction "PC5/OC1B/MOSI/XCK1_15") (pintype "bidirectional"))
    )
    (net (code "190") (name "UC_IO2") (class "Default")
      (node (ref "IC16") (pin "10") (pinfunction "AN14/C1IND/ECOL/RPG6/SCK2/RG6_10") (pintype "bidirectional"))
      (node (ref "IC25") (pin "16") (pinfunction "PC6/MISO/RXD1_16") (pintype "bidirectional"))
    )
    (net (code "191") (name "UC_IO3") (class "Default")
      (node (ref "IC16") (pin "24") (pinfunction "PGEC1/AN1/RPB1/RB1_24") (pintype "bidirectional"))
      (node (ref "IC25") (pin "17") (pinfunction "PC7/SCK/TXD1/CLKO/EVO_17") (pintype "bidirectional"))
      (node (ref "IC33") (pin "1") (pinfunction "OE_1") (pintype "bidirectional"))
      (node (ref "IC34") (pin "1") (pinfunction "OE_1") (pintype "bidirectional"))
      (node (ref "IC35") (pin "1") (pinfunction "~{OE}_1") (pintype "bidirectional"))
    )
    (net (code "192") (name "UC_IO4") (class "Default")
      (node (ref "IC16") (pin "23") (pinfunction "AN2/C2INB/RPB2/RB2_23") (pintype "bidirectional"))
      (node (ref "IC25") (pin "25") (pinfunction "~XCK1MOSIPD5_25") (pintype "bidirectional"))
    )
    (net (code "193") (name "USB") (class "Default")
      (node (ref "IC16") (pin "85") (pinfunction "EBID11/ETXD1/RPF0/PMD11/RF0_85") (pintype "bidirectional"))
      (node (ref "R77") (pin "2") (pinfunction "2_2") (pintype "passive"))
    )
    (net (code "194") (name "USB5V") (class "Default")
      (node (ref "C111") (pin "1") (pinfunction "1_1") (pintype "passive"))
      (node (ref "C112") (pin "+") (pinfunction "+_+") (pintype "passive"))
      (node (ref "C114") (pin "1") (pinfunction "1_1") (pintype "passive"))
      (node (ref "C117") (pin "1") (pinfunction "1_1") (pintype "passive"))
      (node (ref "IC19") (pin "20") (pinfunction "VCC_20") (pintype "power_in"))
      (node (ref "IC19") (pin "4") (pinfunction "VCCIO_4") (pintype "power_in"))
      (node (ref "IC21") (pin "1") (pinfunction "VDD1_1") (pintype "bidirectional"))
      (node (ref "IC21") (pin "7") (pinfunction "NC/EN_7") (pintype "bidirectional"))
      (node (ref "L10") (pin "1") (pinfunction "1_1") (pintype "passive"))
      (node (ref "R58") (pin "2") (pinfunction "2_2") (pintype "passive"))
      (node (ref "R59") (pin "2") (pinfunction "2_2") (pintype "passive"))
    )
    (net (code "195") (name "USBDM") (class "Default")
      (node (ref "C108") (pin "1") (pinfunction "1_1") (pintype "passive"))
      (node (ref "IC17") (pin "P$6") (pinfunction "IO1_P$6") (pintype "bidirectional"))
      (node (ref "IC19") (pin "16") (pinfunction "USBDM_16") (pintype "bidirectional"))
    )
    (net (code "196") (name "USBDP") (class "Default")
      (node (ref "C107") (pin "1") (pinfunction "1_1") (pintype "passive"))
      (node (ref "IC17") (pin "P$4") (pinfunction "IO2_P$4") (pintype "bidirectional"))
      (node (ref "IC19") (pin "15") (pinfunction "USBDP_15") (pintype "bidirectional"))
    )
    (net (code "197") (name "V+") (class "Default")
      (node (ref "C11") (pin "1") (pinfunction "1_1") (pintype "passive"))
      (node (ref "C2") (pin "+") (pinfunction "+_+") (pintype "passive"))
      (node (ref "IC2") (pin "17") (pinfunction "PVIN1_17") (pintype "bidirectional"))
      (node (ref "IC2") (pin "18") (pinfunction "PVINSYS_18") (pintype "bidirectional"))
      (node (ref "IC2") (pin "19") (pinfunction "PVIN2_19") (pintype "bidirectional"))
      (node (ref "JACK") (pin "P1") (pinfunction "1_P1") (pintype "passive"))
      (node (ref "L11") (pin "1") (pinfunction "1_1") (pintype "passive"))
      (node (ref "L5") (pin "1") (pinfunction "1_1") (pintype "passive"))
      (node (ref "L6") (pin "1") (pinfunction "1_1") (pintype "passive"))
      (node (ref "L9") (pin "1") (pinfunction "1_1") (pintype "passive"))
    )
    (net (code "198") (name "VBUS") (class "Default")
      (node (ref "IC16") (pin "51") (pinfunction "VBUS_51") (pintype "bidirectional"))
      (node (ref "L13") (pin "1") (pinfunction "1_1") (pintype "passive"))
    )
    (net (code "199") (name "VCC") (class "Default")
      (node (ref "C100") (pin "1") (pinfunction "1_1") (pintype "passive"))
      (node (ref "C102") (pin "1") (pinfunction "1_1") (pintype "passive"))
      (node (ref "C139") (pin "1") (pinfunction "1_1") (pintype "passive"))
      (node (ref "C84") (pin "1") (pinfunction "1_1") (pintype "passive"))
      (node (ref "C86") (pin "1") (pinfunction "1_1") (pintype "passive"))
      (node (ref "C88") (pin "1") (pinfunction "1_1") (pintype "passive"))
      (node (ref "C89") (pin "1") (pinfunction "1_1") (pintype "passive"))
      (node (ref "C92") (pin "1") (pinfunction "1_1") (pintype "passive"))
      (node (ref "C93") (pin "1") (pinfunction "1_1") (pintype "passive"))
      (node (ref "C94") (pin "1") (pinfunction "1_1") (pintype "passive"))
      (node (ref "C95") (pin "1") (pinfunction "1_1") (pintype "passive"))
      (node (ref "C96") (pin "1") (pinfunction "1_1") (pintype "passive"))
      (node (ref "C97") (pin "1") (pinfunction "1_1") (pintype "passive"))
      (node (ref "C98") (pin "1") (pinfunction "1_1") (pintype "passive"))
      (node (ref "C99") (pin "1") (pinfunction "1_1") (pintype "passive"))
      (node (ref "IC13") (pin "P12") (pinfunction "VCC_P12") (pintype "bidirectional"))
      (node (ref "IC13") (pin "P37") (pinfunction "VCC_P37") (pintype "bidirectional"))
      (node (ref "IC13") (pin "P39") (pinfunction "VCC_P39") (pintype "bidirectional"))
      (node (ref "IC16") (pin "14") (pinfunction "VDD_14") (pintype "bidirectional"))
      (node (ref "IC16") (pin "30") (pinfunction "AVDD_30") (pintype "bidirectional"))
      (node (ref "IC16") (pin "37") (pinfunction "VDD_37") (pintype "bidirectional"))
      (node (ref "IC16") (pin "46") (pinfunction "VDD_46") (pintype "bidirectional"))
      (node (ref "IC16") (pin "52") (pinfunction "VUSB3V3_52") (pintype "bidirectional"))
      (node (ref "IC16") (pin "62") (pinfunction "VDD_62") (pintype "bidirectional"))
      (node (ref "IC16") (pin "74") (pinfunction "VDD_74") (pintype "bidirectional"))
      (node (ref "IC16") (pin "83") (pinfunction "VDD_83") (pintype "bidirectional"))
      (node (ref "IC16") (pin "93") (pinfunction "VDD_93") (pintype "bidirectional"))
      (node (ref "IC18") (pin "5") (pinfunction "OUT_5") (pintype "bidirectional"))
      (node (ref "JP1") (pin "2") (pinfunction "2_2") (pintype "passive"))
      (node (ref "OSC1") (pin "P$4") (pinfunction "VDD_P$4") (pintype "passive"))
      (node (ref "OSC3") (pin "P$1") (pinfunction "EOH_P$1") (pintype "bidirectional"))
      (node (ref "OSC3") (pin "P$4") (pinfunction "VCC_P$4") (pintype "bidirectional"))
      (node (ref "R56") (pin "2") (pinfunction "2_2") (pintype "passive"))
    )
    (net (code "200") (name "VCCINT") (class "Default")
      (node (ref "C120") (pin "1") (pinfunction "1_1") (pintype "passive"))
      (node (ref "C133") (pin "1") (pinfunction "1_1") (pintype "passive"))
      (node (ref "C134") (pin "1") (pinfunction "1_1") (pintype "passive"))
      (node (ref "IC23") (pin "5") (pinfunction "P$5_5") (pintype "bidirectional"))
      (node (ref "IC28") (pin "5") (pinfunction "P$5_5") (pintype "bidirectional"))
      (node (ref "IC29") (pin "5") (pinfunction "P$5_5") (pintype "bidirectional"))
      (node (ref "JP2") (pin "2") (pinfunction "2_2") (pintype "passive"))
    )
    (net (code "201") (name "VCCIO") (class "Default")
      (node (ref "C104") (pin "1") (pinfunction "1_1") (pintype "passive"))
      (node (ref "C105") (pin "1") (pinfunction "1_1") (pintype "passive"))
      (node (ref "C116") (pin "1") (pinfunction "1_1") (pintype "passive"))
      (node (ref "C118") (pin "1") (pinfunction "1_1") (pintype "passive"))
      (node (ref "C119") (pin "1") (pinfunction "1_1") (pintype "passive"))
      (node (ref "C121") (pin "1") (pinfunction "1_1") (pintype "passive"))
      (node (ref "C123") (pin "1") (pinfunction "1_1") (pintype "passive"))
      (node (ref "C124") (pin "1") (pinfunction "1_1") (pintype "passive"))
      (node (ref "C125") (pin "1") (pinfunction "1_1") (pintype "passive"))
      (node (ref "C126") (pin "1") (pinfunction "1_1") (pintype "passive"))
      (node (ref "C127") (pin "1") (pinfunction "1_1") (pintype "passive"))
      (node (ref "C128") (pin "1") (pinfunction "1_1") (pintype "passive"))
      (node (ref "C130") (pin "1") (pinfunction "1_1") (pintype "passive"))
      (node (ref "C132") (pin "1") (pinfunction "1_1") (pintype "passive"))
      (node (ref "C135") (pin "1") (pinfunction "1_1") (pintype "passive"))
      (node (ref "C136") (pin "1") (pinfunction "1_1") (pintype "passive"))
      (node (ref "C143") (pin "1") (pinfunction "1_1") (pintype "passive"))
      (node (ref "CLKIN") (pin "1") (pinfunction "1_1") (pintype "passive"))
      (node (ref "IC20") (pin "5") (pinfunction "OUT_5") (pintype "bidirectional"))
      (node (ref "IC21") (pin "10") (pinfunction "NC/EN_10") (pintype "bidirectional"))
      (node (ref "IC21") (pin "16") (pinfunction "VDD2_16") (pintype "bidirectional"))
      (node (ref "IC22") (pin "5") (pinfunction "P$5_5") (pintype "bidirectional"))
      (node (ref "IC24") (pin "5") (pinfunction "P$5_5") (pintype "bidirectional"))
      (node (ref "IC25") (pin "19") (pinfunction "VCC_19") (pintype "power_in"))
      (node (ref "IC25") (pin "31") (pinfunction "VCC_31") (pintype "power_in"))
      (node (ref "IC25") (pin "9") (pinfunction "VCC_9") (pintype "power_in"))
      (node (ref "IC26") (pin "1") (pinfunction "VDD1_1") (pintype "bidirectional"))
      (node (ref "IC26") (pin "7") (pinfunction "NC/EN_7") (pintype "bidirectional"))
      (node (ref "IC27") (pin "1") (pinfunction "VCC_1") (pintype "bidirectional"))
      (node (ref "IC30") (pin "5") (pinfunction "P$5_5") (pintype "bidirectional"))
      (node (ref "IC31") (pin "5") (pinfunction "P$5_5") (pintype "bidirectional"))
      (node (ref "IC33") (pin "5") (pinfunction "VCC_5") (pintype "bidirectional"))
      (node (ref "IC34") (pin "5") (pinfunction "VCC_5") (pintype "bidirectional"))
      (node (ref "IC35") (pin "5") (pinfunction "VCC_5") (pintype "bidirectional"))
      (node (ref "JP2") (pin "3") (pinfunction "3_3") (pintype "passive"))
      (node (ref "L12") (pin "2") (pinfunction "2_2") (pintype "passive"))
      (node (ref "OSC2") (pin "P$4") (pinfunction "VDD_P$4") (pintype "passive"))
      (node (ref "PDI") (pin "2") (pinfunction "2_2") (pintype "passive"))
      (node (ref "R9") (pin "2") (pinfunction "2_2") (pintype "passive"))
    )
    (net (code "202") (name "VDD") (class "Default")
      (node (ref "C129") (pin "1") (pinfunction "1_1") (pintype "passive"))
      (node (ref "IC26") (pin "10") (pinfunction "NC/EN_10") (pintype "bidirectional"))
      (node (ref "IC26") (pin "11") (pinfunction "B4_11") (pintype "bidirectional"))
      (node (ref "IC26") (pin "16") (pinfunction "VDD2_16") (pintype "bidirectional"))
      (node (ref "J1") (pin "4") (pinfunction "4_4") (pintype "passive"))
    )
    (net (code "203") (name "VREF") (class "Default")
      (node (ref "C34") (pin "1") (pinfunction "1_1") (pintype "passive"))
      (node (ref "C35") (pin "+") (pinfunction "+_+") (pintype "passive"))
      (node (ref "R21") (pin "1") (pinfunction "1_1") (pintype "passive"))
      (node (ref "R22") (pin "2") (pinfunction "2_2") (pintype "passive"))
      (node (ref "R24") (pin "2") (pinfunction "2_2") (pintype "passive"))
      (node (ref "R25") (pin "2") (pinfunction "2_2") (pintype "passive"))
      (node (ref "R40") (pin "2") (pinfunction "2_2") (pintype "passive"))
      (node (ref "R41") (pin "2") (pinfunction "2_2") (pintype "passive"))
    )
    (net (code "204") (name "WE") (class "Default")
      (node (ref "IC13") (pin "P18") (pinfunction "WE#_P18") (pintype "bidirectional"))
      (node (ref "IC16") (pin "8") (pinfunction "~{EBIWE}/AN20/RPC3/PMWR/RC3_8") (pintype "bidirectional"))
    )
    (net (code "205") (name "WP") (class "Default")
      (node (ref "IC13") (pin "P19") (pinfunction "WP#_P19") (pintype "bidirectional"))
      (node (ref "IC16") (pin "12") (pinfunction "EBIA3/AN12/C2IND/ERXDV/ECRSDV..._12") (pintype "bidirectional"))
    )
    (net (code "206") (name "ZEROL") (class "Default")
      (node (ref "IC16") (pin "56") (pinfunction "RPF3/USBID/RF3_56") (pintype "bidirectional"))
      (node (ref "IC6") (pin "P21") (pinfunction "ZEROL_P21") (pintype "bidirectional"))
    )
    (net (code "207") (name "ZEROR") (class "Default")
      (node (ref "IC16") (pin "58") (pinfunction "EBIRDY2/RPF8/SCL3/RF8_58") (pintype "bidirectional"))
      (node (ref "IC6") (pin "P20") (pinfunction "ZEROR_P20") (pintype "bidirectional"))
    )
    (net (code "208") (name "unconnected-(IC2-SEQ-Pad5)") (class "Default")
      (node (ref "IC2") (pin "5") (pinfunction "SEQ_5") (pintype "bidirectional"))
    )
    (net (code "209") (name "unconnected-(IC2-SS-Pad10)") (class "Default")
      (node (ref "IC2") (pin "10") (pinfunction "SS_10") (pintype "bidirectional"))
    )
    (net (code "210") (name "unconnected-(IC4-~{ERR}-Pad6)") (class "Default")
      (node (ref "IC4") (pin "6") (pinfunction "~{ERR}_6") (pintype "bidirectional"))
    )
    (net (code "211") (name "unconnected-(IC5-~{ERR}-Pad6)") (class "Default")
      (node (ref "IC5") (pin "6") (pinfunction "~{ERR}_6") (pintype "bidirectional"))
    )
    (net (code "212") (name "unconnected-(IC6-DSD_LDATA-PadP7)") (class "Default")
      (node (ref "IC6") (pin "P7") (pinfunction "DSD_LDATA_P7") (pintype "bidirectional"))
    )
    (net (code "213") (name "unconnected-(IC6-DSD_RDATA-PadP8)") (class "Default")
      (node (ref "IC6") (pin "P8") (pinfunction "DSD_RDATA_P8") (pintype "bidirectional"))
    )
    (net (code "214") (name "unconnected-(IC6-DSD_SCLK-PadP6)") (class "Default")
      (node (ref "IC6") (pin "P6") (pinfunction "DSD_SCLK_P6") (pintype "bidirectional"))
    )
    (net (code "215") (name "unconnected-(IC6-EF_RDATA-PadP5)") (class "Default")
      (node (ref "IC6") (pin "P5") (pinfunction "EF_RDATA_P5") (pintype "bidirectional"))
    )
    (net (code "216") (name "unconnected-(IC7-COMP-Pad8)") (class "Default")
      (node (ref "IC7") (pin "8") (pinfunction "COMP_8") (pintype "bidirectional"))
    )
    (net (code "217") (name "unconnected-(IC7-NL+-Pad1)") (class "Default")
      (node (ref "IC7") (pin "1") (pinfunction "NL+_1") (pintype "bidirectional"))
    )
    (net (code "218") (name "unconnected-(IC7-NL--Pad5)") (class "Default")
      (node (ref "IC7") (pin "5") (pinfunction "NL-_5") (pintype "bidirectional"))
    )
    (net (code "219") (name "unconnected-(IC8-COMP-Pad8)") (class "Default")
      (node (ref "IC8") (pin "8") (pinfunction "COMP_8") (pintype "bidirectional"))
    )
    (net (code "220") (name "unconnected-(IC8-NL+-Pad1)") (class "Default")
      (node (ref "IC8") (pin "1") (pinfunction "NL+_1") (pintype "bidirectional"))
    )
    (net (code "221") (name "unconnected-(IC8-NL--Pad5)") (class "Default")
      (node (ref "IC8") (pin "5") (pinfunction "NL-_5") (pintype "bidirectional"))
    )
    (net (code "222") (name "unconnected-(IC9-COMP-Pad8)") (class "Default")
      (node (ref "IC9") (pin "8") (pinfunction "COMP_8") (pintype "bidirectional"))
    )
    (net (code "223") (name "unconnected-(IC9-NL+-Pad1)") (class "Default")
      (node (ref "IC9") (pin "1") (pinfunction "NL+_1") (pintype "bidirectional"))
    )
    (net (code "224") (name "unconnected-(IC9-NL--Pad5)") (class "Default")
      (node (ref "IC9") (pin "5") (pinfunction "NL-_5") (pintype "bidirectional"))
    )
    (net (code "225") (name "unconnected-(IC10-COMP-Pad8)") (class "Default")
      (node (ref "IC10") (pin "8") (pinfunction "COMP_8") (pintype "bidirectional"))
    )
    (net (code "226") (name "unconnected-(IC10-NL+-Pad1)") (class "Default")
      (node (ref "IC10") (pin "1") (pinfunction "NL+_1") (pintype "bidirectional"))
    )
    (net (code "227") (name "unconnected-(IC10-NL--Pad5)") (class "Default")
      (node (ref "IC10") (pin "5") (pinfunction "NL-_5") (pintype "bidirectional"))
    )
    (net (code "228") (name "unconnected-(IC11-COMP-Pad8)") (class "Default")
      (node (ref "IC11") (pin "8") (pinfunction "COMP_8") (pintype "bidirectional"))
    )
    (net (code "229") (name "unconnected-(IC11-NL+-Pad1)") (class "Default")
      (node (ref "IC11") (pin "1") (pinfunction "NL+_1") (pintype "bidirectional"))
    )
    (net (code "230") (name "unconnected-(IC11-NL--Pad5)") (class "Default")
      (node (ref "IC11") (pin "5") (pinfunction "NL-_5") (pintype "bidirectional"))
    )
    (net (code "231") (name "unconnected-(IC12-COMP-Pad8)") (class "Default")
      (node (ref "IC12") (pin "8") (pinfunction "COMP_8") (pintype "bidirectional"))
    )
    (net (code "232") (name "unconnected-(IC12-NL+-Pad1)") (class "Default")
      (node (ref "IC12") (pin "1") (pinfunction "NL+_1") (pintype "bidirectional"))
    )
    (net (code "233") (name "unconnected-(IC12-NL--Pad5)") (class "Default")
      (node (ref "IC12") (pin "5") (pinfunction "NL-_5") (pintype "bidirectional"))
    )
    (net (code "234") (name "unconnected-(IC13-NC-PadP1)") (class "Default")
      (node (ref "IC13") (pin "P1") (pinfunction "NC_P1") (pintype "bidirectional"))
    )
    (net (code "235") (name "unconnected-(IC13-NC-PadP2)") (class "Default")
      (node (ref "IC13") (pin "P2") (pinfunction "NC_P2") (pintype "bidirectional"))
    )
    (net (code "236") (name "unconnected-(IC13-NC-PadP3)") (class "Default")
      (node (ref "IC13") (pin "P3") (pinfunction "NC_P3") (pintype "bidirectional"))
    )
    (net (code "237") (name "unconnected-(IC13-NC-PadP4)") (class "Default")
      (node (ref "IC13") (pin "P4") (pinfunction "NC_P4") (pintype "bidirectional"))
    )
    (net (code "238") (name "unconnected-(IC13-NC-PadP5)") (class "Default")
      (node (ref "IC13") (pin "P5") (pinfunction "NC_P5") (pintype "bidirectional"))
    )
    (net (code "239") (name "unconnected-(IC13-NC-PadP6)") (class "Default")
      (node (ref "IC13") (pin "P6") (pinfunction "NC_P6") (pintype "bidirectional"))
    )
    (net (code "240") (name "unconnected-(IC13-NC-PadP10)") (class "Default")
      (node (ref "IC13") (pin "P10") (pinfunction "NC_P10") (pintype "bidirectional"))
    )
    (net (code "241") (name "unconnected-(IC13-NC-PadP11)") (class "Default")
      (node (ref "IC13") (pin "P11") (pinfunction "NC_P11") (pintype "bidirectional"))
    )
    (net (code "242") (name "unconnected-(IC13-NC-PadP14)") (class "Default")
      (node (ref "IC13") (pin "P14") (pinfunction "NC_P14") (pintype "bidirectional"))
    )
    (net (code "243") (name "unconnected-(IC13-NC-PadP15)") (class "Default")
      (node (ref "IC13") (pin "P15") (pinfunction "NC_P15") (pintype "bidirectional"))
    )
    (net (code "244") (name "unconnected-(IC13-NC-PadP20)") (class "Default")
      (node (ref "IC13") (pin "P20") (pinfunction "NC_P20") (pintype "bidirectional"))
    )
    (net (code "245") (name "unconnected-(IC13-NC-PadP21)") (class "Default")
      (node (ref "IC13") (pin "P21") (pinfunction "NC_P21") (pintype "bidirectional"))
    )
    (net (code "246") (name "unconnected-(IC13-NC-PadP22)") (class "Default")
      (node (ref "IC13") (pin "P22") (pinfunction "NC_P22") (pintype "bidirectional"))
    )
    (net (code "247") (name "unconnected-(IC13-NC-PadP23)") (class "Default")
      (node (ref "IC13") (pin "P23") (pinfunction "NC_P23") (pintype "bidirectional"))
    )
    (net (code "248") (name "unconnected-(IC13-NC-PadP24)") (class "Default")
      (node (ref "IC13") (pin "P24") (pinfunction "NC_P24") (pintype "bidirectional"))
    )
    (net (code "249") (name "unconnected-(IC13-NC-PadP35)") (class "Default")
      (node (ref "IC13") (pin "P35") (pinfunction "NC_P35") (pintype "bidirectional"))
    )
    (net (code "250") (name "unconnected-(IC13-NC-PadP38)") (class "Default")
      (node (ref "IC13") (pin "P38") (pinfunction "NC_P38") (pintype "bidirectional"))
    )
    (net (code "251") (name "unconnected-(IC13-VCC-PadP34)") (class "Default")
      (node (ref "IC13") (pin "P34") (pinfunction "VCC_P34") (pintype "bidirectional"))
    )
    (net (code "252") (name "unconnected-(IC16-AETXCLK{slash}RPA14{slash}SCL1{slash}RA14-Pad66)") (class "Default")
      (node (ref "IC16") (pin "66") (pinfunction "AETXCLK/RPA14/SCL1/RA14_66") (pintype "bidirectional"))
    )
    (net (code "253") (name "unconnected-(IC16-AETXEN{slash}RPA15{slash}SDA1{slash}RA15-Pad67)") (class "Default")
      (node (ref "IC16") (pin "67") (pinfunction "AETXEN/RPA15/SDA1/RA15_67") (pintype "bidirectional"))
    )
    (net (code "254") (name "unconnected-(IC16-AN6{slash}ERXERR{slash}AETXERR{slash}RB11-Pad35)") (class "Default")
      (node (ref "IC16") (pin "35") (pinfunction "AN6/ERXERR/AETXERR/RB11_35") (pintype "input"))
    )
    (net (code "255") (name "unconnected-(IC16-AN23{slash}AERXERR{slash}RG15-Pad1)") (class "Default")
      (node (ref "IC16") (pin "1") (pinfunction "AN23/AERXERR/RG15_1") (pintype "bidirectional"))
    )
    (net (code "256") (name "unconnected-(IC16-AN25{slash}AERXD0{slash}RPE8{slash}RE8-Pad18)") (class "Default")
      (node (ref "IC16") (pin "18") (pinfunction "AN25/AERXD0/RPE8/RE8_18") (pintype "bidirectional"))
    )
    (net (code "257") (name "unconnected-(IC16-AN26{slash}AERXD1{slash}RPE9{slash}RE9-Pad19)") (class "Default")
      (node (ref "IC16") (pin "19") (pinfunction "AN26/AERXD1/RPE9/RE9_19") (pintype "bidirectional"))
    )
    (net (code "258") (name "unconnected-(IC16-AN32{slash}AETXD0{slash}RPD14{slash}RD14-Pad47)") (class "Default")
      (node (ref "IC16") (pin "47") (pinfunction "AN32/AETXD0/RPD14/RD14_47") (pintype "bidirectional"))
    )
    (net (code "259") (name "unconnected-(IC16-AN33{slash}AETXD1{slash}RPD15{slash}SCK6{slash}RD15-Pad48)") (class "Default")
      (node (ref "IC16") (pin "48") (pinfunction "AN33/AETXD1/RPD15/SCK6/RD15_48") (pintype "bidirectional"))
    )
    (net (code "260") (name "unconnected-(IC16-EBIA0{slash}AN10{slash}ERXD3{slash}AETXD2{slash}RPB15{slash}OCFB{slash}PMA0{slash}RB15-Pad44)") (class "Default")
      (node (ref "IC16") (pin "44") (pinfunction "EBIA0/AN10/ERXD3/AETXD2/RPB15/OCFB/PMA0/RB15_44") (pintype "bidirectional"))
    )
    (net (code "261") (name "unconnected-(IC16-EBIA1{slash}AN9{slash}ERXD2{slash}AETXD3{slash}RPB14{slash}SCK3{slash}PMA1{slash}RB14-Pad43)") (class "Default")
      (node (ref "IC16") (pin "43") (pinfunction "EBIA1/AN9/ERXD2/AETXD3/RPB14/SCK3/PMA1/RB14_43") (pintype "bidirectional"))
    )
    (net (code "262") (name "unconnected-(IC16-EBIA6{slash}AN22{slash}RPC1{slash}PMA6{slash}RC1-Pad6)") (class "Default")
      (node (ref "IC16") (pin "6") (pinfunction "EBIA6/AN22/RPC1/PMA6/RC1_6") (pintype "bidirectional"))
    )
    (net (code "263") (name "unconnected-(IC16-EBIA9{slash}RPF4{slash}SDA5{slash}PMA9{slash}RF4-Pad64)") (class "Default")
      (node (ref "IC16") (pin "64") (pinfunction "EBIA9/RPF4/SDA5/PMA9/RF4_64") (pintype "bidirectional"))
    )
    (net (code "264") (name "unconnected-(IC16-EBID8{slash}RPG0{slash}PMD8{slash}RG0-Pad88)") (class "Default")
      (node (ref "IC16") (pin "88") (pinfunction "EBID8/RPG0/PMD8/RG0_88") (pintype "input"))
    )
    (net (code "265") (name "unconnected-(IC16-EBID9{slash}ETXERR{slash}RPG1{slash}PMD9{slash}RG1-Pad87)") (class "Default")
      (node (ref "IC16") (pin "87") (pinfunction "EBID9/ETXERR/RPG1/PMD9/RG1_87") (pintype "bidirectional"))
    )
    (net (code "266") (name "unconnected-(IC16-EBID15{slash}ETXCLK{slash}RPD3...-Pad78)") (class "Default")
      (node (ref "IC16") (pin "78") (pinfunction "EBID15/ETXCLK/RPD3..._78") (pintype "bidirectional"))
    )
    (net (code "267") (name "unconnected-(IC16-OSC2{slash}CLKO{slash}RC15-Pad50)") (class "Default")
      (node (ref "IC16") (pin "50") (pinfunction "OSC2/CLKO/RC15_50") (pintype "bidirectional"))
    )
    (net (code "268") (name "unconnected-(IC16-TDI{slash}EBIA18{slash}AN30{slash}RPF13{slash}SCK5{slash}RF13-Pad39)") (class "Default")
      (node (ref "IC16") (pin "39") (pinfunction "TDI/EBIA18/AN30/RPF13/SCK5/RF13_39") (pintype "bidirectional"))
    )
    (net (code "269") (name "unconnected-(IC16-TDO{slash}EBIA17{slash}AN31{slash}RPF12{slash}RF12-Pad40)") (class "Default")
      (node (ref "IC16") (pin "40") (pinfunction "TDO/EBIA17/AN31/RPF12/RF12_40") (pintype "bidirectional"))
    )
    (net (code "270") (name "unconnected-(IC16-VREF+{slash}CVREF+{slash}AN28{slash}AERXD3{slash}RA10-Pad29)") (class "Default")
      (node (ref "IC16") (pin "29") (pinfunction "VREF+/CVREF+/AN28/AERXD3/RA10_29") (pintype "bidirectional"))
    )
    (net (code "271") (name "unconnected-(IC16-VREF-{slash}CVREF-{slash}AN27{slash}AERXD2{slash}RA9-Pad28)") (class "Default")
      (node (ref "IC16") (pin "28") (pinfunction "VREF-/CVREF-/AN27/AERXD2/RA9_28") (pintype "bidirectional"))
    )
    (net (code "272") (name "unconnected-(IC16-~{SQICS0}{slash}RPD4{slash}RD4-Pad81)") (class "Default")
      (node (ref "IC16") (pin "81") (pinfunction "~{SQICS0}/RPD4/RD4_81") (pintype "bidirectional"))
    )
    (net (code "273") (name "unconnected-(IC16-~{SQICS1}{slash}RPD5{slash}RD5-Pad82)") (class "Default")
      (node (ref "IC16") (pin "82") (pinfunction "~{SQICS1}/RPD5/RD5_82") (pintype "bidirectional"))
    )
    (net (code "274") (name "unconnected-(IC18-N{slash}C-Pad4)") (class "Default")
      (node (ref "IC18") (pin "4") (pinfunction "N/C_4") (pintype "bidirectional"))
    )
    (net (code "275") (name "unconnected-(IC19-CBUS2-Pad13)") (class "Default")
      (node (ref "IC19") (pin "13") (pinfunction "CBUS2_13") (pintype "bidirectional"))
    )
    (net (code "276") (name "unconnected-(IC19-CBUS3-Pad14)") (class "Default")
      (node (ref "IC19") (pin "14") (pinfunction "CBUS3_14") (pintype "bidirectional"))
    )
    (net (code "277") (name "unconnected-(IC19-CBUS4-Pad12)") (class "Default")
      (node (ref "IC19") (pin "12") (pinfunction "CBUS4_12") (pintype "bidirectional"))
    )
    (net (code "278") (name "unconnected-(IC19-OSCI-Pad27)") (class "Default")
      (node (ref "IC19") (pin "27") (pinfunction "OSCI_27") (pintype "input"))
    )
    (net (code "279") (name "unconnected-(IC19-OSCO-Pad28)") (class "Default")
      (node (ref "IC19") (pin "28") (pinfunction "OSCO_28") (pintype "output"))
    )
    (net (code "280") (name "unconnected-(IC19-~{DCD}-Pad10)") (class "Default")
      (node (ref "IC19") (pin "10") (pinfunction "~{DCD}_10") (pintype "input"))
    )
    (net (code "281") (name "unconnected-(IC19-~{DSR}-Pad9)") (class "Default")
      (node (ref "IC19") (pin "9") (pinfunction "~{DSR}_9") (pintype "input"))
    )
    (net (code "282") (name "unconnected-(IC19-~{DTR}-Pad2)") (class "Default")
      (node (ref "IC19") (pin "2") (pinfunction "~{DTR}_2") (pintype "output"))
    )
    (net (code "283") (name "unconnected-(IC19-~{RESET}-Pad19)") (class "Default")
      (node (ref "IC19") (pin "19") (pinfunction "~{RESET}_19") (pintype "input"))
    )
    (net (code "284") (name "unconnected-(IC19-~{RI}-Pad6)") (class "Default")
      (node (ref "IC19") (pin "6") (pinfunction "~{RI}_6") (pintype "input"))
    )
    (net (code "285") (name "unconnected-(IC20-N{slash}C-Pad4)") (class "Default")
      (node (ref "IC20") (pin "4") (pinfunction "N/C_4") (pintype "bidirectional"))
    )
    (net (code "286") (name "unconnected-(IC26-B1-Pad14)") (class "Default")
      (node (ref "IC26") (pin "14") (pinfunction "B1_14") (pintype "bidirectional"))
    )
    (net (code "287") (name "unconnected-(J1-Pad2)") (class "Default")
      (node (ref "J1") (pin "2") (pinfunction "2_2") (pintype "passive"))
    )
    (net (code "288") (name "unconnected-(J1-Pad6)") (class "Default")
      (node (ref "J1") (pin "6") (pinfunction "6_6") (pintype "passive"))
    )
    (net (code "289") (name "unconnected-(J1-Pad7)") (class "Default")
      (node (ref "J1") (pin "7") (pinfunction "7_7") (pintype "passive"))
    )
    (net (code "290") (name "unconnected-(J1-Pad8)") (class "Default")
      (node (ref "J1") (pin "8") (pinfunction "8_8") (pintype "passive"))
    )
    (net (code "291") (name "unconnected-(J2-Pad5)") (class "Default")
      (node (ref "J2") (pin "5") (pinfunction "5_5") (pintype "passive"))
    )
    (net (code "292") (name "unconnected-(J2-Pad6)") (class "Default")
      (node (ref "J2") (pin "6") (pinfunction "6_6") (pintype "passive"))
    )
    (net (code "293") (name "unconnected-(J2-Pad7)") (class "Default")
      (node (ref "J2") (pin "7") (pinfunction "7_7") (pintype "passive"))
    )
    (net (code "294") (name "unconnected-(J2-Pad8)") (class "Default")
      (node (ref "J2") (pin "8") (pinfunction "8_8") (pintype "passive"))
    )
    (net (code "295") (name "unconnected-(J3-3-PadP3)") (class "Default")
      (node (ref "J3") (pin "P3") (pinfunction "3_P3") (pintype "passive"))
    )
    (net (code "296") (name "unconnected-(J4-3-PadP3)") (class "Default")
      (node (ref "J4") (pin "P3") (pinfunction "3_P3") (pintype "passive"))
    )
    (net (code "297") (name "unconnected-(JP1-Pad6)") (class "Default")
      (node (ref "JP1") (pin "6") (pinfunction "6_6") (pintype "passive"))
    )
    (net (code "298") (name "unconnected-(OSC1-STANDBY#-PadP$1)") (class "Default")
      (node (ref "OSC1") (pin "P$1") (pinfunction "STANDBY#_P$1") (pintype "passive"))
    )
    (net (code "299") (name "unconnected-(OSC2-STANDBY#-PadP$1)") (class "Default")
      (node (ref "OSC2") (pin "P$1") (pinfunction "STANDBY#_P$1") (pintype "passive"))
    )
    (net (code "300") (name "unconnected-(PDI-Pad3)") (class "Default")
      (node (ref "PDI") (pin "3") (pinfunction "3_3") (pintype "passive"))
    )
    (net (code "301") (name "unconnected-(PDI-Pad4)") (class "Default")
      (node (ref "PDI") (pin "4") (pinfunction "4_4") (pintype "passive"))
    )
    (net (code "302") (name "unconnected-(USB1-4-PadP$4)") (class "Default")
      (node (ref "USB1") (pin "P$4") (pinfunction "4_P$4") (pintype "bidirectional"))
    )
    (net (code "303") (name "unconnected-(USB1-P$2-PadSHIELD_1)") (class "Default")
      (node (ref "USB1") (pin "SHIELD_1") (pinfunction "P$2_SHIELD_1") (pintype "bidirectional"))
    )
    (net (code "304") (name "unconnected-(USB1-P$3-PadSHIELD_2)") (class "Default")
      (node (ref "USB1") (pin "SHIELD_2") (pinfunction "P$3_SHIELD_2") (pintype "bidirectional"))
    )
    (net (code "305") (name "unconnected-(USB1-P$5-PadP$6)") (class "Default")
      (node (ref "USB1") (pin "P$6") (pinfunction "P$5_P$6") (pintype "bidirectional"))
    )
    (net (code "306") (name "unconnected-(USB1-P$6-PadP$7)") (class "Default")
      (node (ref "USB1") (pin "P$7") (pinfunction "P$6_P$7") (pintype "bidirectional"))
    )
    (net (code "307") (name "unconnected-(USB2-4-PadP$4)") (class "Default")
      (node (ref "USB2") (pin "P$4") (pinfunction "4_P$4") (pintype "bidirectional"))
    )
    (net (code "308") (name "unconnected-(USB2-P$2-PadSHIELD_2)") (class "Default")
      (node (ref "USB2") (pin "SHIELD_2") (pinfunction "P$2_SHIELD_2") (pintype "bidirectional"))
    )
    (net (code "309") (name "unconnected-(USB2-P$3-PadSHIELD_3)") (class "Default")
      (node (ref "USB2") (pin "SHIELD_3") (pinfunction "P$3_SHIELD_3") (pintype "bidirectional"))
    )
    (net (code "310") (name "~{MCLR}") (class "Default")
      (node (ref "IC16") (pin "15") (pinfunction "~{MCLR}_15") (pintype "bidirectional"))
      (node (ref "JP1") (pin "1") (pinfunction "1_1") (pintype "passive"))
      (node (ref "R57") (pin "1") (pinfunction "1_1") (pintype "passive"))
      (node (ref "SW1") (pin "O") (pinfunction "O_O") (pintype "passive"))
    )
    (net (code "311") (name "~{SS1}") (class "Default")
      (node (ref "IC16") (pin "32") (pinfunction "EBIA10/AN48/RPB8/PMA10/RB8_32") (pintype "bidirectional"))
      (node (ref "IC6") (pin "P25") (pinfunction "~{CLATCH}_P25") (pintype "bidirectional"))
    )
    (net (code "312") (name "~{UART_RX}") (class "Default")
      (node (ref "IC27") (pin "7") (pinfunction "B_7") (pintype "bidirectional"))
      (node (ref "J2") (pin "2") (pinfunction "2_2") (pintype "passive"))
      (node (ref "R64") (pin "1") (pinfunction "1_1") (pintype "passive"))
    )
    (net (code "313") (name "~{UART_TX}") (class "Default")
      (node (ref "IC27") (pin "6") (pinfunction "Z_6") (pintype "bidirectional"))
      (node (ref "J2") (pin "3") (pinfunction "3_3") (pintype "passive"))
      (node (ref "R65") (pin "2") (pinfunction "2_2") (pintype "passive"))
    )
  )
)
